# Sheet1.net
KiCad netlist of a schematic drawn in Altium Designer
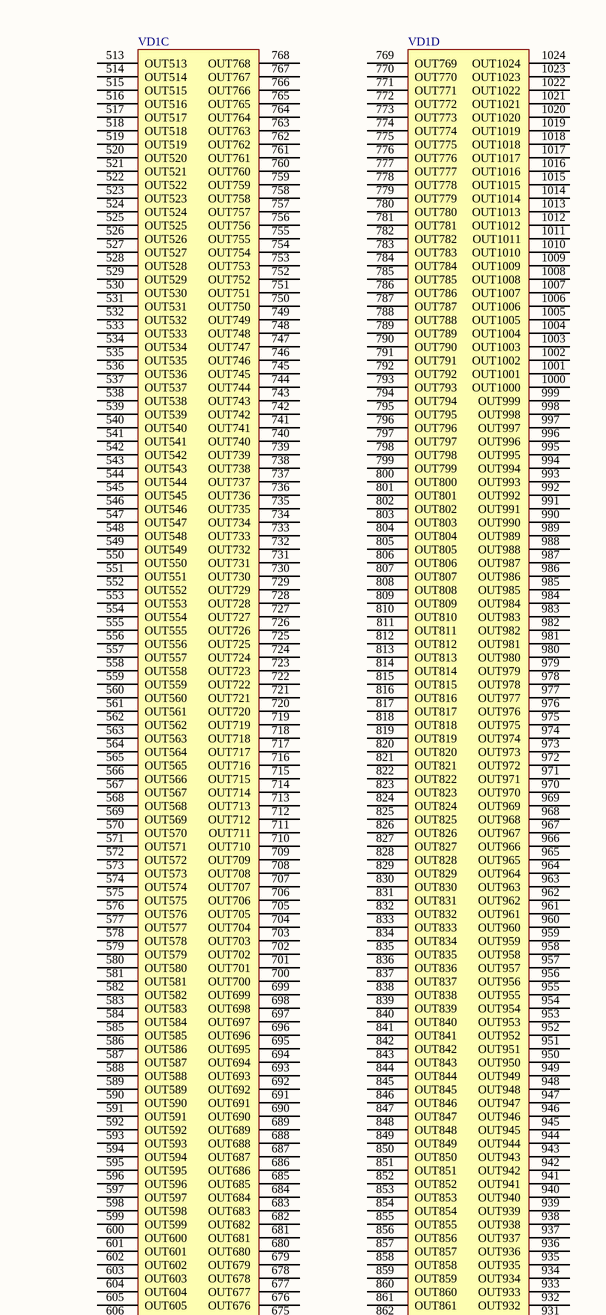
[diagram p0: Sheet1.SchDoc, top right]
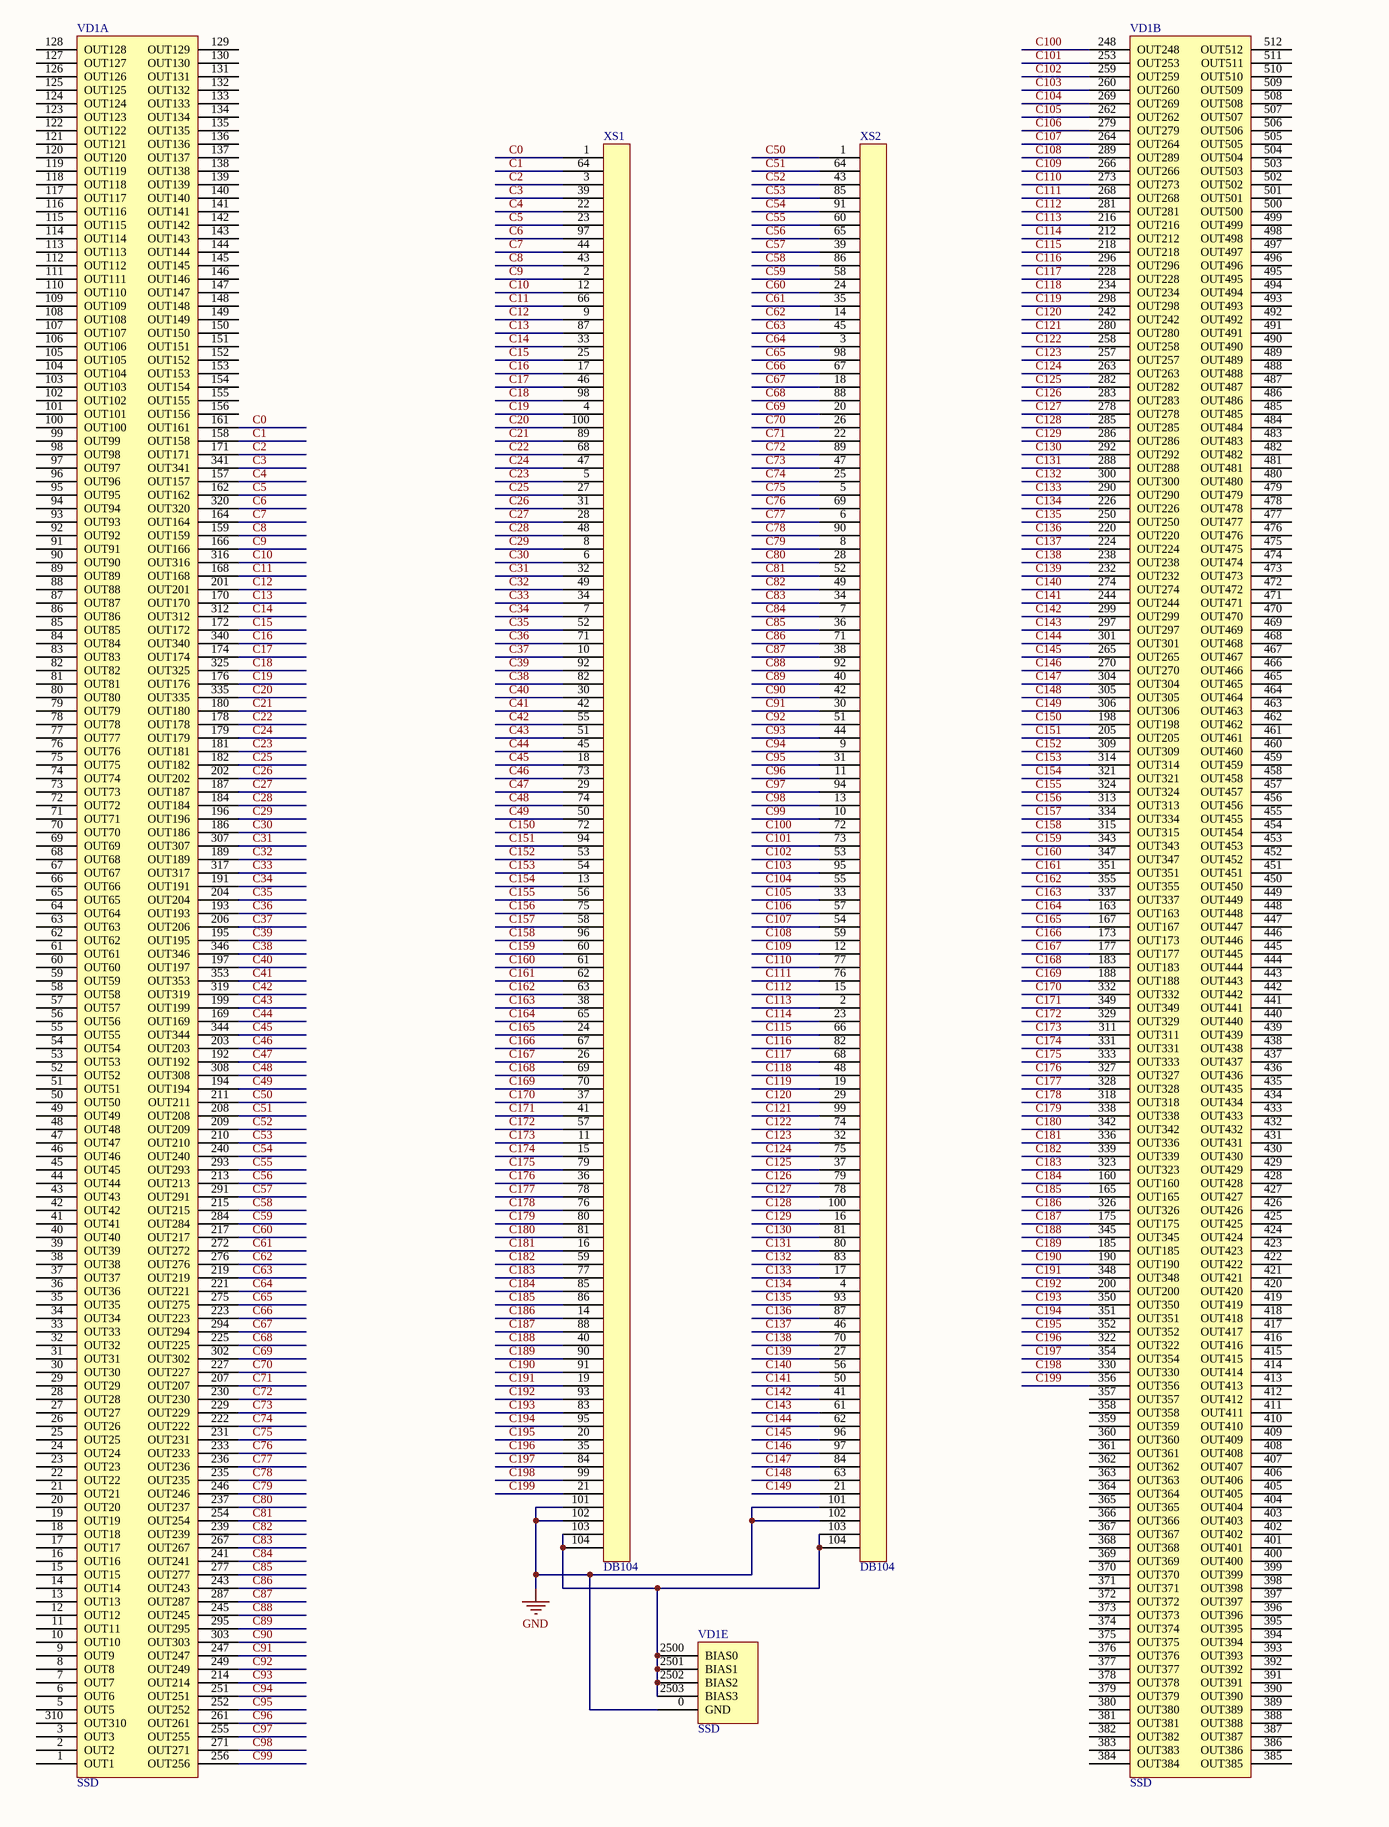
[diagram p1: Sheet1.SchDoc, bottom left]
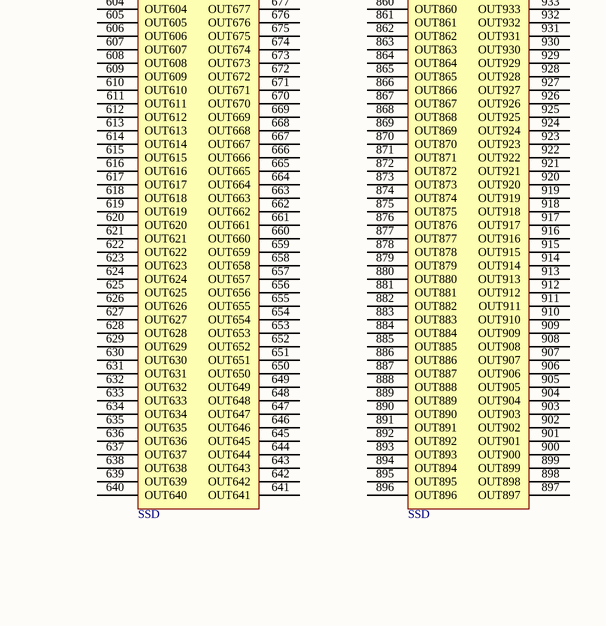
[diagram p2: Sheet1.SchDoc, bottom right]

(export (version "E")
  (design (tool "Eeschema 10.0.6"))
  (components
    (comp (ref "VD1")
      (value "SSD")
      (footprint "QFN20P11000X11000X80-2048N")
      (libsource (lib "Schlib") (part "SSD"))
    )
    (comp (ref "XS1") (value "DB104") (footprint "DB104") (libsource (lib "") (part "DB104_1")))
    (comp (ref "XS2") (value "DB104") (footprint "DB104") (libsource (lib "Schlib") (part "DB104")))
  )
  (nets
    (net (code "1") (name "/C0") (class "Default")
      (node (ref "VD1") (pin "161") (pinfunction "OUT161_161") (pintype "passive"))
      (node (ref "XS1") (pin "1") (pintype "passive"))
    )
    (net (code "2") (name "/C1") (class "Default")
      (node (ref "VD1") (pin "158") (pinfunction "OUT158_158") (pintype "passive"))
      (node (ref "XS1") (pin "64") (pintype "passive"))
    )
    (net (code "3") (name "/C2") (class "Default")
      (node (ref "VD1") (pin "171") (pinfunction "OUT171_171") (pintype "passive"))
      (node (ref "XS1") (pin "3") (pintype "passive"))
    )
    (net (code "4") (name "/C3") (class "Default")
      (node (ref "VD1") (pin "341") (pinfunction "OUT341_341") (pintype "passive"))
      (node (ref "XS1") (pin "39") (pintype "passive"))
    )
    (net (code "5") (name "/C4") (class "Default")
      (node (ref "VD1") (pin "157") (pinfunction "OUT157_157") (pintype "passive"))
      (node (ref "XS1") (pin "22") (pintype "passive"))
    )
    (net (code "6") (name "/C5") (class "Default")
      (node (ref "VD1") (pin "162") (pinfunction "OUT162_162") (pintype "passive"))
      (node (ref "XS1") (pin "23") (pintype "passive"))
    )
    (net (code "7") (name "/C6") (class "Default")
      (node (ref "VD1") (pin "320") (pinfunction "OUT320_320") (pintype "passive"))
      (node (ref "XS1") (pin "97") (pintype "passive"))
    )
    (net (code "8") (name "/C7") (class "Default")
      (node (ref "VD1") (pin "164") (pinfunction "OUT164_164") (pintype "passive"))
      (node (ref "XS1") (pin "44") (pintype "passive"))
    )
    (net (code "9") (name "/C8") (class "Default")
      (node (ref "VD1") (pin "159") (pinfunction "OUT159_159") (pintype "passive"))
      (node (ref "XS1") (pin "43") (pintype "passive"))
    )
    (net (code "10") (name "/C9") (class "Default")
      (node (ref "VD1") (pin "166") (pinfunction "OUT166_166") (pintype "passive"))
      (node (ref "XS1") (pin "2") (pintype "passive"))
    )
    (net (code "11") (name "/C10") (class "Default")
      (node (ref "VD1") (pin "316") (pinfunction "OUT316_316") (pintype "passive"))
      (node (ref "XS1") (pin "12") (pintype "passive"))
    )
    (net (code "12") (name "/C11") (class "Default")
      (node (ref "VD1") (pin "168") (pinfunction "OUT168_168") (pintype "passive"))
      (node (ref "XS1") (pin "66") (pintype "passive"))
    )
    (net (code "13") (name "/C12") (class "Default")
      (node (ref "VD1") (pin "201") (pinfunction "OUT201_201") (pintype "passive"))
      (node (ref "XS1") (pin "9") (pintype "passive"))
    )
    (net (code "14") (name "/C13") (class "Default")
      (node (ref "VD1") (pin "170") (pinfunction "OUT170_170") (pintype "passive"))
      (node (ref "XS1") (pin "87") (pintype "passive"))
    )
    (net (code "15") (name "/C14") (class "Default")
      (node (ref "VD1") (pin "312") (pinfunction "OUT312_312") (pintype "passive"))
      (node (ref "XS1") (pin "33") (pintype "passive"))
    )
    (net (code "16") (name "/C15") (class "Default")
      (node (ref "VD1") (pin "172") (pinfunction "OUT172_172") (pintype "passive"))
      (node (ref "XS1") (pin "25") (pintype "passive"))
    )
    (net (code "17") (name "/C16") (class "Default")
      (node (ref "VD1") (pin "340") (pinfunction "OUT340_340") (pintype "passive"))
      (node (ref "XS1") (pin "17") (pintype "passive"))
    )
    (net (code "18") (name "/C17") (class "Default")
      (node (ref "VD1") (pin "174") (pinfunction "OUT174_174") (pintype "passive"))
      (node (ref "XS1") (pin "46") (pintype "passive"))
    )
    (net (code "19") (name "/C18") (class "Default")
      (node (ref "VD1") (pin "325") (pinfunction "OUT325_325") (pintype "passive"))
      (node (ref "XS1") (pin "98") (pintype "passive"))
    )
    (net (code "20") (name "/C19") (class "Default")
      (node (ref "VD1") (pin "176") (pinfunction "OUT176_176") (pintype "passive"))
      (node (ref "XS1") (pin "4") (pintype "passive"))
    )
    (net (code "21") (name "/C20") (class "Default")
      (node (ref "VD1") (pin "335") (pinfunction "OUT335_335") (pintype "passive"))
      (node (ref "XS1") (pin "100") (pintype "passive"))
    )
    (net (code "22") (name "/C21") (class "Default")
      (node (ref "VD1") (pin "180") (pinfunction "OUT180_180") (pintype "passive"))
      (node (ref "XS1") (pin "89") (pintype "passive"))
    )
    (net (code "23") (name "/C22") (class "Default")
      (node (ref "VD1") (pin "178") (pinfunction "OUT178_178") (pintype "passive"))
      (node (ref "XS1") (pin "68") (pintype "passive"))
    )
    (net (code "24") (name "/C23") (class "Default")
      (node (ref "VD1") (pin "181") (pinfunction "OUT181_181") (pintype "passive"))
      (node (ref "XS1") (pin "5") (pintype "passive"))
    )
    (net (code "25") (name "/C24") (class "Default")
      (node (ref "VD1") (pin "179") (pinfunction "OUT179_179") (pintype "passive"))
      (node (ref "XS1") (pin "47") (pintype "passive"))
    )
    (net (code "26") (name "/C25") (class "Default")
      (node (ref "VD1") (pin "182") (pinfunction "OUT182_182") (pintype "passive"))
      (node (ref "XS1") (pin "27") (pintype "passive"))
    )
    (net (code "27") (name "/C26") (class "Default")
      (node (ref "VD1") (pin "202") (pinfunction "OUT202_202") (pintype "passive"))
      (node (ref "XS1") (pin "31") (pintype "passive"))
    )
    (net (code "28") (name "/C27") (class "Default")
      (node (ref "VD1") (pin "187") (pinfunction "OUT187_187") (pintype "passive"))
      (node (ref "XS1") (pin "28") (pintype "passive"))
    )
    (net (code "29") (name "/C28") (class "Default")
      (node (ref "VD1") (pin "184") (pinfunction "OUT184_184") (pintype "passive"))
      (node (ref "XS1") (pin "48") (pintype "passive"))
    )
    (net (code "30") (name "/C29") (class "Default")
      (node (ref "VD1") (pin "196") (pinfunction "OUT196_196") (pintype "passive"))
      (node (ref "XS1") (pin "8") (pintype "passive"))
    )
    (net (code "31") (name "/C30") (class "Default")
      (node (ref "VD1") (pin "186") (pinfunction "OUT186_186") (pintype "passive"))
      (node (ref "XS1") (pin "6") (pintype "passive"))
    )
    (net (code "32") (name "/C31") (class "Default")
      (node (ref "VD1") (pin "307") (pinfunction "OUT307_307") (pintype "passive"))
      (node (ref "XS1") (pin "32") (pintype "passive"))
    )
    (net (code "33") (name "/C32") (class "Default")
      (node (ref "VD1") (pin "189") (pinfunction "OUT189_189") (pintype "passive"))
      (node (ref "XS1") (pin "49") (pintype "passive"))
    )
    (net (code "34") (name "/C33") (class "Default")
      (node (ref "VD1") (pin "317") (pinfunction "OUT317_317") (pintype "passive"))
      (node (ref "XS1") (pin "34") (pintype "passive"))
    )
    (net (code "35") (name "/C34") (class "Default")
      (node (ref "VD1") (pin "191") (pinfunction "OUT191_191") (pintype "passive"))
      (node (ref "XS1") (pin "7") (pintype "passive"))
    )
    (net (code "36") (name "/C35") (class "Default")
      (node (ref "VD1") (pin "204") (pinfunction "OUT204_204") (pintype "passive"))
      (node (ref "XS1") (pin "52") (pintype "passive"))
    )
    (net (code "37") (name "/C36") (class "Default")
      (node (ref "VD1") (pin "193") (pinfunction "OUT193_193") (pintype "passive"))
      (node (ref "XS1") (pin "71") (pintype "passive"))
    )
    (net (code "38") (name "/C37") (class "Default")
      (node (ref "VD1") (pin "206") (pinfunction "OUT206_206") (pintype "passive"))
      (node (ref "XS1") (pin "10") (pintype "passive"))
    )
    (net (code "39") (name "/C38") (class "Default")
      (node (ref "VD1") (pin "346") (pinfunction "OUT346_346") (pintype "passive"))
      (node (ref "XS1") (pin "82") (pintype "passive"))
    )
    (net (code "40") (name "/C39") (class "Default")
      (node (ref "VD1") (pin "195") (pinfunction "OUT195_195") (pintype "passive"))
      (node (ref "XS1") (pin "92") (pintype "passive"))
    )
    (net (code "41") (name "/C40") (class "Default")
      (node (ref "VD1") (pin "197") (pinfunction "OUT197_197") (pintype "passive"))
      (node (ref "XS1") (pin "30") (pintype "passive"))
    )
    (net (code "42") (name "/C41") (class "Default")
      (node (ref "VD1") (pin "353") (pinfunction "OUT353_353") (pintype "passive"))
      (node (ref "XS1") (pin "42") (pintype "passive"))
    )
    (net (code "43") (name "/C42") (class "Default")
      (node (ref "VD1") (pin "319") (pinfunction "OUT319_319") (pintype "passive"))
      (node (ref "XS1") (pin "55") (pintype "passive"))
    )
    (net (code "44") (name "/C43") (class "Default")
      (node (ref "VD1") (pin "199") (pinfunction "OUT199_199") (pintype "passive"))
      (node (ref "XS1") (pin "51") (pintype "passive"))
    )
    (net (code "45") (name "/C44") (class "Default")
      (node (ref "VD1") (pin "169") (pinfunction "OUT169_169") (pintype "passive"))
      (node (ref "XS1") (pin "45") (pintype "passive"))
    )
    (net (code "46") (name "/C45") (class "Default")
      (node (ref "VD1") (pin "344") (pinfunction "OUT344_344") (pintype "passive"))
      (node (ref "XS1") (pin "18") (pintype "passive"))
    )
    (net (code "47") (name "/C46") (class "Default")
      (node (ref "VD1") (pin "203") (pinfunction "OUT203_203") (pintype "passive"))
      (node (ref "XS1") (pin "73") (pintype "passive"))
    )
    (net (code "48") (name "/C47") (class "Default")
      (node (ref "VD1") (pin "192") (pinfunction "OUT192_192") (pintype "passive"))
      (node (ref "XS1") (pin "29") (pintype "passive"))
    )
    (net (code "49") (name "/C48") (class "Default")
      (node (ref "VD1") (pin "308") (pinfunction "OUT308_308") (pintype "passive"))
      (node (ref "XS1") (pin "74") (pintype "passive"))
    )
    (net (code "50") (name "/C49") (class "Default")
      (node (ref "VD1") (pin "194") (pinfunction "OUT194_194") (pintype "passive"))
      (node (ref "XS1") (pin "50") (pintype "passive"))
    )
    (net (code "51") (name "/C50") (class "Default")
      (node (ref "VD1") (pin "211") (pinfunction "OUT211_211") (pintype "passive"))
      (node (ref "XS2") (pin "1") (pintype "passive"))
    )
    (net (code "52") (name "/C51") (class "Default")
      (node (ref "VD1") (pin "208") (pinfunction "OUT208_208") (pintype "passive"))
      (node (ref "XS2") (pin "64") (pintype "passive"))
    )
    (net (code "53") (name "/C52") (class "Default")
      (node (ref "VD1") (pin "209") (pinfunction "OUT209_209") (pintype "passive"))
      (node (ref "XS2") (pin "43") (pintype "passive"))
    )
    (net (code "54") (name "/C53") (class "Default")
      (node (ref "VD1") (pin "210") (pinfunction "OUT210_210") (pintype "passive"))
      (node (ref "XS2") (pin "85") (pintype "passive"))
    )
    (net (code "55") (name "/C54") (class "Default")
      (node (ref "VD1") (pin "240") (pinfunction "OUT240_240") (pintype "passive"))
      (node (ref "XS2") (pin "91") (pintype "passive"))
    )
    (net (code "56") (name "/C55") (class "Default")
      (node (ref "VD1") (pin "293") (pinfunction "OUT293_293") (pintype "passive"))
      (node (ref "XS2") (pin "60") (pintype "passive"))
    )
    (net (code "57") (name "/C56") (class "Default")
      (node (ref "VD1") (pin "213") (pinfunction "OUT213_213") (pintype "passive"))
      (node (ref "XS2") (pin "65") (pintype "passive"))
    )
    (net (code "58") (name "/C57") (class "Default")
      (node (ref "VD1") (pin "291") (pinfunction "OUT291_291") (pintype "passive"))
      (node (ref "XS2") (pin "39") (pintype "passive"))
    )
    (net (code "59") (name "/C58") (class "Default")
      (node (ref "VD1") (pin "215") (pinfunction "OUT215_215") (pintype "passive"))
      (node (ref "XS2") (pin "86") (pintype "passive"))
    )
    (net (code "60") (name "/C59") (class "Default")
      (node (ref "VD1") (pin "284") (pinfunction "OUT284_284") (pintype "passive"))
      (node (ref "XS2") (pin "58") (pintype "passive"))
    )
    (net (code "61") (name "/C60") (class "Default")
      (node (ref "VD1") (pin "217") (pinfunction "OUT217_217") (pintype "passive"))
      (node (ref "XS2") (pin "24") (pintype "passive"))
    )
    (net (code "62") (name "/C61") (class "Default")
      (node (ref "VD1") (pin "272") (pinfunction "OUT272_272") (pintype "passive"))
      (node (ref "XS2") (pin "35") (pintype "passive"))
    )
    (net (code "63") (name "/C62") (class "Default")
      (node (ref "VD1") (pin "276") (pinfunction "OUT276_276") (pintype "passive"))
      (node (ref "XS2") (pin "14") (pintype "passive"))
    )
    (net (code "64") (name "/C63") (class "Default")
      (node (ref "VD1") (pin "219") (pinfunction "OUT219_219") (pintype "passive"))
      (node (ref "XS2") (pin "45") (pintype "passive"))
    )
    (net (code "65") (name "/C64") (class "Default")
      (node (ref "VD1") (pin "221") (pinfunction "OUT221_221") (pintype "passive"))
      (node (ref "XS2") (pin "3") (pintype "passive"))
    )
    (net (code "66") (name "/C65") (class "Default")
      (node (ref "VD1") (pin "275") (pinfunction "OUT275_275") (pintype "passive"))
      (node (ref "XS2") (pin "98") (pintype "passive"))
    )
    (net (code "67") (name "/C66") (class "Default")
      (node (ref "VD1") (pin "223") (pinfunction "OUT223_223") (pintype "passive"))
      (node (ref "XS2") (pin "67") (pintype "passive"))
    )
    (net (code "68") (name "/C67") (class "Default")
      (node (ref "VD1") (pin "294") (pinfunction "OUT294_294") (pintype "passive"))
      (node (ref "XS2") (pin "18") (pintype "passive"))
    )
    (net (code "69") (name "/C68") (class "Default")
      (node (ref "VD1") (pin "225") (pinfunction "OUT225_225") (pintype "passive"))
      (node (ref "XS2") (pin "88") (pintype "passive"))
    )
    (net (code "70") (name "/C69") (class "Default")
      (node (ref "VD1") (pin "302") (pinfunction "OUT302_302") (pintype "passive"))
      (node (ref "XS2") (pin "20") (pintype "passive"))
    )
    (net (code "71") (name "/C70") (class "Default")
      (node (ref "VD1") (pin "227") (pinfunction "OUT227_227") (pintype "passive"))
      (node (ref "XS2") (pin "26") (pintype "passive"))
    )
    (net (code "72") (name "/C71") (class "Default")
      (node (ref "VD1") (pin "207") (pinfunction "OUT207_207") (pintype "passive"))
      (node (ref "XS2") (pin "22") (pintype "passive"))
    )
    (net (code "73") (name "/C72") (class "Default")
      (node (ref "VD1") (pin "230") (pinfunction "OUT230_230") (pintype "passive"))
      (node (ref "XS2") (pin "89") (pintype "passive"))
    )
    (net (code "74") (name "/C73") (class "Default")
      (node (ref "VD1") (pin "229") (pinfunction "OUT229_229") (pintype "passive"))
      (node (ref "XS2") (pin "47") (pintype "passive"))
    )
    (net (code "75") (name "/C74") (class "Default")
      (node (ref "VD1") (pin "222") (pinfunction "OUT222_222") (pintype "passive"))
      (node (ref "XS2") (pin "25") (pintype "passive"))
    )
    (net (code "76") (name "/C75") (class "Default")
      (node (ref "VD1") (pin "231") (pinfunction "OUT231_231") (pintype "passive"))
      (node (ref "XS2") (pin "5") (pintype "passive"))
    )
    (net (code "77") (name "/C76") (class "Default")
      (node (ref "VD1") (pin "233") (pinfunction "OUT233_233") (pintype "passive"))
      (node (ref "XS2") (pin "69") (pintype "passive"))
    )
    (net (code "78") (name "/C77") (class "Default")
      (node (ref "VD1") (pin "236") (pinfunction "OUT236_236") (pintype "passive"))
      (node (ref "XS2") (pin "6") (pintype "passive"))
    )
    (net (code "79") (name "/C78") (class "Default")
      (node (ref "VD1") (pin "235") (pinfunction "OUT235_235") (pintype "passive"))
      (node (ref "XS2") (pin "90") (pintype "passive"))
    )
    (net (code "80") (name "/C79") (class "Default")
      (node (ref "VD1") (pin "246") (pinfunction "OUT246_246") (pintype "passive"))
      (node (ref "XS2") (pin "8") (pintype "passive"))
    )
    (net (code "81") (name "/C80") (class "Default")
      (node (ref "VD1") (pin "237") (pinfunction "OUT237_237") (pintype "passive"))
      (node (ref "XS2") (pin "28") (pintype "passive"))
    )
    (net (code "82") (name "/C81") (class "Default")
      (node (ref "VD1") (pin "254") (pinfunction "OUT254_254") (pintype "passive"))
      (node (ref "XS2") (pin "52") (pintype "passive"))
    )
    (net (code "83") (name "/C82") (class "Default")
      (node (ref "VD1") (pin "239") (pinfunction "OUT239_239") (pintype "passive"))
      (node (ref "XS2") (pin "49") (pintype "passive"))
    )
    (net (code "84") (name "/C83") (class "Default")
      (node (ref "VD1") (pin "267") (pinfunction "OUT267_267") (pintype "passive"))
      (node (ref "XS2") (pin "34") (pintype "passive"))
    )
    (net (code "85") (name "/C84") (class "Default")
      (node (ref "VD1") (pin "241") (pinfunction "OUT241_241") (pintype "passive"))
      (node (ref "XS2") (pin "7") (pintype "passive"))
    )
    (net (code "86") (name "/C85") (class "Default")
      (node (ref "VD1") (pin "277") (pinfunction "OUT277_277") (pintype "passive"))
      (node (ref "XS2") (pin "36") (pintype "passive"))
    )
    (net (code "87") (name "/C86") (class "Default")
      (node (ref "VD1") (pin "243") (pinfunction "OUT243_243") (pintype "passive"))
      (node (ref "XS2") (pin "71") (pintype "passive"))
    )
    (net (code "88") (name "/C87") (class "Default")
      (node (ref "VD1") (pin "287") (pinfunction "OUT287_287") (pintype "passive"))
      (node (ref "XS2") (pin "38") (pintype "passive"))
    )
    (net (code "89") (name "/C88") (class "Default")
      (node (ref "VD1") (pin "245") (pinfunction "OUT245_245") (pintype "passive"))
      (node (ref "XS2") (pin "92") (pintype "passive"))
    )
    (net (code "90") (name "/C89") (class "Default")
      (node (ref "VD1") (pin "295") (pinfunction "OUT295_295") (pintype "passive"))
      (node (ref "XS2") (pin "40") (pintype "passive"))
    )
    (net (code "91") (name "/C90") (class "Default")
      (node (ref "VD1") (pin "303") (pinfunction "OUT303_303") (pintype "passive"))
      (node (ref "XS2") (pin "42") (pintype "passive"))
    )
    (net (code "92") (name "/C91") (class "Default")
      (node (ref "VD1") (pin "247") (pinfunction "OUT247_247") (pintype "passive"))
      (node (ref "XS2") (pin "30") (pintype "passive"))
    )
    (net (code "93") (name "/C92") (class "Default")
      (node (ref "VD1") (pin "249") (pinfunction "OUT249_249") (pintype "passive"))
      (node (ref "XS2") (pin "51") (pintype "passive"))
    )
    (net (code "94") (name "/C93") (class "Default")
      (node (ref "VD1") (pin "214") (pinfunction "OUT214_214") (pintype "passive"))
      (node (ref "XS2") (pin "44") (pintype "passive"))
    )
    (net (code "95") (name "/C94") (class "Default")
      (node (ref "VD1") (pin "251") (pinfunction "OUT251_251") (pintype "passive"))
      (node (ref "XS2") (pin "9") (pintype "passive"))
    )
    (net (code "96") (name "/C95") (class "Default")
      (node (ref "VD1") (pin "252") (pinfunction "OUT252_252") (pintype "passive"))
      (node (ref "XS2") (pin "31") (pintype "passive"))
    )
    (net (code "97") (name "/C96") (class "Default")
      (node (ref "VD1") (pin "261") (pinfunction "OUT261_261") (pintype "passive"))
      (node (ref "XS2") (pin "11") (pintype "passive"))
    )
    (net (code "98") (name "/C97") (class "Default")
      (node (ref "VD1") (pin "255") (pinfunction "OUT255_255") (pintype "passive"))
      (node (ref "XS2") (pin "94") (pintype "passive"))
    )
    (net (code "99") (name "/C98") (class "Default")
      (node (ref "VD1") (pin "271") (pinfunction "OUT271_271") (pintype "passive"))
      (node (ref "XS2") (pin "13") (pintype "passive"))
    )
    (net (code "100") (name "/C99") (class "Default")
      (node (ref "VD1") (pin "256") (pinfunction "OUT256_256") (pintype "passive"))
      (node (ref "XS2") (pin "10") (pintype "passive"))
    )
    (net (code "101") (name "/C100") (class "Default")
      (node (ref "VD1") (pin "248") (pinfunction "OUT248_248") (pintype "passive"))
      (node (ref "XS2") (pin "72") (pintype "passive"))
    )
    (net (code "102") (name "/C101") (class "Default")
      (node (ref "VD1") (pin "253") (pinfunction "OUT253_253") (pintype "passive"))
      (node (ref "XS2") (pin "73") (pintype "passive"))
    )
    (net (code "103") (name "/C102") (class "Default")
      (node (ref "VD1") (pin "259") (pinfunction "OUT259_259") (pintype "passive"))
      (node (ref "XS2") (pin "53") (pintype "passive"))
    )
    (net (code "104") (name "/C103") (class "Default")
      (node (ref "VD1") (pin "260") (pinfunction "OUT260_260") (pintype "passive"))
      (node (ref "XS2") (pin "95") (pintype "passive"))
    )
    (net (code "105") (name "/C104") (class "Default")
      (node (ref "VD1") (pin "269") (pinfunction "OUT269_269") (pintype "passive"))
      (node (ref "XS2") (pin "55") (pintype "passive"))
    )
    (net (code "106") (name "/C105") (class "Default")
      (node (ref "VD1") (pin "262") (pinfunction "OUT262_262") (pintype "passive"))
      (node (ref "XS2") (pin "33") (pintype "passive"))
    )
    (net (code "107") (name "/C106") (class "Default")
      (node (ref "VD1") (pin "279") (pinfunction "OUT279_279") (pintype "passive"))
      (node (ref "XS2") (pin "57") (pintype "passive"))
    )
    (net (code "108") (name "/C107") (class "Default")
      (node (ref "VD1") (pin "264") (pinfunction "OUT264_264") (pintype "passive"))
      (node (ref "XS2") (pin "54") (pintype "passive"))
    )
    (net (code "109") (name "/C108") (class "Default")
      (node (ref "VD1") (pin "289") (pinfunction "OUT289_289") (pintype "passive"))
      (node (ref "XS2") (pin "59") (pintype "passive"))
    )
    (net (code "110") (name "/C109") (class "Default")
      (node (ref "VD1") (pin "266") (pinfunction "OUT266_266") (pintype "passive"))
      (node (ref "XS2") (pin "12") (pintype "passive"))
    )
    (net (code "111") (name "/C110") (class "Default")
      (node (ref "VD1") (pin "273") (pinfunction "OUT273_273") (pintype "passive"))
      (node (ref "XS2") (pin "77") (pintype "passive"))
    )
    (net (code "112") (name "/C111") (class "Default")
      (node (ref "VD1") (pin "268") (pinfunction "OUT268_268") (pintype "passive"))
      (node (ref "XS2") (pin "76") (pintype "passive"))
    )
    (net (code "113") (name "/C112") (class "Default")
      (node (ref "VD1") (pin "281") (pinfunction "OUT281_281") (pintype "passive"))
      (node (ref "XS2") (pin "15") (pintype "passive"))
    )
    (net (code "114") (name "/C113") (class "Default")
      (node (ref "VD1") (pin "216") (pinfunction "OUT216_216") (pintype "passive"))
      (node (ref "XS2") (pin "2") (pintype "passive"))
    )
    (net (code "115") (name "/C114") (class "Default")
      (node (ref "VD1") (pin "212") (pinfunction "OUT212_212") (pintype "passive"))
      (node (ref "XS2") (pin "23") (pintype "passive"))
    )
    (net (code "116") (name "/C115") (class "Default")
      (node (ref "VD1") (pin "218") (pinfunction "OUT218_218") (pintype "passive"))
      (node (ref "XS2") (pin "66") (pintype "passive"))
    )
    (net (code "117") (name "/C116") (class "Default")
      (node (ref "VD1") (pin "296") (pinfunction "OUT296_296") (pintype "passive"))
      (node (ref "XS2") (pin "82") (pintype "passive"))
    )
    (net (code "118") (name "/C117") (class "Default")
      (node (ref "VD1") (pin "228") (pinfunction "OUT228_228") (pintype "passive"))
      (node (ref "XS2") (pin "68") (pintype "passive"))
    )
    (net (code "119") (name "/C118") (class "Default")
      (node (ref "VD1") (pin "234") (pinfunction "OUT234_234") (pintype "passive"))
      (node (ref "XS2") (pin "48") (pintype "passive"))
    )
    (net (code "120") (name "/C119") (class "Default")
      (node (ref "VD1") (pin "298") (pinfunction "OUT298_298") (pintype "passive"))
      (node (ref "XS2") (pin "19") (pintype "passive"))
    )
    (net (code "121") (name "/C120") (class "Default")
      (node (ref "VD1") (pin "242") (pinfunction "OUT242_242") (pintype "passive"))
      (node (ref "XS2") (pin "29") (pintype "passive"))
    )
    (net (code "122") (name "/C121") (class "Default")
      (node (ref "VD1") (pin "280") (pinfunction "OUT280_280") (pintype "passive"))
      (node (ref "XS2") (pin "99") (pintype "passive"))
    )
    (net (code "123") (name "/C122") (class "Default")
      (node (ref "VD1") (pin "258") (pinfunction "OUT258_258") (pintype "passive"))
      (node (ref "XS2") (pin "74") (pintype "passive"))
    )
    (net (code "124") (name "/C123") (class "Default")
      (node (ref "VD1") (pin "257") (pinfunction "OUT257_257") (pintype "passive"))
      (node (ref "XS2") (pin "32") (pintype "passive"))
    )
    (net (code "125") (name "/C124") (class "Default")
      (node (ref "VD1") (pin "263") (pinfunction "OUT263_263") (pintype "passive"))
      (node (ref "XS2") (pin "75") (pintype "passive"))
    )
    (net (code "126") (name "/C125") (class "Default")
      (node (ref "VD1") (pin "282") (pinfunction "OUT282_282") (pintype "passive"))
      (node (ref "XS2") (pin "37") (pintype "passive"))
    )
    (net (code "127") (name "/C126") (class "Default")
      (node (ref "VD1") (pin "283") (pinfunction "OUT283_283") (pintype "passive"))
      (node (ref "XS2") (pin "79") (pintype "passive"))
    )
    (net (code "128") (name "/C127") (class "Default")
      (node (ref "VD1") (pin "278") (pinfunction "OUT278_278") (pintype "passive"))
      (node (ref "XS2") (pin "78") (pintype "passive"))
    )
    (net (code "129") (name "/C128") (class "Default")
      (node (ref "VD1") (pin "285") (pinfunction "OUT285_285") (pintype "passive"))
      (node (ref "XS2") (pin "100") (pintype "passive"))
    )
    (net (code "130") (name "/C129") (class "Default")
      (node (ref "VD1") (pin "286") (pinfunction "OUT286_286") (pintype "passive"))
      (node (ref "XS2") (pin "16") (pintype "passive"))
    )
    (net (code "131") (name "/C130") (class "Default")
      (node (ref "VD1") (pin "292") (pinfunction "OUT292_292") (pintype "passive"))
      (node (ref "XS2") (pin "81") (pintype "passive"))
    )
    (net (code "132") (name "/C131") (class "Default")
      (node (ref "VD1") (pin "288") (pinfunction "OUT288_288") (pintype "passive"))
      (node (ref "XS2") (pin "80") (pintype "passive"))
    )
    (net (code "133") (name "/C132") (class "Default")
      (node (ref "VD1") (pin "300") (pinfunction "OUT300_300") (pintype "passive"))
      (node (ref "XS2") (pin "83") (pintype "passive"))
    )
    (net (code "134") (name "/C133") (class "Default")
      (node (ref "VD1") (pin "290") (pinfunction "OUT290_290") (pintype "passive"))
      (node (ref "XS2") (pin "17") (pintype "passive"))
    )
    (net (code "135") (name "/C134") (class "Default")
      (node (ref "VD1") (pin "226") (pinfunction "OUT226_226") (pintype "passive"))
      (node (ref "XS2") (pin "4") (pintype "passive"))
    )
    (net (code "136") (name "/C135") (class "Default")
      (node (ref "VD1") (pin "250") (pinfunction "OUT250_250") (pintype "passive"))
      (node (ref "XS2") (pin "93") (pintype "passive"))
    )
    (net (code "137") (name "/C136") (class "Default")
      (node (ref "VD1") (pin "220") (pinfunction "OUT220_220") (pintype "passive"))
      (node (ref "XS2") (pin "87") (pintype "passive"))
    )
    (net (code "138") (name "/C137") (class "Default")
      (node (ref "VD1") (pin "224") (pinfunction "OUT224_224") (pintype "passive"))
      (node (ref "XS2") (pin "46") (pintype "passive"))
    )
    (net (code "139") (name "/C138") (class "Default")
      (node (ref "VD1") (pin "238") (pinfunction "OUT238_238") (pintype "passive"))
      (node (ref "XS2") (pin "70") (pintype "passive"))
    )
    (net (code "140") (name "/C139") (class "Default")
      (node (ref "VD1") (pin "232") (pinfunction "OUT232_232") (pintype "passive"))
      (node (ref "XS2") (pin "27") (pintype "passive"))
    )
    (net (code "141") (name "/C140") (class "Default")
      (node (ref "VD1") (pin "274") (pinfunction "OUT274_274") (pintype "passive"))
      (node (ref "XS2") (pin "56") (pintype "passive"))
    )
    (net (code "142") (name "/C141") (class "Default")
      (node (ref "VD1") (pin "244") (pinfunction "OUT244_244") (pintype "passive"))
      (node (ref "XS2") (pin "50") (pintype "passive"))
    )
    (net (code "143") (name "/C142") (class "Default")
      (node (ref "VD1") (pin "299") (pinfunction "OUT299_299") (pintype "passive"))
      (node (ref "XS2") (pin "41") (pintype "passive"))
    )
    (net (code "144") (name "/C143") (class "Default")
      (node (ref "VD1") (pin "297") (pinfunction "OUT297_297") (pintype "passive"))
      (node (ref "XS2") (pin "61") (pintype "passive"))
    )
    (net (code "145") (name "/C144") (class "Default")
      (node (ref "VD1") (pin "301") (pinfunction "OUT301_301") (pintype "passive"))
      (node (ref "XS2") (pin "62") (pintype "passive"))
    )
    (net (code "146") (name "/C145") (class "Default")
      (node (ref "VD1") (pin "265") (pinfunction "OUT265_265") (pintype "passive"))
      (node (ref "XS2") (pin "96") (pintype "passive"))
    )
    (net (code "147") (name "/C146") (class "Default")
      (node (ref "VD1") (pin "270") (pinfunction "OUT270_270") (pintype "passive"))
      (node (ref "XS2") (pin "97") (pintype "passive"))
    )
    (net (code "148") (name "/C147") (class "Default")
      (node (ref "VD1") (pin "304") (pinfunction "OUT304_304") (pintype "passive"))
      (node (ref "XS2") (pin "84") (pintype "passive"))
    )
    (net (code "149") (name "/C148") (class "Default")
      (node (ref "VD1") (pin "305") (pinfunction "OUT305_305") (pintype "passive"))
      (node (ref "XS2") (pin "63") (pintype "passive"))
    )
    (net (code "150") (name "/C149") (class "Default")
      (node (ref "VD1") (pin "306") (pinfunction "OUT306_306") (pintype "passive"))
      (node (ref "XS2") (pin "21") (pintype "passive"))
    )
    (net (code "151") (name "/C150") (class "Default")
      (node (ref "VD1") (pin "198") (pinfunction "OUT198_198") (pintype "passive"))
      (node (ref "XS1") (pin "72") (pintype "passive"))
    )
    (net (code "152") (name "/C151") (class "Default")
      (node (ref "VD1") (pin "205") (pinfunction "OUT205_205") (pintype "passive"))
      (node (ref "XS1") (pin "94") (pintype "passive"))
    )
    (net (code "153") (name "/C152") (class "Default")
      (node (ref "VD1") (pin "309") (pinfunction "OUT309_309") (pintype "passive"))
      (node (ref "XS1") (pin "53") (pintype "passive"))
    )
    (net (code "154") (name "/C153") (class "Default")
      (node (ref "VD1") (pin "314") (pinfunction "OUT314_314") (pintype "passive"))
      (node (ref "XS1") (pin "54") (pintype "passive"))
    )
    (net (code "155") (name "/C154") (class "Default")
      (node (ref "VD1") (pin "321") (pinfunction "OUT321_321") (pintype "passive"))
      (node (ref "XS1") (pin "13") (pintype "passive"))
    )
    (net (code "156") (name "/C155") (class "Default")
      (node (ref "VD1") (pin "324") (pinfunction "OUT324_324") (pintype "passive"))
      (node (ref "XS1") (pin "56") (pintype "passive"))
    )
    (net (code "157") (name "/C156") (class "Default")
      (node (ref "VD1") (pin "313") (pinfunction "OUT313_313") (pintype "passive"))
      (node (ref "XS1") (pin "75") (pintype "passive"))
    )
    (net (code "158") (name "/C157") (class "Default")
      (node (ref "VD1") (pin "334") (pinfunction "OUT334_334") (pintype "passive"))
      (node (ref "XS1") (pin "58") (pintype "passive"))
    )
    (net (code "159") (name "/C158") (class "Default")
      (node (ref "VD1") (pin "315") (pinfunction "OUT315_315") (pintype "passive"))
      (node (ref "XS1") (pin "96") (pintype "passive"))
    )
    (net (code "160") (name "/C159") (class "Default")
      (node (ref "VD1") (pin "343") (pinfunction "OUT343_343") (pintype "passive"))
      (node (ref "XS1") (pin "60") (pintype "passive"))
    )
    (net (code "161") (name "/C160") (class "Default")
      (node (ref "VD1") (pin "347") (pinfunction "OUT347_347") (pintype "passive"))
      (node (ref "XS1") (pin "61") (pintype "passive"))
    )
    (net (code "162") (name "/C161") (class "Default")
      (node (ref "VD1") (pin "351") (pinfunction "OUT351_351") (pintype "passive"))
      (node (ref "XS1") (pin "62") (pintype "passive"))
    )
    (net (code "163") (name "/C162") (class "Default")
      (node (ref "VD1") (pin "355") (pinfunction "OUT355_355") (pintype "passive"))
      (node (ref "XS1") (pin "63") (pintype "passive"))
    )
    (net (code "164") (name "/C163") (class "Default")
      (node (ref "VD1") (pin "337") (pinfunction "OUT337_337") (pintype "passive"))
      (node (ref "XS1") (pin "38") (pintype "passive"))
    )
    (net (code "165") (name "/C164") (class "Default")
      (node (ref "VD1") (pin "163") (pinfunction "OUT163_163") (pintype "passive"))
      (node (ref "XS1") (pin "65") (pintype "passive"))
    )
    (net (code "166") (name "/C165") (class "Default")
      (node (ref "VD1") (pin "167") (pinfunction "OUT167_167") (pintype "passive"))
      (node (ref "XS1") (pin "24") (pintype "passive"))
    )
    (net (code "167") (name "/C166") (class "Default")
      (node (ref "VD1") (pin "173") (pinfunction "OUT173_173") (pintype "passive"))
      (node (ref "XS1") (pin "67") (pintype "passive"))
    )
    (net (code "168") (name "/C167") (class "Default")
      (node (ref "VD1") (pin "177") (pinfunction "OUT177_177") (pintype "passive"))
      (node (ref "XS1") (pin "26") (pintype "passive"))
    )
    (net (code "169") (name "/C168") (class "Default")
      (node (ref "VD1") (pin "183") (pinfunction "OUT183_183") (pintype "passive"))
      (node (ref "XS1") (pin "69") (pintype "passive"))
    )
    (net (code "170") (name "/C169") (class "Default")
      (node (ref "VD1") (pin "188") (pinfunction "OUT188_188") (pintype "passive"))
      (node (ref "XS1") (pin "70") (pintype "passive"))
    )
    (net (code "171") (name "/C170") (class "Default")
      (node (ref "VD1") (pin "332") (pinfunction "OUT332_332") (pintype "passive"))
      (node (ref "XS1") (pin "37") (pintype "passive"))
    )
    (net (code "172") (name "/C171") (class "Default")
      (node (ref "VD1") (pin "349") (pinfunction "OUT349_349") (pintype "passive"))
      (node (ref "XS1") (pin "41") (pintype "passive"))
    )
    (net (code "173") (name "/C172") (class "Default")
      (node (ref "VD1") (pin "329") (pinfunction "OUT329_329") (pintype "passive"))
      (node (ref "XS1") (pin "57") (pintype "passive"))
    )
    (net (code "174") (name "/C173") (class "Default")
      (node (ref "VD1") (pin "311") (pinfunction "OUT311_311") (pintype "passive"))
      (node (ref "XS1") (pin "11") (pintype "passive"))
    )
    (net (code "175") (name "/C174") (class "Default")
      (node (ref "VD1") (pin "331") (pinfunction "OUT331_331") (pintype "passive"))
      (node (ref "XS1") (pin "15") (pintype "passive"))
    )
    (net (code "176") (name "/C175") (class "Default")
      (node (ref "VD1") (pin "333") (pinfunction "OUT333_333") (pintype "passive"))
      (node (ref "XS1") (pin "79") (pintype "passive"))
    )
    (net (code "177") (name "/C176") (class "Default")
      (node (ref "VD1") (pin "327") (pinfunction "OUT327_327") (pintype "passive"))
      (node (ref "XS1") (pin "36") (pintype "passive"))
    )
    (net (code "178") (name "/C177") (class "Default")
      (node (ref "VD1") (pin "328") (pinfunction "OUT328_328") (pintype "passive"))
      (node (ref "XS1") (pin "78") (pintype "passive"))
    )
    (net (code "179") (name "/C178") (class "Default")
      (node (ref "VD1") (pin "318") (pinfunction "OUT318_318") (pintype "passive"))
      (node (ref "XS1") (pin "76") (pintype "passive"))
    )
    (net (code "180") (name "/C179") (class "Default")
      (node (ref "VD1") (pin "338") (pinfunction "OUT338_338") (pintype "passive"))
      (node (ref "XS1") (pin "80") (pintype "passive"))
    )
    (net (code "181") (name "/C180") (class "Default")
      (node (ref "VD1") (pin "342") (pinfunction "OUT342_342") (pintype "passive"))
      (node (ref "XS1") (pin "81") (pintype "passive"))
    )
    (net (code "182") (name "/C181") (class "Default")
      (node (ref "VD1") (pin "336") (pinfunction "OUT336_336") (pintype "passive"))
      (node (ref "XS1") (pin "16") (pintype "passive"))
    )
    (net (code "183") (name "/C182") (class "Default")
      (node (ref "VD1") (pin "339") (pinfunction "OUT339_339") (pintype "passive"))
      (node (ref "XS1") (pin "59") (pintype "passive"))
    )
    (net (code "184") (name "/C183") (class "Default")
      (node (ref "VD1") (pin "323") (pinfunction "OUT323_323") (pintype "passive"))
      (node (ref "XS1") (pin "77") (pintype "passive"))
    )
    (net (code "185") (name "/C184") (class "Default")
      (node (ref "VD1") (pin "160") (pinfunction "OUT160_160") (pintype "passive"))
      (node (ref "XS1") (pin "85") (pintype "passive"))
    )
    (net (code "186") (name "/C185") (class "Default")
      (node (ref "VD1") (pin "165") (pinfunction "OUT165_165") (pintype "passive"))
      (node (ref "XS1") (pin "86") (pintype "passive"))
    )
    (net (code "187") (name "/C186") (class "Default")
      (node (ref "VD1") (pin "326") (pinfunction "OUT326_326") (pintype "passive"))
      (node (ref "XS1") (pin "14") (pintype "passive"))
    )
    (net (code "188") (name "/C187") (class "Default")
      (node (ref "VD1") (pin "175") (pinfunction "OUT175_175") (pintype "passive"))
      (node (ref "XS1") (pin "88") (pintype "passive"))
    )
    (net (code "189") (name "/C188") (class "Default")
      (node (ref "VD1") (pin "345") (pinfunction "OUT345_345") (pintype "passive"))
      (node (ref "XS1") (pin "40") (pintype "passive"))
    )
    (net (code "190") (name "/C189") (class "Default")
      (node (ref "VD1") (pin "185") (pinfunction "OUT185_185") (pintype "passive"))
      (node (ref "XS1") (pin "90") (pintype "passive"))
    )
    (net (code "191") (name "/C190") (class "Default")
      (node (ref "VD1") (pin "190") (pinfunction "OUT190_190") (pintype "passive"))
      (node (ref "XS1") (pin "91") (pintype "passive"))
    )
    (net (code "192") (name "/C191") (class "Default")
      (node (ref "VD1") (pin "348") (pinfunction "OUT348_348") (pintype "passive"))
      (node (ref "XS1") (pin "19") (pintype "passive"))
    )
    (net (code "193") (name "/C192") (class "Default")
      (node (ref "VD1") (pin "200") (pinfunction "OUT200_200") (pintype "passive"))
      (node (ref "XS1") (pin "93") (pintype "passive"))
    )
    (net (code "194") (name "/C193") (class "Default")
      (node (ref "VD1") (pin "350") (pinfunction "OUT350_350") (pintype "passive"))
      (node (ref "XS1") (pin "83") (pintype "passive"))
    )
    (net (code "195") (name "/C194") (class "Default")
      (node (ref "VD1") (pin "351") (pinfunction "OUT351_351") (pintype "passive"))
      (node (ref "XS1") (pin "95") (pintype "passive"))
    )
    (net (code "196") (name "/C195") (class "Default")
      (node (ref "VD1") (pin "352") (pinfunction "OUT352_352") (pintype "passive"))
      (node (ref "XS1") (pin "20") (pintype "passive"))
    )
    (net (code "197") (name "/C196") (class "Default")
      (node (ref "VD1") (pin "322") (pinfunction "OUT322_322") (pintype "passive"))
      (node (ref "XS1") (pin "35") (pintype "passive"))
    )
    (net (code "198") (name "/C197") (class "Default")
      (node (ref "VD1") (pin "354") (pinfunction "OUT354_354") (pintype "passive"))
      (node (ref "XS1") (pin "84") (pintype "passive"))
    )
    (net (code "199") (name "/C198") (class "Default")
      (node (ref "VD1") (pin "330") (pinfunction "OUT330_330") (pintype "passive"))
      (node (ref "XS1") (pin "99") (pintype "passive"))
    )
    (net (code "200") (name "/C199") (class "Default")
      (node (ref "VD1") (pin "356") (pinfunction "OUT356_356") (pintype "passive"))
      (node (ref "XS1") (pin "21") (pintype "passive"))
    )
    (net (code "201") (name "GND") (class "Default")
      (node (ref "VD1") (pin "0") (pinfunction "GND_0") (pintype "passive"))
      (node (ref "XS1") (pin "101") (pintype "passive"))
      (node (ref "XS1") (pin "102") (pintype "passive"))
      (node (ref "XS2") (pin "101") (pintype "passive"))
      (node (ref "XS2") (pin "102") (pintype "passive"))
    )
    (net (code "202") (name "Net-(VD1E-BIAS0)") (class "Default")
      (node (ref "VD1") (pin "2500") (pinfunction "BIAS0_2500") (pintype "passive"))
      (node (ref "VD1") (pin "2501") (pinfunction "BIAS1_2501") (pintype "passive"))
      (node (ref "VD1") (pin "2502") (pinfunction "BIAS2_2502") (pintype "passive"))
      (node (ref "VD1") (pin "2503") (pinfunction "BIAS3_2503") (pintype "passive"))
      (node (ref "XS1") (pin "103") (pintype "passive"))
      (node (ref "XS1") (pin "104") (pintype "passive"))
      (node (ref "XS2") (pin "103") (pintype "passive"))
      (node (ref "XS2") (pin "104") (pintype "passive"))
    )
    (net (code "203") (name "unconnected-(VD1A-OUT1-Pad1)") (class "Default")
      (node (ref "VD1") (pin "1") (pinfunction "OUT1_1") (pintype "passive"))
    )
    (net (code "204") (name "unconnected-(VD1A-OUT2-Pad2)") (class "Default")
      (node (ref "VD1") (pin "2") (pinfunction "OUT2_2") (pintype "passive"))
    )
    (net (code "205") (name "unconnected-(VD1A-OUT3-Pad3)") (class "Default")
      (node (ref "VD1") (pin "3") (pinfunction "OUT3_3") (pintype "passive"))
    )
    (net (code "206") (name "unconnected-(VD1A-OUT5-Pad5)") (class "Default")
      (node (ref "VD1") (pin "5") (pinfunction "OUT5_5") (pintype "passive"))
    )
    (net (code "207") (name "unconnected-(VD1A-OUT6-Pad6)") (class "Default")
      (node (ref "VD1") (pin "6") (pinfunction "OUT6_6") (pintype "passive"))
    )
    (net (code "208") (name "unconnected-(VD1A-OUT7-Pad7)") (class "Default")
      (node (ref "VD1") (pin "7") (pinfunction "OUT7_7") (pintype "passive"))
    )
    (net (code "209") (name "unconnected-(VD1A-OUT8-Pad8)") (class "Default")
      (node (ref "VD1") (pin "8") (pinfunction "OUT8_8") (pintype "passive"))
    )
    (net (code "210") (name "unconnected-(VD1A-OUT9-Pad9)") (class "Default")
      (node (ref "VD1") (pin "9") (pinfunction "OUT9_9") (pintype "passive"))
    )
    (net (code "211") (name "unconnected-(VD1A-OUT10-Pad10)") (class "Default")
      (node (ref "VD1") (pin "10") (pinfunction "OUT10_10") (pintype "passive"))
    )
    (net (code "212") (name "unconnected-(VD1A-OUT11-Pad11)") (class "Default")
      (node (ref "VD1") (pin "11") (pinfunction "OUT11_11") (pintype "passive"))
    )
    (net (code "213") (name "unconnected-(VD1A-OUT12-Pad12)") (class "Default")
      (node (ref "VD1") (pin "12") (pinfunction "OUT12_12") (pintype "passive"))
    )
    (net (code "214") (name "unconnected-(VD1A-OUT13-Pad13)") (class "Default")
      (node (ref "VD1") (pin "13") (pinfunction "OUT13_13") (pintype "passive"))
    )
    (net (code "215") (name "unconnected-(VD1A-OUT14-Pad14)") (class "Default")
      (node (ref "VD1") (pin "14") (pinfunction "OUT14_14") (pintype "passive"))
    )
    (net (code "216") (name "unconnected-(VD1A-OUT15-Pad15)") (class "Default")
      (node (ref "VD1") (pin "15") (pinfunction "OUT15_15") (pintype "passive"))
    )
    (net (code "217") (name "unconnected-(VD1A-OUT16-Pad16)") (class "Default")
      (node (ref "VD1") (pin "16") (pinfunction "OUT16_16") (pintype "passive"))
    )
    (net (code "218") (name "unconnected-(VD1A-OUT17-Pad17)") (class "Default")
      (node (ref "VD1") (pin "17") (pinfunction "OUT17_17") (pintype "passive"))
    )
    (net (code "219") (name "unconnected-(VD1A-OUT18-Pad18)") (class "Default")
      (node (ref "VD1") (pin "18") (pinfunction "OUT18_18") (pintype "passive"))
    )
    (net (code "220") (name "unconnected-(VD1A-OUT19-Pad19)") (class "Default")
      (node (ref "VD1") (pin "19") (pinfunction "OUT19_19") (pintype "passive"))
    )
    (net (code "221") (name "unconnected-(VD1A-OUT20-Pad20)") (class "Default")
      (node (ref "VD1") (pin "20") (pinfunction "OUT20_20") (pintype "passive"))
    )
    (net (code "222") (name "unconnected-(VD1A-OUT21-Pad21)") (class "Default")
      (node (ref "VD1") (pin "21") (pinfunction "OUT21_21") (pintype "passive"))
    )
    (net (code "223") (name "unconnected-(VD1A-OUT22-Pad22)") (class "Default")
      (node (ref "VD1") (pin "22") (pinfunction "OUT22_22") (pintype "passive"))
    )
    (net (code "224") (name "unconnected-(VD1A-OUT23-Pad23)") (class "Default")
      (node (ref "VD1") (pin "23") (pinfunction "OUT23_23") (pintype "passive"))
    )
    (net (code "225") (name "unconnected-(VD1A-OUT24-Pad24)") (class "Default")
      (node (ref "VD1") (pin "24") (pinfunction "OUT24_24") (pintype "passive"))
    )
    (net (code "226") (name "unconnected-(VD1A-OUT25-Pad25)") (class "Default")
      (node (ref "VD1") (pin "25") (pinfunction "OUT25_25") (pintype "passive"))
    )
    (net (code "227") (name "unconnected-(VD1A-OUT26-Pad26)") (class "Default")
      (node (ref "VD1") (pin "26") (pinfunction "OUT26_26") (pintype "passive"))
    )
    (net (code "228") (name "unconnected-(VD1A-OUT27-Pad27)") (class "Default")
      (node (ref "VD1") (pin "27") (pinfunction "OUT27_27") (pintype "passive"))
    )
    (net (code "229") (name "unconnected-(VD1A-OUT28-Pad28)") (class "Default")
      (node (ref "VD1") (pin "28") (pinfunction "OUT28_28") (pintype "passive"))
    )
    (net (code "230") (name "unconnected-(VD1A-OUT29-Pad29)") (class "Default")
      (node (ref "VD1") (pin "29") (pinfunction "OUT29_29") (pintype "passive"))
    )
    (net (code "231") (name "unconnected-(VD1A-OUT30-Pad30)") (class "Default")
      (node (ref "VD1") (pin "30") (pinfunction "OUT30_30") (pintype "passive"))
    )
    (net (code "232") (name "unconnected-(VD1A-OUT31-Pad31)") (class "Default")
      (node (ref "VD1") (pin "31") (pinfunction "OUT31_31") (pintype "passive"))
    )
    (net (code "233") (name "unconnected-(VD1A-OUT32-Pad32)") (class "Default")
      (node (ref "VD1") (pin "32") (pinfunction "OUT32_32") (pintype "passive"))
    )
    (net (code "234") (name "unconnected-(VD1A-OUT33-Pad33)") (class "Default")
      (node (ref "VD1") (pin "33") (pinfunction "OUT33_33") (pintype "passive"))
    )
    (net (code "235") (name "unconnected-(VD1A-OUT34-Pad34)") (class "Default")
      (node (ref "VD1") (pin "34") (pinfunction "OUT34_34") (pintype "passive"))
    )
    (net (code "236") (name "unconnected-(VD1A-OUT35-Pad35)") (class "Default")
      (node (ref "VD1") (pin "35") (pinfunction "OUT35_35") (pintype "passive"))
    )
    (net (code "237") (name "unconnected-(VD1A-OUT36-Pad36)") (class "Default")
      (node (ref "VD1") (pin "36") (pinfunction "OUT36_36") (pintype "passive"))
    )
    (net (code "238") (name "unconnected-(VD1A-OUT37-Pad37)") (class "Default")
      (node (ref "VD1") (pin "37") (pinfunction "OUT37_37") (pintype "passive"))
    )
    (net (code "239") (name "unconnected-(VD1A-OUT38-Pad38)") (class "Default")
      (node (ref "VD1") (pin "38") (pinfunction "OUT38_38") (pintype "passive"))
    )
    (net (code "240") (name "unconnected-(VD1A-OUT39-Pad39)") (class "Default")
      (node (ref "VD1") (pin "39") (pinfunction "OUT39_39") (pintype "passive"))
    )
    (net (code "241") (name "unconnected-(VD1A-OUT40-Pad40)") (class "Default")
      (node (ref "VD1") (pin "40") (pinfunction "OUT40_40") (pintype "passive"))
    )
    (net (code "242") (name "unconnected-(VD1A-OUT41-Pad41)") (class "Default")
      (node (ref "VD1") (pin "41") (pinfunction "OUT41_41") (pintype "passive"))
    )
    (net (code "243") (name "unconnected-(VD1A-OUT42-Pad42)") (class "Default")
      (node (ref "VD1") (pin "42") (pinfunction "OUT42_42") (pintype "passive"))
    )
    (net (code "244") (name "unconnected-(VD1A-OUT43-Pad43)") (class "Default")
      (node (ref "VD1") (pin "43") (pinfunction "OUT43_43") (pintype "passive"))
    )
    (net (code "245") (name "unconnected-(VD1A-OUT44-Pad44)") (class "Default")
      (node (ref "VD1") (pin "44") (pinfunction "OUT44_44") (pintype "passive"))
    )
    (net (code "246") (name "unconnected-(VD1A-OUT45-Pad45)") (class "Default")
      (node (ref "VD1") (pin "45") (pinfunction "OUT45_45") (pintype "passive"))
    )
    (net (code "247") (name "unconnected-(VD1A-OUT46-Pad46)") (class "Default")
      (node (ref "VD1") (pin "46") (pinfunction "OUT46_46") (pintype "passive"))
    )
    (net (code "248") (name "unconnected-(VD1A-OUT47-Pad47)") (class "Default")
      (node (ref "VD1") (pin "47") (pinfunction "OUT47_47") (pintype "passive"))
    )
    (net (code "249") (name "unconnected-(VD1A-OUT48-Pad48)") (class "Default")
      (node (ref "VD1") (pin "48") (pinfunction "OUT48_48") (pintype "passive"))
    )
    (net (code "250") (name "unconnected-(VD1A-OUT49-Pad49)") (class "Default")
      (node (ref "VD1") (pin "49") (pinfunction "OUT49_49") (pintype "passive"))
    )
    (net (code "251") (name "unconnected-(VD1A-OUT50-Pad50)") (class "Default")
      (node (ref "VD1") (pin "50") (pinfunction "OUT50_50") (pintype "passive"))
    )
    (net (code "252") (name "unconnected-(VD1A-OUT51-Pad51)") (class "Default")
      (node (ref "VD1") (pin "51") (pinfunction "OUT51_51") (pintype "passive"))
    )
    (net (code "253") (name "unconnected-(VD1A-OUT52-Pad52)") (class "Default")
      (node (ref "VD1") (pin "52") (pinfunction "OUT52_52") (pintype "passive"))
    )
    (net (code "254") (name "unconnected-(VD1A-OUT53-Pad53)") (class "Default")
      (node (ref "VD1") (pin "53") (pinfunction "OUT53_53") (pintype "passive"))
    )
    (net (code "255") (name "unconnected-(VD1A-OUT54-Pad54)") (class "Default")
      (node (ref "VD1") (pin "54") (pinfunction "OUT54_54") (pintype "passive"))
    )
    (net (code "256") (name "unconnected-(VD1A-OUT55-Pad55)") (class "Default")
      (node (ref "VD1") (pin "55") (pinfunction "OUT55_55") (pintype "passive"))
    )
    (net (code "257") (name "unconnected-(VD1A-OUT56-Pad56)") (class "Default")
      (node (ref "VD1") (pin "56") (pinfunction "OUT56_56") (pintype "passive"))
    )
    (net (code "258") (name "unconnected-(VD1A-OUT57-Pad57)") (class "Default")
      (node (ref "VD1") (pin "57") (pinfunction "OUT57_57") (pintype "passive"))
    )
    (net (code "259") (name "unconnected-(VD1A-OUT58-Pad58)") (class "Default")
      (node (ref "VD1") (pin "58") (pinfunction "OUT58_58") (pintype "passive"))
    )
    (net (code "260") (name "unconnected-(VD1A-OUT59-Pad59)") (class "Default")
      (node (ref "VD1") (pin "59") (pinfunction "OUT59_59") (pintype "passive"))
    )
    (net (code "261") (name "unconnected-(VD1A-OUT60-Pad60)") (class "Default")
      (node (ref "VD1") (pin "60") (pinfunction "OUT60_60") (pintype "passive"))
    )
    (net (code "262") (name "unconnected-(VD1A-OUT61-Pad61)") (class "Default")
      (node (ref "VD1") (pin "61") (pinfunction "OUT61_61") (pintype "passive"))
    )
    (net (code "263") (name "unconnected-(VD1A-OUT62-Pad62)") (class "Default")
      (node (ref "VD1") (pin "62") (pinfunction "OUT62_62") (pintype "passive"))
    )
    (net (code "264") (name "unconnected-(VD1A-OUT63-Pad63)") (class "Default")
      (node (ref "VD1") (pin "63") (pinfunction "OUT63_63") (pintype "passive"))
    )
    (net (code "265") (name "unconnected-(VD1A-OUT64-Pad64)") (class "Default")
      (node (ref "VD1") (pin "64") (pinfunction "OUT64_64") (pintype "passive"))
    )
    (net (code "266") (name "unconnected-(VD1A-OUT65-Pad65)") (class "Default")
      (node (ref "VD1") (pin "65") (pinfunction "OUT65_65") (pintype "passive"))
    )
    (net (code "267") (name "unconnected-(VD1A-OUT66-Pad66)") (class "Default")
      (node (ref "VD1") (pin "66") (pinfunction "OUT66_66") (pintype "passive"))
    )
    (net (code "268") (name "unconnected-(VD1A-OUT67-Pad67)") (class "Default")
      (node (ref "VD1") (pin "67") (pinfunction "OUT67_67") (pintype "passive"))
    )
    (net (code "269") (name "unconnected-(VD1A-OUT68-Pad68)") (class "Default")
      (node (ref "VD1") (pin "68") (pinfunction "OUT68_68") (pintype "passive"))
    )
    (net (code "270") (name "unconnected-(VD1A-OUT69-Pad69)") (class "Default")
      (node (ref "VD1") (pin "69") (pinfunction "OUT69_69") (pintype "passive"))
    )
    (net (code "271") (name "unconnected-(VD1A-OUT70-Pad70)") (class "Default")
      (node (ref "VD1") (pin "70") (pinfunction "OUT70_70") (pintype "passive"))
    )
    (net (code "272") (name "unconnected-(VD1A-OUT71-Pad71)") (class "Default")
      (node (ref "VD1") (pin "71") (pinfunction "OUT71_71") (pintype "passive"))
    )
    (net (code "273") (name "unconnected-(VD1A-OUT72-Pad72)") (class "Default")
      (node (ref "VD1") (pin "72") (pinfunction "OUT72_72") (pintype "passive"))
    )
    (net (code "274") (name "unconnected-(VD1A-OUT73-Pad73)") (class "Default")
      (node (ref "VD1") (pin "73") (pinfunction "OUT73_73") (pintype "passive"))
    )
    (net (code "275") (name "unconnected-(VD1A-OUT74-Pad74)") (class "Default")
      (node (ref "VD1") (pin "74") (pinfunction "OUT74_74") (pintype "passive"))
    )
    (net (code "276") (name "unconnected-(VD1A-OUT75-Pad75)") (class "Default")
      (node (ref "VD1") (pin "75") (pinfunction "OUT75_75") (pintype "passive"))
    )
    (net (code "277") (name "unconnected-(VD1A-OUT76-Pad76)") (class "Default")
      (node (ref "VD1") (pin "76") (pinfunction "OUT76_76") (pintype "passive"))
    )
    (net (code "278") (name "unconnected-(VD1A-OUT77-Pad77)") (class "Default")
      (node (ref "VD1") (pin "77") (pinfunction "OUT77_77") (pintype "passive"))
    )
    (net (code "279") (name "unconnected-(VD1A-OUT78-Pad78)") (class "Default")
      (node (ref "VD1") (pin "78") (pinfunction "OUT78_78") (pintype "passive"))
    )
    (net (code "280") (name "unconnected-(VD1A-OUT79-Pad79)") (class "Default")
      (node (ref "VD1") (pin "79") (pinfunction "OUT79_79") (pintype "passive"))
    )
    (net (code "281") (name "unconnected-(VD1A-OUT80-Pad80)") (class "Default")
      (node (ref "VD1") (pin "80") (pinfunction "OUT80_80") (pintype "passive"))
    )
    (net (code "282") (name "unconnected-(VD1A-OUT81-Pad81)") (class "Default")
      (node (ref "VD1") (pin "81") (pinfunction "OUT81_81") (pintype "passive"))
    )
    (net (code "283") (name "unconnected-(VD1A-OUT82-Pad82)") (class "Default")
      (node (ref "VD1") (pin "82") (pinfunction "OUT82_82") (pintype "passive"))
    )
    (net (code "284") (name "unconnected-(VD1A-OUT83-Pad83)") (class "Default")
      (node (ref "VD1") (pin "83") (pinfunction "OUT83_83") (pintype "passive"))
    )
    (net (code "285") (name "unconnected-(VD1A-OUT84-Pad84)") (class "Default")
      (node (ref "VD1") (pin "84") (pinfunction "OUT84_84") (pintype "passive"))
    )
    (net (code "286") (name "unconnected-(VD1A-OUT85-Pad85)") (class "Default")
      (node (ref "VD1") (pin "85") (pinfunction "OUT85_85") (pintype "passive"))
    )
    (net (code "287") (name "unconnected-(VD1A-OUT86-Pad86)") (class "Default")
      (node (ref "VD1") (pin "86") (pinfunction "OUT86_86") (pintype "passive"))
    )
    (net (code "288") (name "unconnected-(VD1A-OUT87-Pad87)") (class "Default")
      (node (ref "VD1") (pin "87") (pinfunction "OUT87_87") (pintype "passive"))
    )
    (net (code "289") (name "unconnected-(VD1A-OUT88-Pad88)") (class "Default")
      (node (ref "VD1") (pin "88") (pinfunction "OUT88_88") (pintype "passive"))
    )
    (net (code "290") (name "unconnected-(VD1A-OUT89-Pad89)") (class "Default")
      (node (ref "VD1") (pin "89") (pinfunction "OUT89_89") (pintype "passive"))
    )
    (net (code "291") (name "unconnected-(VD1A-OUT90-Pad90)") (class "Default")
      (node (ref "VD1") (pin "90") (pinfunction "OUT90_90") (pintype "passive"))
    )
    (net (code "292") (name "unconnected-(VD1A-OUT91-Pad91)") (class "Default")
      (node (ref "VD1") (pin "91") (pinfunction "OUT91_91") (pintype "passive"))
    )
    (net (code "293") (name "unconnected-(VD1A-OUT92-Pad92)") (class "Default")
      (node (ref "VD1") (pin "92") (pinfunction "OUT92_92") (pintype "passive"))
    )
    (net (code "294") (name "unconnected-(VD1A-OUT93-Pad93)") (class "Default")
      (node (ref "VD1") (pin "93") (pinfunction "OUT93_93") (pintype "passive"))
    )
    (net (code "295") (name "unconnected-(VD1A-OUT94-Pad94)") (class "Default")
      (node (ref "VD1") (pin "94") (pinfunction "OUT94_94") (pintype "passive"))
    )
    (net (code "296") (name "unconnected-(VD1A-OUT95-Pad95)") (class "Default")
      (node (ref "VD1") (pin "95") (pinfunction "OUT95_95") (pintype "passive"))
    )
    (net (code "297") (name "unconnected-(VD1A-OUT96-Pad96)") (class "Default")
      (node (ref "VD1") (pin "96") (pinfunction "OUT96_96") (pintype "passive"))
    )
    (net (code "298") (name "unconnected-(VD1A-OUT97-Pad97)") (class "Default")
      (node (ref "VD1") (pin "97") (pinfunction "OUT97_97") (pintype "passive"))
    )
    (net (code "299") (name "unconnected-(VD1A-OUT98-Pad98)") (class "Default")
      (node (ref "VD1") (pin "98") (pinfunction "OUT98_98") (pintype "passive"))
    )
    (net (code "300") (name "unconnected-(VD1A-OUT99-Pad99)") (class "Default")
      (node (ref "VD1") (pin "99") (pinfunction "OUT99_99") (pintype "passive"))
    )
    (net (code "301") (name "unconnected-(VD1A-OUT100-Pad100)") (class "Default")
      (node (ref "VD1") (pin "100") (pinfunction "OUT100_100") (pintype "passive"))
    )
    (net (code "302") (name "unconnected-(VD1A-OUT101-Pad101)") (class "Default")
      (node (ref "VD1") (pin "101") (pinfunction "OUT101_101") (pintype "passive"))
    )
    (net (code "303") (name "unconnected-(VD1A-OUT102-Pad102)") (class "Default")
      (node (ref "VD1") (pin "102") (pinfunction "OUT102_102") (pintype "passive"))
    )
    (net (code "304") (name "unconnected-(VD1A-OUT103-Pad103)") (class "Default")
      (node (ref "VD1") (pin "103") (pinfunction "OUT103_103") (pintype "passive"))
    )
    (net (code "305") (name "unconnected-(VD1A-OUT104-Pad104)") (class "Default")
      (node (ref "VD1") (pin "104") (pinfunction "OUT104_104") (pintype "passive"))
    )
    (net (code "306") (name "unconnected-(VD1A-OUT105-Pad105)") (class "Default")
      (node (ref "VD1") (pin "105") (pinfunction "OUT105_105") (pintype "passive"))
    )
    (net (code "307") (name "unconnected-(VD1A-OUT106-Pad106)") (class "Default")
      (node (ref "VD1") (pin "106") (pinfunction "OUT106_106") (pintype "passive"))
    )
    (net (code "308") (name "unconnected-(VD1A-OUT107-Pad107)") (class "Default")
      (node (ref "VD1") (pin "107") (pinfunction "OUT107_107") (pintype "passive"))
    )
    (net (code "309") (name "unconnected-(VD1A-OUT108-Pad108)") (class "Default")
      (node (ref "VD1") (pin "108") (pinfunction "OUT108_108") (pintype "passive"))
    )
    (net (code "310") (name "unconnected-(VD1A-OUT109-Pad109)") (class "Default")
      (node (ref "VD1") (pin "109") (pinfunction "OUT109_109") (pintype "passive"))
    )
    (net (code "311") (name "unconnected-(VD1A-OUT110-Pad110)") (class "Default")
      (node (ref "VD1") (pin "110") (pinfunction "OUT110_110") (pintype "passive"))
    )
    (net (code "312") (name "unconnected-(VD1A-OUT111-Pad111)") (class "Default")
      (node (ref "VD1") (pin "111") (pinfunction "OUT111_111") (pintype "passive"))
    )
    (net (code "313") (name "unconnected-(VD1A-OUT112-Pad112)") (class "Default")
      (node (ref "VD1") (pin "112") (pinfunction "OUT112_112") (pintype "passive"))
    )
    (net (code "314") (name "unconnected-(VD1A-OUT113-Pad113)") (class "Default")
      (node (ref "VD1") (pin "113") (pinfunction "OUT113_113") (pintype "passive"))
    )
    (net (code "315") (name "unconnected-(VD1A-OUT114-Pad114)") (class "Default")
      (node (ref "VD1") (pin "114") (pinfunction "OUT114_114") (pintype "passive"))
    )
    (net (code "316") (name "unconnected-(VD1A-OUT115-Pad115)") (class "Default")
      (node (ref "VD1") (pin "115") (pinfunction "OUT115_115") (pintype "passive"))
    )
    (net (code "317") (name "unconnected-(VD1A-OUT116-Pad116)") (class "Default")
      (node (ref "VD1") (pin "116") (pinfunction "OUT116_116") (pintype "passive"))
    )
    (net (code "318") (name "unconnected-(VD1A-OUT117-Pad117)") (class "Default")
      (node (ref "VD1") (pin "117") (pinfunction "OUT117_117") (pintype "passive"))
    )
    (net (code "319") (name "unconnected-(VD1A-OUT118-Pad118)") (class "Default")
      (node (ref "VD1") (pin "118") (pinfunction "OUT118_118") (pintype "passive"))
    )
    (net (code "320") (name "unconnected-(VD1A-OUT119-Pad119)") (class "Default")
      (node (ref "VD1") (pin "119") (pinfunction "OUT119_119") (pintype "passive"))
    )
    (net (code "321") (name "unconnected-(VD1A-OUT120-Pad120)") (class "Default")
      (node (ref "VD1") (pin "120") (pinfunction "OUT120_120") (pintype "passive"))
    )
    (net (code "322") (name "unconnected-(VD1A-OUT121-Pad121)") (class "Default")
      (node (ref "VD1") (pin "121") (pinfunction "OUT121_121") (pintype "passive"))
    )
    (net (code "323") (name "unconnected-(VD1A-OUT122-Pad122)") (class "Default")
      (node (ref "VD1") (pin "122") (pinfunction "OUT122_122") (pintype "passive"))
    )
    (net (code "324") (name "unconnected-(VD1A-OUT123-Pad123)") (class "Default")
      (node (ref "VD1") (pin "123") (pinfunction "OUT123_123") (pintype "passive"))
    )
    (net (code "325") (name "unconnected-(VD1A-OUT124-Pad124)") (class "Default")
      (node (ref "VD1") (pin "124") (pinfunction "OUT124_124") (pintype "passive"))
    )
    (net (code "326") (name "unconnected-(VD1A-OUT125-Pad125)") (class "Default")
      (node (ref "VD1") (pin "125") (pinfunction "OUT125_125") (pintype "passive"))
    )
    (net (code "327") (name "unconnected-(VD1A-OUT126-Pad126)") (class "Default")
      (node (ref "VD1") (pin "126") (pinfunction "OUT126_126") (pintype "passive"))
    )
    (net (code "328") (name "unconnected-(VD1A-OUT127-Pad127)") (class "Default")
      (node (ref "VD1") (pin "127") (pinfunction "OUT127_127") (pintype "passive"))
    )
    (net (code "329") (name "unconnected-(VD1A-OUT128-Pad128)") (class "Default")
      (node (ref "VD1") (pin "128") (pinfunction "OUT128_128") (pintype "passive"))
    )
    (net (code "330") (name "unconnected-(VD1A-OUT129-Pad129)") (class "Default")
      (node (ref "VD1") (pin "129") (pinfunction "OUT129_129") (pintype "passive"))
    )
    (net (code "331") (name "unconnected-(VD1A-OUT130-Pad130)") (class "Default")
      (node (ref "VD1") (pin "130") (pinfunction "OUT130_130") (pintype "passive"))
    )
    (net (code "332") (name "unconnected-(VD1A-OUT131-Pad131)") (class "Default")
      (node (ref "VD1") (pin "131") (pinfunction "OUT131_131") (pintype "passive"))
    )
    (net (code "333") (name "unconnected-(VD1A-OUT132-Pad132)") (class "Default")
      (node (ref "VD1") (pin "132") (pinfunction "OUT132_132") (pintype "passive"))
    )
    (net (code "334") (name "unconnected-(VD1A-OUT133-Pad133)") (class "Default")
      (node (ref "VD1") (pin "133") (pinfunction "OUT133_133") (pintype "passive"))
    )
    (net (code "335") (name "unconnected-(VD1A-OUT134-Pad134)") (class "Default")
      (node (ref "VD1") (pin "134") (pinfunction "OUT134_134") (pintype "passive"))
    )
    (net (code "336") (name "unconnected-(VD1A-OUT135-Pad135)") (class "Default")
      (node (ref "VD1") (pin "135") (pinfunction "OUT135_135") (pintype "passive"))
    )
    (net (code "337") (name "unconnected-(VD1A-OUT136-Pad136)") (class "Default")
      (node (ref "VD1") (pin "136") (pinfunction "OUT136_136") (pintype "passive"))
    )
    (net (code "338") (name "unconnected-(VD1A-OUT137-Pad137)") (class "Default")
      (node (ref "VD1") (pin "137") (pinfunction "OUT137_137") (pintype "passive"))
    )
    (net (code "339") (name "unconnected-(VD1A-OUT138-Pad138)") (class "Default")
      (node (ref "VD1") (pin "138") (pinfunction "OUT138_138") (pintype "passive"))
    )
    (net (code "340") (name "unconnected-(VD1A-OUT139-Pad139)") (class "Default")
      (node (ref "VD1") (pin "139") (pinfunction "OUT139_139") (pintype "passive"))
    )
    (net (code "341") (name "unconnected-(VD1A-OUT140-Pad140)") (class "Default")
      (node (ref "VD1") (pin "140") (pinfunction "OUT140_140") (pintype "passive"))
    )
    (net (code "342") (name "unconnected-(VD1A-OUT141-Pad141)") (class "Default")
      (node (ref "VD1") (pin "141") (pinfunction "OUT141_141") (pintype "passive"))
    )
    (net (code "343") (name "unconnected-(VD1A-OUT142-Pad142)") (class "Default")
      (node (ref "VD1") (pin "142") (pinfunction "OUT142_142") (pintype "passive"))
    )
    (net (code "344") (name "unconnected-(VD1A-OUT143-Pad143)") (class "Default")
      (node (ref "VD1") (pin "143") (pinfunction "OUT143_143") (pintype "passive"))
    )
    (net (code "345") (name "unconnected-(VD1A-OUT144-Pad144)") (class "Default")
      (node (ref "VD1") (pin "144") (pinfunction "OUT144_144") (pintype "passive"))
    )
    (net (code "346") (name "unconnected-(VD1A-OUT145-Pad145)") (class "Default")
      (node (ref "VD1") (pin "145") (pinfunction "OUT145_145") (pintype "passive"))
    )
    (net (code "347") (name "unconnected-(VD1A-OUT146-Pad146)") (class "Default")
      (node (ref "VD1") (pin "146") (pinfunction "OUT146_146") (pintype "passive"))
    )
    (net (code "348") (name "unconnected-(VD1A-OUT147-Pad147)") (class "Default")
      (node (ref "VD1") (pin "147") (pinfunction "OUT147_147") (pintype "passive"))
    )
    (net (code "349") (name "unconnected-(VD1A-OUT148-Pad148)") (class "Default")
      (node (ref "VD1") (pin "148") (pinfunction "OUT148_148") (pintype "passive"))
    )
    (net (code "350") (name "unconnected-(VD1A-OUT149-Pad149)") (class "Default")
      (node (ref "VD1") (pin "149") (pinfunction "OUT149_149") (pintype "passive"))
    )
    (net (code "351") (name "unconnected-(VD1A-OUT150-Pad150)") (class "Default")
      (node (ref "VD1") (pin "150") (pinfunction "OUT150_150") (pintype "passive"))
    )
    (net (code "352") (name "unconnected-(VD1A-OUT151-Pad151)") (class "Default")
      (node (ref "VD1") (pin "151") (pinfunction "OUT151_151") (pintype "passive"))
    )
    (net (code "353") (name "unconnected-(VD1A-OUT152-Pad152)") (class "Default")
      (node (ref "VD1") (pin "152") (pinfunction "OUT152_152") (pintype "passive"))
    )
    (net (code "354") (name "unconnected-(VD1A-OUT153-Pad153)") (class "Default")
      (node (ref "VD1") (pin "153") (pinfunction "OUT153_153") (pintype "passive"))
    )
    (net (code "355") (name "unconnected-(VD1A-OUT154-Pad154)") (class "Default")
      (node (ref "VD1") (pin "154") (pinfunction "OUT154_154") (pintype "passive"))
    )
    (net (code "356") (name "unconnected-(VD1A-OUT155-Pad155)") (class "Default")
      (node (ref "VD1") (pin "155") (pinfunction "OUT155_155") (pintype "passive"))
    )
    (net (code "357") (name "unconnected-(VD1A-OUT156-Pad156)") (class "Default")
      (node (ref "VD1") (pin "156") (pinfunction "OUT156_156") (pintype "passive"))
    )
    (net (code "358") (name "unconnected-(VD1A-OUT310-Pad310)") (class "Default")
      (node (ref "VD1") (pin "310") (pinfunction "OUT310_310") (pintype "passive"))
    )
    (net (code "359") (name "unconnected-(VD1B-OUT357-Pad357)") (class "Default")
      (node (ref "VD1") (pin "357") (pinfunction "OUT357_357") (pintype "passive"))
    )
    (net (code "360") (name "unconnected-(VD1B-OUT358-Pad358)") (class "Default")
      (node (ref "VD1") (pin "358") (pinfunction "OUT358_358") (pintype "passive"))
    )
    (net (code "361") (name "unconnected-(VD1B-OUT359-Pad359)") (class "Default")
      (node (ref "VD1") (pin "359") (pinfunction "OUT359_359") (pintype "passive"))
    )
    (net (code "362") (name "unconnected-(VD1B-OUT360-Pad360)") (class "Default")
      (node (ref "VD1") (pin "360") (pinfunction "OUT360_360") (pintype "passive"))
    )
    (net (code "363") (name "unconnected-(VD1B-OUT361-Pad361)") (class "Default")
      (node (ref "VD1") (pin "361") (pinfunction "OUT361_361") (pintype "passive"))
    )
    (net (code "364") (name "unconnected-(VD1B-OUT362-Pad362)") (class "Default")
      (node (ref "VD1") (pin "362") (pinfunction "OUT362_362") (pintype "passive"))
    )
    (net (code "365") (name "unconnected-(VD1B-OUT363-Pad363)") (class "Default")
      (node (ref "VD1") (pin "363") (pinfunction "OUT363_363") (pintype "passive"))
    )
    (net (code "366") (name "unconnected-(VD1B-OUT364-Pad364)") (class "Default")
      (node (ref "VD1") (pin "364") (pinfunction "OUT364_364") (pintype "passive"))
    )
    (net (code "367") (name "unconnected-(VD1B-OUT365-Pad365)") (class "Default")
      (node (ref "VD1") (pin "365") (pinfunction "OUT365_365") (pintype "passive"))
    )
    (net (code "368") (name "unconnected-(VD1B-OUT366-Pad366)") (class "Default")
      (node (ref "VD1") (pin "366") (pinfunction "OUT366_366") (pintype "passive"))
    )
    (net (code "369") (name "unconnected-(VD1B-OUT367-Pad367)") (class "Default")
      (node (ref "VD1") (pin "367") (pinfunction "OUT367_367") (pintype "passive"))
    )
    (net (code "370") (name "unconnected-(VD1B-OUT368-Pad368)") (class "Default")
      (node (ref "VD1") (pin "368") (pinfunction "OUT368_368") (pintype "passive"))
    )
    (net (code "371") (name "unconnected-(VD1B-OUT369-Pad369)") (class "Default")
      (node (ref "VD1") (pin "369") (pinfunction "OUT369_369") (pintype "passive"))
    )
    (net (code "372") (name "unconnected-(VD1B-OUT370-Pad370)") (class "Default")
      (node (ref "VD1") (pin "370") (pinfunction "OUT370_370") (pintype "passive"))
    )
    (net (code "373") (name "unconnected-(VD1B-OUT371-Pad371)") (class "Default")
      (node (ref "VD1") (pin "371") (pinfunction "OUT371_371") (pintype "passive"))
    )
    (net (code "374") (name "unconnected-(VD1B-OUT372-Pad372)") (class "Default")
      (node (ref "VD1") (pin "372") (pinfunction "OUT372_372") (pintype "passive"))
    )
    (net (code "375") (name "unconnected-(VD1B-OUT373-Pad373)") (class "Default")
      (node (ref "VD1") (pin "373") (pinfunction "OUT373_373") (pintype "passive"))
    )
    (net (code "376") (name "unconnected-(VD1B-OUT374-Pad374)") (class "Default")
      (node (ref "VD1") (pin "374") (pinfunction "OUT374_374") (pintype "passive"))
    )
    (net (code "377") (name "unconnected-(VD1B-OUT375-Pad375)") (class "Default")
      (node (ref "VD1") (pin "375") (pinfunction "OUT375_375") (pintype "passive"))
    )
    (net (code "378") (name "unconnected-(VD1B-OUT376-Pad376)") (class "Default")
      (node (ref "VD1") (pin "376") (pinfunction "OUT376_376") (pintype "passive"))
    )
    (net (code "379") (name "unconnected-(VD1B-OUT377-Pad377)") (class "Default")
      (node (ref "VD1") (pin "377") (pinfunction "OUT377_377") (pintype "passive"))
    )
    (net (code "380") (name "unconnected-(VD1B-OUT378-Pad378)") (class "Default")
      (node (ref "VD1") (pin "378") (pinfunction "OUT378_378") (pintype "passive"))
    )
    (net (code "381") (name "unconnected-(VD1B-OUT379-Pad379)") (class "Default")
      (node (ref "VD1") (pin "379") (pinfunction "OUT379_379") (pintype "passive"))
    )
    (net (code "382") (name "unconnected-(VD1B-OUT380-Pad380)") (class "Default")
      (node (ref "VD1") (pin "380") (pinfunction "OUT380_380") (pintype "passive"))
    )
    (net (code "383") (name "unconnected-(VD1B-OUT381-Pad381)") (class "Default")
      (node (ref "VD1") (pin "381") (pinfunction "OUT381_381") (pintype "passive"))
    )
    (net (code "384") (name "unconnected-(VD1B-OUT382-Pad382)") (class "Default")
      (node (ref "VD1") (pin "382") (pinfunction "OUT382_382") (pintype "passive"))
    )
    (net (code "385") (name "unconnected-(VD1B-OUT383-Pad383)") (class "Default")
      (node (ref "VD1") (pin "383") (pinfunction "OUT383_383") (pintype "passive"))
    )
    (net (code "386") (name "unconnected-(VD1B-OUT384-Pad384)") (class "Default")
      (node (ref "VD1") (pin "384") (pinfunction "OUT384_384") (pintype "passive"))
    )
    (net (code "387") (name "unconnected-(VD1B-OUT385-Pad385)") (class "Default")
      (node (ref "VD1") (pin "385") (pinfunction "OUT385_385") (pintype "passive"))
    )
    (net (code "388") (name "unconnected-(VD1B-OUT386-Pad386)") (class "Default")
      (node (ref "VD1") (pin "386") (pinfunction "OUT386_386") (pintype "passive"))
    )
    (net (code "389") (name "unconnected-(VD1B-OUT387-Pad387)") (class "Default")
      (node (ref "VD1") (pin "387") (pinfunction "OUT387_387") (pintype "passive"))
    )
    (net (code "390") (name "unconnected-(VD1B-OUT388-Pad388)") (class "Default")
      (node (ref "VD1") (pin "388") (pinfunction "OUT388_388") (pintype "passive"))
    )
    (net (code "391") (name "unconnected-(VD1B-OUT389-Pad389)") (class "Default")
      (node (ref "VD1") (pin "389") (pinfunction "OUT389_389") (pintype "passive"))
    )
    (net (code "392") (name "unconnected-(VD1B-OUT390-Pad390)") (class "Default")
      (node (ref "VD1") (pin "390") (pinfunction "OUT390_390") (pintype "passive"))
    )
    (net (code "393") (name "unconnected-(VD1B-OUT391-Pad391)") (class "Default")
      (node (ref "VD1") (pin "391") (pinfunction "OUT391_391") (pintype "passive"))
    )
    (net (code "394") (name "unconnected-(VD1B-OUT392-Pad392)") (class "Default")
      (node (ref "VD1") (pin "392") (pinfunction "OUT392_392") (pintype "passive"))
    )
    (net (code "395") (name "unconnected-(VD1B-OUT393-Pad393)") (class "Default")
      (node (ref "VD1") (pin "393") (pinfunction "OUT393_393") (pintype "passive"))
    )
    (net (code "396") (name "unconnected-(VD1B-OUT394-Pad394)") (class "Default")
      (node (ref "VD1") (pin "394") (pinfunction "OUT394_394") (pintype "passive"))
    )
    (net (code "397") (name "unconnected-(VD1B-OUT395-Pad395)") (class "Default")
      (node (ref "VD1") (pin "395") (pinfunction "OUT395_395") (pintype "passive"))
    )
    (net (code "398") (name "unconnected-(VD1B-OUT396-Pad396)") (class "Default")
      (node (ref "VD1") (pin "396") (pinfunction "OUT396_396") (pintype "passive"))
    )
    (net (code "399") (name "unconnected-(VD1B-OUT397-Pad397)") (class "Default")
      (node (ref "VD1") (pin "397") (pinfunction "OUT397_397") (pintype "passive"))
    )
    (net (code "400") (name "unconnected-(VD1B-OUT398-Pad398)") (class "Default")
      (node (ref "VD1") (pin "398") (pinfunction "OUT398_398") (pintype "passive"))
    )
    (net (code "401") (name "unconnected-(VD1B-OUT399-Pad399)") (class "Default")
      (node (ref "VD1") (pin "399") (pinfunction "OUT399_399") (pintype "passive"))
    )
    (net (code "402") (name "unconnected-(VD1B-OUT400-Pad400)") (class "Default")
      (node (ref "VD1") (pin "400") (pinfunction "OUT400_400") (pintype "passive"))
    )
    (net (code "403") (name "unconnected-(VD1B-OUT401-Pad401)") (class "Default")
      (node (ref "VD1") (pin "401") (pinfunction "OUT401_401") (pintype "passive"))
    )
    (net (code "404") (name "unconnected-(VD1B-OUT402-Pad402)") (class "Default")
      (node (ref "VD1") (pin "402") (pinfunction "OUT402_402") (pintype "passive"))
    )
    (net (code "405") (name "unconnected-(VD1B-OUT403-Pad403)") (class "Default")
      (node (ref "VD1") (pin "403") (pinfunction "OUT403_403") (pintype "passive"))
    )
    (net (code "406") (name "unconnected-(VD1B-OUT404-Pad404)") (class "Default")
      (node (ref "VD1") (pin "404") (pinfunction "OUT404_404") (pintype "passive"))
    )
    (net (code "407") (name "unconnected-(VD1B-OUT405-Pad405)") (class "Default")
      (node (ref "VD1") (pin "405") (pinfunction "OUT405_405") (pintype "passive"))
    )
    (net (code "408") (name "unconnected-(VD1B-OUT406-Pad406)") (class "Default")
      (node (ref "VD1") (pin "406") (pinfunction "OUT406_406") (pintype "passive"))
    )
    (net (code "409") (name "unconnected-(VD1B-OUT407-Pad407)") (class "Default")
      (node (ref "VD1") (pin "407") (pinfunction "OUT407_407") (pintype "passive"))
    )
    (net (code "410") (name "unconnected-(VD1B-OUT408-Pad408)") (class "Default")
      (node (ref "VD1") (pin "408") (pinfunction "OUT408_408") (pintype "passive"))
    )
    (net (code "411") (name "unconnected-(VD1B-OUT409-Pad409)") (class "Default")
      (node (ref "VD1") (pin "409") (pinfunction "OUT409_409") (pintype "passive"))
    )
    (net (code "412") (name "unconnected-(VD1B-OUT410-Pad410)") (class "Default")
      (node (ref "VD1") (pin "410") (pinfunction "OUT410_410") (pintype "passive"))
    )
    (net (code "413") (name "unconnected-(VD1B-OUT411-Pad411)") (class "Default")
      (node (ref "VD1") (pin "411") (pinfunction "OUT411_411") (pintype "passive"))
    )
    (net (code "414") (name "unconnected-(VD1B-OUT412-Pad412)") (class "Default")
      (node (ref "VD1") (pin "412") (pinfunction "OUT412_412") (pintype "passive"))
    )
    (net (code "415") (name "unconnected-(VD1B-OUT413-Pad413)") (class "Default")
      (node (ref "VD1") (pin "413") (pinfunction "OUT413_413") (pintype "passive"))
    )
    (net (code "416") (name "unconnected-(VD1B-OUT414-Pad414)") (class "Default")
      (node (ref "VD1") (pin "414") (pinfunction "OUT414_414") (pintype "passive"))
    )
    (net (code "417") (name "unconnected-(VD1B-OUT415-Pad415)") (class "Default")
      (node (ref "VD1") (pin "415") (pinfunction "OUT415_415") (pintype "passive"))
    )
    (net (code "418") (name "unconnected-(VD1B-OUT416-Pad416)") (class "Default")
      (node (ref "VD1") (pin "416") (pinfunction "OUT416_416") (pintype "passive"))
    )
    (net (code "419") (name "unconnected-(VD1B-OUT417-Pad417)") (class "Default")
      (node (ref "VD1") (pin "417") (pinfunction "OUT417_417") (pintype "passive"))
    )
    (net (code "420") (name "unconnected-(VD1B-OUT418-Pad418)") (class "Default")
      (node (ref "VD1") (pin "418") (pinfunction "OUT418_418") (pintype "passive"))
    )
    (net (code "421") (name "unconnected-(VD1B-OUT419-Pad419)") (class "Default")
      (node (ref "VD1") (pin "419") (pinfunction "OUT419_419") (pintype "passive"))
    )
    (net (code "422") (name "unconnected-(VD1B-OUT420-Pad420)") (class "Default")
      (node (ref "VD1") (pin "420") (pinfunction "OUT420_420") (pintype "passive"))
    )
    (net (code "423") (name "unconnected-(VD1B-OUT421-Pad421)") (class "Default")
      (node (ref "VD1") (pin "421") (pinfunction "OUT421_421") (pintype "passive"))
    )
    (net (code "424") (name "unconnected-(VD1B-OUT422-Pad422)") (class "Default")
      (node (ref "VD1") (pin "422") (pinfunction "OUT422_422") (pintype "passive"))
    )
    (net (code "425") (name "unconnected-(VD1B-OUT423-Pad423)") (class "Default")
      (node (ref "VD1") (pin "423") (pinfunction "OUT423_423") (pintype "passive"))
    )
    (net (code "426") (name "unconnected-(VD1B-OUT424-Pad424)") (class "Default")
      (node (ref "VD1") (pin "424") (pinfunction "OUT424_424") (pintype "passive"))
    )
    (net (code "427") (name "unconnected-(VD1B-OUT425-Pad425)") (class "Default")
      (node (ref "VD1") (pin "425") (pinfunction "OUT425_425") (pintype "passive"))
    )
    (net (code "428") (name "unconnected-(VD1B-OUT426-Pad426)") (class "Default")
      (node (ref "VD1") (pin "426") (pinfunction "OUT426_426") (pintype "passive"))
    )
    (net (code "429") (name "unconnected-(VD1B-OUT427-Pad427)") (class "Default")
      (node (ref "VD1") (pin "427") (pinfunction "OUT427_427") (pintype "passive"))
    )
    (net (code "430") (name "unconnected-(VD1B-OUT428-Pad428)") (class "Default")
      (node (ref "VD1") (pin "428") (pinfunction "OUT428_428") (pintype "passive"))
    )
    (net (code "431") (name "unconnected-(VD1B-OUT429-Pad429)") (class "Default")
      (node (ref "VD1") (pin "429") (pinfunction "OUT429_429") (pintype "passive"))
    )
    (net (code "432") (name "unconnected-(VD1B-OUT430-Pad430)") (class "Default")
      (node (ref "VD1") (pin "430") (pinfunction "OUT430_430") (pintype "passive"))
    )
    (net (code "433") (name "unconnected-(VD1B-OUT431-Pad431)") (class "Default")
      (node (ref "VD1") (pin "431") (pinfunction "OUT431_431") (pintype "passive"))
    )
    (net (code "434") (name "unconnected-(VD1B-OUT432-Pad432)") (class "Default")
      (node (ref "VD1") (pin "432") (pinfunction "OUT432_432") (pintype "passive"))
    )
    (net (code "435") (name "unconnected-(VD1B-OUT433-Pad433)") (class "Default")
      (node (ref "VD1") (pin "433") (pinfunction "OUT433_433") (pintype "passive"))
    )
    (net (code "436") (name "unconnected-(VD1B-OUT434-Pad434)") (class "Default")
      (node (ref "VD1") (pin "434") (pinfunction "OUT434_434") (pintype "passive"))
    )
    (net (code "437") (name "unconnected-(VD1B-OUT435-Pad435)") (class "Default")
      (node (ref "VD1") (pin "435") (pinfunction "OUT435_435") (pintype "passive"))
    )
    (net (code "438") (name "unconnected-(VD1B-OUT436-Pad436)") (class "Default")
      (node (ref "VD1") (pin "436") (pinfunction "OUT436_436") (pintype "passive"))
    )
    (net (code "439") (name "unconnected-(VD1B-OUT437-Pad437)") (class "Default")
      (node (ref "VD1") (pin "437") (pinfunction "OUT437_437") (pintype "passive"))
    )
    (net (code "440") (name "unconnected-(VD1B-OUT438-Pad438)") (class "Default")
      (node (ref "VD1") (pin "438") (pinfunction "OUT438_438") (pintype "passive"))
    )
    (net (code "441") (name "unconnected-(VD1B-OUT439-Pad439)") (class "Default")
      (node (ref "VD1") (pin "439") (pinfunction "OUT439_439") (pintype "passive"))
    )
    (net (code "442") (name "unconnected-(VD1B-OUT440-Pad440)") (class "Default")
      (node (ref "VD1") (pin "440") (pinfunction "OUT440_440") (pintype "passive"))
    )
    (net (code "443") (name "unconnected-(VD1B-OUT441-Pad441)") (class "Default")
      (node (ref "VD1") (pin "441") (pinfunction "OUT441_441") (pintype "passive"))
    )
    (net (code "444") (name "unconnected-(VD1B-OUT442-Pad442)") (class "Default")
      (node (ref "VD1") (pin "442") (pinfunction "OUT442_442") (pintype "passive"))
    )
    (net (code "445") (name "unconnected-(VD1B-OUT443-Pad443)") (class "Default")
      (node (ref "VD1") (pin "443") (pinfunction "OUT443_443") (pintype "passive"))
    )
    (net (code "446") (name "unconnected-(VD1B-OUT444-Pad444)") (class "Default")
      (node (ref "VD1") (pin "444") (pinfunction "OUT444_444") (pintype "passive"))
    )
    (net (code "447") (name "unconnected-(VD1B-OUT445-Pad445)") (class "Default")
      (node (ref "VD1") (pin "445") (pinfunction "OUT445_445") (pintype "passive"))
    )
    (net (code "448") (name "unconnected-(VD1B-OUT446-Pad446)") (class "Default")
      (node (ref "VD1") (pin "446") (pinfunction "OUT446_446") (pintype "passive"))
    )
    (net (code "449") (name "unconnected-(VD1B-OUT447-Pad447)") (class "Default")
      (node (ref "VD1") (pin "447") (pinfunction "OUT447_447") (pintype "passive"))
    )
    (net (code "450") (name "unconnected-(VD1B-OUT448-Pad448)") (class "Default")
      (node (ref "VD1") (pin "448") (pinfunction "OUT448_448") (pintype "passive"))
    )
    (net (code "451") (name "unconnected-(VD1B-OUT449-Pad449)") (class "Default")
      (node (ref "VD1") (pin "449") (pinfunction "OUT449_449") (pintype "passive"))
    )
    (net (code "452") (name "unconnected-(VD1B-OUT450-Pad450)") (class "Default")
      (node (ref "VD1") (pin "450") (pinfunction "OUT450_450") (pintype "passive"))
    )
    (net (code "453") (name "unconnected-(VD1B-OUT451-Pad451)") (class "Default")
      (node (ref "VD1") (pin "451") (pinfunction "OUT451_451") (pintype "passive"))
    )
    (net (code "454") (name "unconnected-(VD1B-OUT452-Pad452)") (class "Default")
      (node (ref "VD1") (pin "452") (pinfunction "OUT452_452") (pintype "passive"))
    )
    (net (code "455") (name "unconnected-(VD1B-OUT453-Pad453)") (class "Default")
      (node (ref "VD1") (pin "453") (pinfunction "OUT453_453") (pintype "passive"))
    )
    (net (code "456") (name "unconnected-(VD1B-OUT454-Pad454)") (class "Default")
      (node (ref "VD1") (pin "454") (pinfunction "OUT454_454") (pintype "passive"))
    )
    (net (code "457") (name "unconnected-(VD1B-OUT455-Pad455)") (class "Default")
      (node (ref "VD1") (pin "455") (pinfunction "OUT455_455") (pintype "passive"))
    )
    (net (code "458") (name "unconnected-(VD1B-OUT456-Pad456)") (class "Default")
      (node (ref "VD1") (pin "456") (pinfunction "OUT456_456") (pintype "passive"))
    )
    (net (code "459") (name "unconnected-(VD1B-OUT457-Pad457)") (class "Default")
      (node (ref "VD1") (pin "457") (pinfunction "OUT457_457") (pintype "passive"))
    )
    (net (code "460") (name "unconnected-(VD1B-OUT458-Pad458)") (class "Default")
      (node (ref "VD1") (pin "458") (pinfunction "OUT458_458") (pintype "passive"))
    )
    (net (code "461") (name "unconnected-(VD1B-OUT459-Pad459)") (class "Default")
      (node (ref "VD1") (pin "459") (pinfunction "OUT459_459") (pintype "passive"))
    )
    (net (code "462") (name "unconnected-(VD1B-OUT460-Pad460)") (class "Default")
      (node (ref "VD1") (pin "460") (pinfunction "OUT460_460") (pintype "passive"))
    )
    (net (code "463") (name "unconnected-(VD1B-OUT461-Pad461)") (class "Default")
      (node (ref "VD1") (pin "461") (pinfunction "OUT461_461") (pintype "passive"))
    )
    (net (code "464") (name "unconnected-(VD1B-OUT462-Pad462)") (class "Default")
      (node (ref "VD1") (pin "462") (pinfunction "OUT462_462") (pintype "passive"))
    )
    (net (code "465") (name "unconnected-(VD1B-OUT463-Pad463)") (class "Default")
      (node (ref "VD1") (pin "463") (pinfunction "OUT463_463") (pintype "passive"))
    )
    (net (code "466") (name "unconnected-(VD1B-OUT464-Pad464)") (class "Default")
      (node (ref "VD1") (pin "464") (pinfunction "OUT464_464") (pintype "passive"))
    )
    (net (code "467") (name "unconnected-(VD1B-OUT465-Pad465)") (class "Default")
      (node (ref "VD1") (pin "465") (pinfunction "OUT465_465") (pintype "passive"))
    )
    (net (code "468") (name "unconnected-(VD1B-OUT466-Pad466)") (class "Default")
      (node (ref "VD1") (pin "466") (pinfunction "OUT466_466") (pintype "passive"))
    )
    (net (code "469") (name "unconnected-(VD1B-OUT467-Pad467)") (class "Default")
      (node (ref "VD1") (pin "467") (pinfunction "OUT467_467") (pintype "passive"))
    )
    (net (code "470") (name "unconnected-(VD1B-OUT468-Pad468)") (class "Default")
      (node (ref "VD1") (pin "468") (pinfunction "OUT468_468") (pintype "passive"))
    )
    (net (code "471") (name "unconnected-(VD1B-OUT469-Pad469)") (class "Default")
      (node (ref "VD1") (pin "469") (pinfunction "OUT469_469") (pintype "passive"))
    )
    (net (code "472") (name "unconnected-(VD1B-OUT470-Pad470)") (class "Default")
      (node (ref "VD1") (pin "470") (pinfunction "OUT470_470") (pintype "passive"))
    )
    (net (code "473") (name "unconnected-(VD1B-OUT471-Pad471)") (class "Default")
      (node (ref "VD1") (pin "471") (pinfunction "OUT471_471") (pintype "passive"))
    )
    (net (code "474") (name "unconnected-(VD1B-OUT472-Pad472)") (class "Default")
      (node (ref "VD1") (pin "472") (pinfunction "OUT472_472") (pintype "passive"))
    )
    (net (code "475") (name "unconnected-(VD1B-OUT473-Pad473)") (class "Default")
      (node (ref "VD1") (pin "473") (pinfunction "OUT473_473") (pintype "passive"))
    )
    (net (code "476") (name "unconnected-(VD1B-OUT474-Pad474)") (class "Default")
      (node (ref "VD1") (pin "474") (pinfunction "OUT474_474") (pintype "passive"))
    )
    (net (code "477") (name "unconnected-(VD1B-OUT475-Pad475)") (class "Default")
      (node (ref "VD1") (pin "475") (pinfunction "OUT475_475") (pintype "passive"))
    )
    (net (code "478") (name "unconnected-(VD1B-OUT476-Pad476)") (class "Default")
      (node (ref "VD1") (pin "476") (pinfunction "OUT476_476") (pintype "passive"))
    )
    (net (code "479") (name "unconnected-(VD1B-OUT477-Pad477)") (class "Default")
      (node (ref "VD1") (pin "477") (pinfunction "OUT477_477") (pintype "passive"))
    )
    (net (code "480") (name "unconnected-(VD1B-OUT478-Pad478)") (class "Default")
      (node (ref "VD1") (pin "478") (pinfunction "OUT478_478") (pintype "passive"))
    )
    (net (code "481") (name "unconnected-(VD1B-OUT479-Pad479)") (class "Default")
      (node (ref "VD1") (pin "479") (pinfunction "OUT479_479") (pintype "passive"))
    )
    (net (code "482") (name "unconnected-(VD1B-OUT480-Pad480)") (class "Default")
      (node (ref "VD1") (pin "480") (pinfunction "OUT480_480") (pintype "passive"))
    )
    (net (code "483") (name "unconnected-(VD1B-OUT481-Pad481)") (class "Default")
      (node (ref "VD1") (pin "481") (pinfunction "OUT481_481") (pintype "passive"))
    )
    (net (code "484") (name "unconnected-(VD1B-OUT482-Pad482)") (class "Default")
      (node (ref "VD1") (pin "482") (pinfunction "OUT482_482") (pintype "passive"))
    )
    (net (code "485") (name "unconnected-(VD1B-OUT483-Pad483)") (class "Default")
      (node (ref "VD1") (pin "483") (pinfunction "OUT483_483") (pintype "passive"))
    )
    (net (code "486") (name "unconnected-(VD1B-OUT484-Pad484)") (class "Default")
      (node (ref "VD1") (pin "484") (pinfunction "OUT484_484") (pintype "passive"))
    )
    (net (code "487") (name "unconnected-(VD1B-OUT485-Pad485)") (class "Default")
      (node (ref "VD1") (pin "485") (pinfunction "OUT485_485") (pintype "passive"))
    )
    (net (code "488") (name "unconnected-(VD1B-OUT486-Pad486)") (class "Default")
      (node (ref "VD1") (pin "486") (pinfunction "OUT486_486") (pintype "passive"))
    )
    (net (code "489") (name "unconnected-(VD1B-OUT487-Pad487)") (class "Default")
      (node (ref "VD1") (pin "487") (pinfunction "OUT487_487") (pintype "passive"))
    )
    (net (code "490") (name "unconnected-(VD1B-OUT488-Pad488)") (class "Default")
      (node (ref "VD1") (pin "488") (pinfunction "OUT488_488") (pintype "passive"))
    )
    (net (code "491") (name "unconnected-(VD1B-OUT489-Pad489)") (class "Default")
      (node (ref "VD1") (pin "489") (pinfunction "OUT489_489") (pintype "passive"))
    )
    (net (code "492") (name "unconnected-(VD1B-OUT490-Pad490)") (class "Default")
      (node (ref "VD1") (pin "490") (pinfunction "OUT490_490") (pintype "passive"))
    )
    (net (code "493") (name "unconnected-(VD1B-OUT491-Pad491)") (class "Default")
      (node (ref "VD1") (pin "491") (pinfunction "OUT491_491") (pintype "passive"))
    )
    (net (code "494") (name "unconnected-(VD1B-OUT492-Pad492)") (class "Default")
      (node (ref "VD1") (pin "492") (pinfunction "OUT492_492") (pintype "passive"))
    )
    (net (code "495") (name "unconnected-(VD1B-OUT493-Pad493)") (class "Default")
      (node (ref "VD1") (pin "493") (pinfunction "OUT493_493") (pintype "passive"))
    )
    (net (code "496") (name "unconnected-(VD1B-OUT494-Pad494)") (class "Default")
      (node (ref "VD1") (pin "494") (pinfunction "OUT494_494") (pintype "passive"))
    )
    (net (code "497") (name "unconnected-(VD1B-OUT495-Pad495)") (class "Default")
      (node (ref "VD1") (pin "495") (pinfunction "OUT495_495") (pintype "passive"))
    )
    (net (code "498") (name "unconnected-(VD1B-OUT496-Pad496)") (class "Default")
      (node (ref "VD1") (pin "496") (pinfunction "OUT496_496") (pintype "passive"))
    )
    (net (code "499") (name "unconnected-(VD1B-OUT497-Pad497)") (class "Default")
      (node (ref "VD1") (pin "497") (pinfunction "OUT497_497") (pintype "passive"))
    )
    (net (code "500") (name "unconnected-(VD1B-OUT498-Pad498)") (class "Default")
      (node (ref "VD1") (pin "498") (pinfunction "OUT498_498") (pintype "passive"))
    )
    (net (code "501") (name "unconnected-(VD1B-OUT499-Pad499)") (class "Default")
      (node (ref "VD1") (pin "499") (pinfunction "OUT499_499") (pintype "passive"))
    )
    (net (code "502") (name "unconnected-(VD1B-OUT500-Pad500)") (class "Default")
      (node (ref "VD1") (pin "500") (pinfunction "OUT500_500") (pintype "passive"))
    )
    (net (code "503") (name "unconnected-(VD1B-OUT501-Pad501)") (class "Default")
      (node (ref "VD1") (pin "501") (pinfunction "OUT501_501") (pintype "passive"))
    )
    (net (code "504") (name "unconnected-(VD1B-OUT502-Pad502)") (class "Default")
      (node (ref "VD1") (pin "502") (pinfunction "OUT502_502") (pintype "passive"))
    )
    (net (code "505") (name "unconnected-(VD1B-OUT503-Pad503)") (class "Default")
      (node (ref "VD1") (pin "503") (pinfunction "OUT503_503") (pintype "passive"))
    )
    (net (code "506") (name "unconnected-(VD1B-OUT504-Pad504)") (class "Default")
      (node (ref "VD1") (pin "504") (pinfunction "OUT504_504") (pintype "passive"))
    )
    (net (code "507") (name "unconnected-(VD1B-OUT505-Pad505)") (class "Default")
      (node (ref "VD1") (pin "505") (pinfunction "OUT505_505") (pintype "passive"))
    )
    (net (code "508") (name "unconnected-(VD1B-OUT506-Pad506)") (class "Default")
      (node (ref "VD1") (pin "506") (pinfunction "OUT506_506") (pintype "passive"))
    )
    (net (code "509") (name "unconnected-(VD1B-OUT507-Pad507)") (class "Default")
      (node (ref "VD1") (pin "507") (pinfunction "OUT507_507") (pintype "passive"))
    )
    (net (code "510") (name "unconnected-(VD1B-OUT508-Pad508)") (class "Default")
      (node (ref "VD1") (pin "508") (pinfunction "OUT508_508") (pintype "passive"))
    )
    (net (code "511") (name "unconnected-(VD1B-OUT509-Pad509)") (class "Default")
      (node (ref "VD1") (pin "509") (pinfunction "OUT509_509") (pintype "passive"))
    )
    (net (code "512") (name "unconnected-(VD1B-OUT510-Pad510)") (class "Default")
      (node (ref "VD1") (pin "510") (pinfunction "OUT510_510") (pintype "passive"))
    )
    (net (code "513") (name "unconnected-(VD1B-OUT511-Pad511)") (class "Default")
      (node (ref "VD1") (pin "511") (pinfunction "OUT511_511") (pintype "passive"))
    )
    (net (code "514") (name "unconnected-(VD1B-OUT512-Pad512)") (class "Default")
      (node (ref "VD1") (pin "512") (pinfunction "OUT512_512") (pintype "passive"))
    )
    (net (code "515") (name "unconnected-(VD1C-OUT513-Pad513)") (class "Default")
      (node (ref "VD1") (pin "513") (pinfunction "OUT513_513") (pintype "passive"))
    )
    (net (code "516") (name "unconnected-(VD1C-OUT514-Pad514)") (class "Default")
      (node (ref "VD1") (pin "514") (pinfunction "OUT514_514") (pintype "passive"))
    )
    (net (code "517") (name "unconnected-(VD1C-OUT515-Pad515)") (class "Default")
      (node (ref "VD1") (pin "515") (pinfunction "OUT515_515") (pintype "passive"))
    )
    (net (code "518") (name "unconnected-(VD1C-OUT516-Pad516)") (class "Default")
      (node (ref "VD1") (pin "516") (pinfunction "OUT516_516") (pintype "passive"))
    )
    (net (code "519") (name "unconnected-(VD1C-OUT517-Pad517)") (class "Default")
      (node (ref "VD1") (pin "517") (pinfunction "OUT517_517") (pintype "passive"))
    )
    (net (code "520") (name "unconnected-(VD1C-OUT518-Pad518)") (class "Default")
      (node (ref "VD1") (pin "518") (pinfunction "OUT518_518") (pintype "passive"))
    )
    (net (code "521") (name "unconnected-(VD1C-OUT519-Pad519)") (class "Default")
      (node (ref "VD1") (pin "519") (pinfunction "OUT519_519") (pintype "passive"))
    )
    (net (code "522") (name "unconnected-(VD1C-OUT520-Pad520)") (class "Default")
      (node (ref "VD1") (pin "520") (pinfunction "OUT520_520") (pintype "passive"))
    )
    (net (code "523") (name "unconnected-(VD1C-OUT521-Pad521)") (class "Default")
      (node (ref "VD1") (pin "521") (pinfunction "OUT521_521") (pintype "passive"))
    )
    (net (code "524") (name "unconnected-(VD1C-OUT522-Pad522)") (class "Default")
      (node (ref "VD1") (pin "522") (pinfunction "OUT522_522") (pintype "passive"))
    )
    (net (code "525") (name "unconnected-(VD1C-OUT523-Pad523)") (class "Default")
      (node (ref "VD1") (pin "523") (pinfunction "OUT523_523") (pintype "passive"))
    )
    (net (code "526") (name "unconnected-(VD1C-OUT524-Pad524)") (class "Default")
      (node (ref "VD1") (pin "524") (pinfunction "OUT524_524") (pintype "passive"))
    )
    (net (code "527") (name "unconnected-(VD1C-OUT525-Pad525)") (class "Default")
      (node (ref "VD1") (pin "525") (pinfunction "OUT525_525") (pintype "passive"))
    )
    (net (code "528") (name "unconnected-(VD1C-OUT526-Pad526)") (class "Default")
      (node (ref "VD1") (pin "526") (pinfunction "OUT526_526") (pintype "passive"))
    )
    (net (code "529") (name "unconnected-(VD1C-OUT527-Pad527)") (class "Default")
      (node (ref "VD1") (pin "527") (pinfunction "OUT527_527") (pintype "passive"))
    )
    (net (code "530") (name "unconnected-(VD1C-OUT528-Pad528)") (class "Default")
      (node (ref "VD1") (pin "528") (pinfunction "OUT528_528") (pintype "passive"))
    )
    (net (code "531") (name "unconnected-(VD1C-OUT529-Pad529)") (class "Default")
      (node (ref "VD1") (pin "529") (pinfunction "OUT529_529") (pintype "passive"))
    )
    (net (code "532") (name "unconnected-(VD1C-OUT530-Pad530)") (class "Default")
      (node (ref "VD1") (pin "530") (pinfunction "OUT530_530") (pintype "passive"))
    )
    (net (code "533") (name "unconnected-(VD1C-OUT531-Pad531)") (class "Default")
      (node (ref "VD1") (pin "531") (pinfunction "OUT531_531") (pintype "passive"))
    )
    (net (code "534") (name "unconnected-(VD1C-OUT532-Pad532)") (class "Default")
      (node (ref "VD1") (pin "532") (pinfunction "OUT532_532") (pintype "passive"))
    )
    (net (code "535") (name "unconnected-(VD1C-OUT533-Pad533)") (class "Default")
      (node (ref "VD1") (pin "533") (pinfunction "OUT533_533") (pintype "passive"))
    )
    (net (code "536") (name "unconnected-(VD1C-OUT534-Pad534)") (class "Default")
      (node (ref "VD1") (pin "534") (pinfunction "OUT534_534") (pintype "passive"))
    )
    (net (code "537") (name "unconnected-(VD1C-OUT535-Pad535)") (class "Default")
      (node (ref "VD1") (pin "535") (pinfunction "OUT535_535") (pintype "passive"))
    )
    (net (code "538") (name "unconnected-(VD1C-OUT536-Pad536)") (class "Default")
      (node (ref "VD1") (pin "536") (pinfunction "OUT536_536") (pintype "passive"))
    )
    (net (code "539") (name "unconnected-(VD1C-OUT537-Pad537)") (class "Default")
      (node (ref "VD1") (pin "537") (pinfunction "OUT537_537") (pintype "passive"))
    )
    (net (code "540") (name "unconnected-(VD1C-OUT538-Pad538)") (class "Default")
      (node (ref "VD1") (pin "538") (pinfunction "OUT538_538") (pintype "passive"))
    )
    (net (code "541") (name "unconnected-(VD1C-OUT539-Pad539)") (class "Default")
      (node (ref "VD1") (pin "539") (pinfunction "OUT539_539") (pintype "passive"))
    )
    (net (code "542") (name "unconnected-(VD1C-OUT540-Pad540)") (class "Default")
      (node (ref "VD1") (pin "540") (pinfunction "OUT540_540") (pintype "passive"))
    )
    (net (code "543") (name "unconnected-(VD1C-OUT541-Pad541)") (class "Default")
      (node (ref "VD1") (pin "541") (pinfunction "OUT541_541") (pintype "passive"))
    )
    (net (code "544") (name "unconnected-(VD1C-OUT542-Pad542)") (class "Default")
      (node (ref "VD1") (pin "542") (pinfunction "OUT542_542") (pintype "passive"))
    )
    (net (code "545") (name "unconnected-(VD1C-OUT543-Pad543)") (class "Default")
      (node (ref "VD1") (pin "543") (pinfunction "OUT543_543") (pintype "passive"))
    )
    (net (code "546") (name "unconnected-(VD1C-OUT544-Pad544)") (class "Default")
      (node (ref "VD1") (pin "544") (pinfunction "OUT544_544") (pintype "passive"))
    )
    (net (code "547") (name "unconnected-(VD1C-OUT545-Pad545)") (class "Default")
      (node (ref "VD1") (pin "545") (pinfunction "OUT545_545") (pintype "passive"))
    )
    (net (code "548") (name "unconnected-(VD1C-OUT546-Pad546)") (class "Default")
      (node (ref "VD1") (pin "546") (pinfunction "OUT546_546") (pintype "passive"))
    )
    (net (code "549") (name "unconnected-(VD1C-OUT547-Pad547)") (class "Default")
      (node (ref "VD1") (pin "547") (pinfunction "OUT547_547") (pintype "passive"))
    )
    (net (code "550") (name "unconnected-(VD1C-OUT548-Pad548)") (class "Default")
      (node (ref "VD1") (pin "548") (pinfunction "OUT548_548") (pintype "passive"))
    )
    (net (code "551") (name "unconnected-(VD1C-OUT549-Pad549)") (class "Default")
      (node (ref "VD1") (pin "549") (pinfunction "OUT549_549") (pintype "passive"))
    )
    (net (code "552") (name "unconnected-(VD1C-OUT550-Pad550)") (class "Default")
      (node (ref "VD1") (pin "550") (pinfunction "OUT550_550") (pintype "passive"))
    )
    (net (code "553") (name "unconnected-(VD1C-OUT551-Pad551)") (class "Default")
      (node (ref "VD1") (pin "551") (pinfunction "OUT551_551") (pintype "passive"))
    )
    (net (code "554") (name "unconnected-(VD1C-OUT552-Pad552)") (class "Default")
      (node (ref "VD1") (pin "552") (pinfunction "OUT552_552") (pintype "passive"))
    )
    (net (code "555") (name "unconnected-(VD1C-OUT553-Pad553)") (class "Default")
      (node (ref "VD1") (pin "553") (pinfunction "OUT553_553") (pintype "passive"))
    )
    (net (code "556") (name "unconnected-(VD1C-OUT554-Pad554)") (class "Default")
      (node (ref "VD1") (pin "554") (pinfunction "OUT554_554") (pintype "passive"))
    )
    (net (code "557") (name "unconnected-(VD1C-OUT555-Pad555)") (class "Default")
      (node (ref "VD1") (pin "555") (pinfunction "OUT555_555") (pintype "passive"))
    )
    (net (code "558") (name "unconnected-(VD1C-OUT556-Pad556)") (class "Default")
      (node (ref "VD1") (pin "556") (pinfunction "OUT556_556") (pintype "passive"))
    )
    (net (code "559") (name "unconnected-(VD1C-OUT557-Pad557)") (class "Default")
      (node (ref "VD1") (pin "557") (pinfunction "OUT557_557") (pintype "passive"))
    )
    (net (code "560") (name "unconnected-(VD1C-OUT558-Pad558)") (class "Default")
      (node (ref "VD1") (pin "558") (pinfunction "OUT558_558") (pintype "passive"))
    )
    (net (code "561") (name "unconnected-(VD1C-OUT559-Pad559)") (class "Default")
      (node (ref "VD1") (pin "559") (pinfunction "OUT559_559") (pintype "passive"))
    )
    (net (code "562") (name "unconnected-(VD1C-OUT560-Pad560)") (class "Default")
      (node (ref "VD1") (pin "560") (pinfunction "OUT560_560") (pintype "passive"))
    )
    (net (code "563") (name "unconnected-(VD1C-OUT561-Pad561)") (class "Default")
      (node (ref "VD1") (pin "561") (pinfunction "OUT561_561") (pintype "passive"))
    )
    (net (code "564") (name "unconnected-(VD1C-OUT562-Pad562)") (class "Default")
      (node (ref "VD1") (pin "562") (pinfunction "OUT562_562") (pintype "passive"))
    )
    (net (code "565") (name "unconnected-(VD1C-OUT563-Pad563)") (class "Default")
      (node (ref "VD1") (pin "563") (pinfunction "OUT563_563") (pintype "passive"))
    )
    (net (code "566") (name "unconnected-(VD1C-OUT564-Pad564)") (class "Default")
      (node (ref "VD1") (pin "564") (pinfunction "OUT564_564") (pintype "passive"))
    )
    (net (code "567") (name "unconnected-(VD1C-OUT565-Pad565)") (class "Default")
      (node (ref "VD1") (pin "565") (pinfunction "OUT565_565") (pintype "passive"))
    )
    (net (code "568") (name "unconnected-(VD1C-OUT566-Pad566)") (class "Default")
      (node (ref "VD1") (pin "566") (pinfunction "OUT566_566") (pintype "passive"))
    )
    (net (code "569") (name "unconnected-(VD1C-OUT567-Pad567)") (class "Default")
      (node (ref "VD1") (pin "567") (pinfunction "OUT567_567") (pintype "passive"))
    )
    (net (code "570") (name "unconnected-(VD1C-OUT568-Pad568)") (class "Default")
      (node (ref "VD1") (pin "568") (pinfunction "OUT568_568") (pintype "passive"))
    )
    (net (code "571") (name "unconnected-(VD1C-OUT569-Pad569)") (class "Default")
      (node (ref "VD1") (pin "569") (pinfunction "OUT569_569") (pintype "passive"))
    )
    (net (code "572") (name "unconnected-(VD1C-OUT570-Pad570)") (class "Default")
      (node (ref "VD1") (pin "570") (pinfunction "OUT570_570") (pintype "passive"))
    )
    (net (code "573") (name "unconnected-(VD1C-OUT571-Pad571)") (class "Default")
      (node (ref "VD1") (pin "571") (pinfunction "OUT571_571") (pintype "passive"))
    )
    (net (code "574") (name "unconnected-(VD1C-OUT572-Pad572)") (class "Default")
      (node (ref "VD1") (pin "572") (pinfunction "OUT572_572") (pintype "passive"))
    )
    (net (code "575") (name "unconnected-(VD1C-OUT573-Pad573)") (class "Default")
      (node (ref "VD1") (pin "573") (pinfunction "OUT573_573") (pintype "passive"))
    )
    (net (code "576") (name "unconnected-(VD1C-OUT574-Pad574)") (class "Default")
      (node (ref "VD1") (pin "574") (pinfunction "OUT574_574") (pintype "passive"))
    )
    (net (code "577") (name "unconnected-(VD1C-OUT575-Pad575)") (class "Default")
      (node (ref "VD1") (pin "575") (pinfunction "OUT575_575") (pintype "passive"))
    )
    (net (code "578") (name "unconnected-(VD1C-OUT576-Pad576)") (class "Default")
      (node (ref "VD1") (pin "576") (pinfunction "OUT576_576") (pintype "passive"))
    )
    (net (code "579") (name "unconnected-(VD1C-OUT577-Pad577)") (class "Default")
      (node (ref "VD1") (pin "577") (pinfunction "OUT577_577") (pintype "passive"))
    )
    (net (code "580") (name "unconnected-(VD1C-OUT578-Pad578)") (class "Default")
      (node (ref "VD1") (pin "578") (pinfunction "OUT578_578") (pintype "passive"))
    )
    (net (code "581") (name "unconnected-(VD1C-OUT579-Pad579)") (class "Default")
      (node (ref "VD1") (pin "579") (pinfunction "OUT579_579") (pintype "passive"))
    )
    (net (code "582") (name "unconnected-(VD1C-OUT580-Pad580)") (class "Default")
      (node (ref "VD1") (pin "580") (pinfunction "OUT580_580") (pintype "passive"))
    )
    (net (code "583") (name "unconnected-(VD1C-OUT581-Pad581)") (class "Default")
      (node (ref "VD1") (pin "581") (pinfunction "OUT581_581") (pintype "passive"))
    )
    (net (code "584") (name "unconnected-(VD1C-OUT582-Pad582)") (class "Default")
      (node (ref "VD1") (pin "582") (pinfunction "OUT582_582") (pintype "passive"))
    )
    (net (code "585") (name "unconnected-(VD1C-OUT583-Pad583)") (class "Default")
      (node (ref "VD1") (pin "583") (pinfunction "OUT583_583") (pintype "passive"))
    )
    (net (code "586") (name "unconnected-(VD1C-OUT584-Pad584)") (class "Default")
      (node (ref "VD1") (pin "584") (pinfunction "OUT584_584") (pintype "passive"))
    )
    (net (code "587") (name "unconnected-(VD1C-OUT585-Pad585)") (class "Default")
      (node (ref "VD1") (pin "585") (pinfunction "OUT585_585") (pintype "passive"))
    )
    (net (code "588") (name "unconnected-(VD1C-OUT586-Pad586)") (class "Default")
      (node (ref "VD1") (pin "586") (pinfunction "OUT586_586") (pintype "passive"))
    )
    (net (code "589") (name "unconnected-(VD1C-OUT587-Pad587)") (class "Default")
      (node (ref "VD1") (pin "587") (pinfunction "OUT587_587") (pintype "passive"))
    )
    (net (code "590") (name "unconnected-(VD1C-OUT588-Pad588)") (class "Default")
      (node (ref "VD1") (pin "588") (pinfunction "OUT588_588") (pintype "passive"))
    )
    (net (code "591") (name "unconnected-(VD1C-OUT589-Pad589)") (class "Default")
      (node (ref "VD1") (pin "589") (pinfunction "OUT589_589") (pintype "passive"))
    )
    (net (code "592") (name "unconnected-(VD1C-OUT590-Pad590)") (class "Default")
      (node (ref "VD1") (pin "590") (pinfunction "OUT590_590") (pintype "passive"))
    )
    (net (code "593") (name "unconnected-(VD1C-OUT591-Pad591)") (class "Default")
      (node (ref "VD1") (pin "591") (pinfunction "OUT591_591") (pintype "passive"))
    )
    (net (code "594") (name "unconnected-(VD1C-OUT592-Pad592)") (class "Default")
      (node (ref "VD1") (pin "592") (pinfunction "OUT592_592") (pintype "passive"))
    )
    (net (code "595") (name "unconnected-(VD1C-OUT593-Pad593)") (class "Default")
      (node (ref "VD1") (pin "593") (pinfunction "OUT593_593") (pintype "passive"))
    )
    (net (code "596") (name "unconnected-(VD1C-OUT594-Pad594)") (class "Default")
      (node (ref "VD1") (pin "594") (pinfunction "OUT594_594") (pintype "passive"))
    )
    (net (code "597") (name "unconnected-(VD1C-OUT595-Pad595)") (class "Default")
      (node (ref "VD1") (pin "595") (pinfunction "OUT595_595") (pintype "passive"))
    )
    (net (code "598") (name "unconnected-(VD1C-OUT596-Pad596)") (class "Default")
      (node (ref "VD1") (pin "596") (pinfunction "OUT596_596") (pintype "passive"))
    )
    (net (code "599") (name "unconnected-(VD1C-OUT597-Pad597)") (class "Default")
      (node (ref "VD1") (pin "597") (pinfunction "OUT597_597") (pintype "passive"))
    )
    (net (code "600") (name "unconnected-(VD1C-OUT598-Pad598)") (class "Default")
      (node (ref "VD1") (pin "598") (pinfunction "OUT598_598") (pintype "passive"))
    )
    (net (code "601") (name "unconnected-(VD1C-OUT599-Pad599)") (class "Default")
      (node (ref "VD1") (pin "599") (pinfunction "OUT599_599") (pintype "passive"))
    )
    (net (code "602") (name "unconnected-(VD1C-OUT600-Pad600)") (class "Default")
      (node (ref "VD1") (pin "600") (pinfunction "OUT600_600") (pintype "passive"))
    )
    (net (code "603") (name "unconnected-(VD1C-OUT601-Pad601)") (class "Default")
      (node (ref "VD1") (pin "601") (pinfunction "OUT601_601") (pintype "passive"))
    )
    (net (code "604") (name "unconnected-(VD1C-OUT602-Pad602)") (class "Default")
      (node (ref "VD1") (pin "602") (pinfunction "OUT602_602") (pintype "passive"))
    )
    (net (code "605") (name "unconnected-(VD1C-OUT603-Pad603)") (class "Default")
      (node (ref "VD1") (pin "603") (pinfunction "OUT603_603") (pintype "passive"))
    )
    (net (code "606") (name "unconnected-(VD1C-OUT604-Pad604)") (class "Default")
      (node (ref "VD1") (pin "604") (pinfunction "OUT604_604") (pintype "passive"))
    )
    (net (code "607") (name "unconnected-(VD1C-OUT605-Pad605)") (class "Default")
      (node (ref "VD1") (pin "605") (pinfunction "OUT605_605") (pintype "passive"))
    )
    (net (code "608") (name "unconnected-(VD1C-OUT606-Pad606)") (class "Default")
      (node (ref "VD1") (pin "606") (pinfunction "OUT606_606") (pintype "passive"))
    )
    (net (code "609") (name "unconnected-(VD1C-OUT607-Pad607)") (class "Default")
      (node (ref "VD1") (pin "607") (pinfunction "OUT607_607") (pintype "passive"))
    )
    (net (code "610") (name "unconnected-(VD1C-OUT608-Pad608)") (class "Default")
      (node (ref "VD1") (pin "608") (pinfunction "OUT608_608") (pintype "passive"))
    )
    (net (code "611") (name "unconnected-(VD1C-OUT609-Pad609)") (class "Default")
      (node (ref "VD1") (pin "609") (pinfunction "OUT609_609") (pintype "passive"))
    )
    (net (code "612") (name "unconnected-(VD1C-OUT610-Pad610)") (class "Default")
      (node (ref "VD1") (pin "610") (pinfunction "OUT610_610") (pintype "passive"))
    )
    (net (code "613") (name "unconnected-(VD1C-OUT611-Pad611)") (class "Default")
      (node (ref "VD1") (pin "611") (pinfunction "OUT611_611") (pintype "passive"))
    )
    (net (code "614") (name "unconnected-(VD1C-OUT612-Pad612)") (class "Default")
      (node (ref "VD1") (pin "612") (pinfunction "OUT612_612") (pintype "passive"))
    )
    (net (code "615") (name "unconnected-(VD1C-OUT613-Pad613)") (class "Default")
      (node (ref "VD1") (pin "613") (pinfunction "OUT613_613") (pintype "passive"))
    )
    (net (code "616") (name "unconnected-(VD1C-OUT614-Pad614)") (class "Default")
      (node (ref "VD1") (pin "614") (pinfunction "OUT614_614") (pintype "passive"))
    )
    (net (code "617") (name "unconnected-(VD1C-OUT615-Pad615)") (class "Default")
      (node (ref "VD1") (pin "615") (pinfunction "OUT615_615") (pintype "passive"))
    )
    (net (code "618") (name "unconnected-(VD1C-OUT616-Pad616)") (class "Default")
      (node (ref "VD1") (pin "616") (pinfunction "OUT616_616") (pintype "passive"))
    )
    (net (code "619") (name "unconnected-(VD1C-OUT617-Pad617)") (class "Default")
      (node (ref "VD1") (pin "617") (pinfunction "OUT617_617") (pintype "passive"))
    )
    (net (code "620") (name "unconnected-(VD1C-OUT618-Pad618)") (class "Default")
      (node (ref "VD1") (pin "618") (pinfunction "OUT618_618") (pintype "passive"))
    )
    (net (code "621") (name "unconnected-(VD1C-OUT619-Pad619)") (class "Default")
      (node (ref "VD1") (pin "619") (pinfunction "OUT619_619") (pintype "passive"))
    )
    (net (code "622") (name "unconnected-(VD1C-OUT620-Pad620)") (class "Default")
      (node (ref "VD1") (pin "620") (pinfunction "OUT620_620") (pintype "passive"))
    )
    (net (code "623") (name "unconnected-(VD1C-OUT621-Pad621)") (class "Default")
      (node (ref "VD1") (pin "621") (pinfunction "OUT621_621") (pintype "passive"))
    )
    (net (code "624") (name "unconnected-(VD1C-OUT622-Pad622)") (class "Default")
      (node (ref "VD1") (pin "622") (pinfunction "OUT622_622") (pintype "passive"))
    )
    (net (code "625") (name "unconnected-(VD1C-OUT623-Pad623)") (class "Default")
      (node (ref "VD1") (pin "623") (pinfunction "OUT623_623") (pintype "passive"))
    )
    (net (code "626") (name "unconnected-(VD1C-OUT624-Pad624)") (class "Default")
      (node (ref "VD1") (pin "624") (pinfunction "OUT624_624") (pintype "passive"))
    )
    (net (code "627") (name "unconnected-(VD1C-OUT625-Pad625)") (class "Default")
      (node (ref "VD1") (pin "625") (pinfunction "OUT625_625") (pintype "passive"))
    )
    (net (code "628") (name "unconnected-(VD1C-OUT626-Pad626)") (class "Default")
      (node (ref "VD1") (pin "626") (pinfunction "OUT626_626") (pintype "passive"))
    )
    (net (code "629") (name "unconnected-(VD1C-OUT627-Pad627)") (class "Default")
      (node (ref "VD1") (pin "627") (pinfunction "OUT627_627") (pintype "passive"))
    )
    (net (code "630") (name "unconnected-(VD1C-OUT628-Pad628)") (class "Default")
      (node (ref "VD1") (pin "628") (pinfunction "OUT628_628") (pintype "passive"))
    )
    (net (code "631") (name "unconnected-(VD1C-OUT629-Pad629)") (class "Default")
      (node (ref "VD1") (pin "629") (pinfunction "OUT629_629") (pintype "passive"))
    )
    (net (code "632") (name "unconnected-(VD1C-OUT630-Pad630)") (class "Default")
      (node (ref "VD1") (pin "630") (pinfunction "OUT630_630") (pintype "passive"))
    )
    (net (code "633") (name "unconnected-(VD1C-OUT631-Pad631)") (class "Default")
      (node (ref "VD1") (pin "631") (pinfunction "OUT631_631") (pintype "passive"))
    )
    (net (code "634") (name "unconnected-(VD1C-OUT632-Pad632)") (class "Default")
      (node (ref "VD1") (pin "632") (pinfunction "OUT632_632") (pintype "passive"))
    )
    (net (code "635") (name "unconnected-(VD1C-OUT633-Pad633)") (class "Default")
      (node (ref "VD1") (pin "633") (pinfunction "OUT633_633") (pintype "passive"))
    )
    (net (code "636") (name "unconnected-(VD1C-OUT634-Pad634)") (class "Default")
      (node (ref "VD1") (pin "634") (pinfunction "OUT634_634") (pintype "passive"))
    )
    (net (code "637") (name "unconnected-(VD1C-OUT635-Pad635)") (class "Default")
      (node (ref "VD1") (pin "635") (pinfunction "OUT635_635") (pintype "passive"))
    )
    (net (code "638") (name "unconnected-(VD1C-OUT636-Pad636)") (class "Default")
      (node (ref "VD1") (pin "636") (pinfunction "OUT636_636") (pintype "passive"))
    )
    (net (code "639") (name "unconnected-(VD1C-OUT637-Pad637)") (class "Default")
      (node (ref "VD1") (pin "637") (pinfunction "OUT637_637") (pintype "passive"))
    )
    (net (code "640") (name "unconnected-(VD1C-OUT638-Pad638)") (class "Default")
      (node (ref "VD1") (pin "638") (pinfunction "OUT638_638") (pintype "passive"))
    )
    (net (code "641") (name "unconnected-(VD1C-OUT639-Pad639)") (class "Default")
      (node (ref "VD1") (pin "639") (pinfunction "OUT639_639") (pintype "passive"))
    )
    (net (code "642") (name "unconnected-(VD1C-OUT640-Pad640)") (class "Default")
      (node (ref "VD1") (pin "640") (pinfunction "OUT640_640") (pintype "passive"))
    )
    (net (code "643") (name "unconnected-(VD1C-OUT641-Pad641)") (class "Default")
      (node (ref "VD1") (pin "641") (pinfunction "OUT641_641") (pintype "passive"))
    )
    (net (code "644") (name "unconnected-(VD1C-OUT642-Pad642)") (class "Default")
      (node (ref "VD1") (pin "642") (pinfunction "OUT642_642") (pintype "passive"))
    )
    (net (code "645") (name "unconnected-(VD1C-OUT643-Pad643)") (class "Default")
      (node (ref "VD1") (pin "643") (pinfunction "OUT643_643") (pintype "passive"))
    )
    (net (code "646") (name "unconnected-(VD1C-OUT644-Pad644)") (class "Default")
      (node (ref "VD1") (pin "644") (pinfunction "OUT644_644") (pintype "passive"))
    )
    (net (code "647") (name "unconnected-(VD1C-OUT645-Pad645)") (class "Default")
      (node (ref "VD1") (pin "645") (pinfunction "OUT645_645") (pintype "passive"))
    )
    (net (code "648") (name "unconnected-(VD1C-OUT646-Pad646)") (class "Default")
      (node (ref "VD1") (pin "646") (pinfunction "OUT646_646") (pintype "passive"))
    )
    (net (code "649") (name "unconnected-(VD1C-OUT647-Pad647)") (class "Default")
      (node (ref "VD1") (pin "647") (pinfunction "OUT647_647") (pintype "passive"))
    )
    (net (code "650") (name "unconnected-(VD1C-OUT648-Pad648)") (class "Default")
      (node (ref "VD1") (pin "648") (pinfunction "OUT648_648") (pintype "passive"))
    )
    (net (code "651") (name "unconnected-(VD1C-OUT649-Pad649)") (class "Default")
      (node (ref "VD1") (pin "649") (pinfunction "OUT649_649") (pintype "passive"))
    )
    (net (code "652") (name "unconnected-(VD1C-OUT650-Pad650)") (class "Default")
      (node (ref "VD1") (pin "650") (pinfunction "OUT650_650") (pintype "passive"))
    )
    (net (code "653") (name "unconnected-(VD1C-OUT651-Pad651)") (class "Default")
      (node (ref "VD1") (pin "651") (pinfunction "OUT651_651") (pintype "passive"))
    )
    (net (code "654") (name "unconnected-(VD1C-OUT652-Pad652)") (class "Default")
      (node (ref "VD1") (pin "652") (pinfunction "OUT652_652") (pintype "passive"))
    )
    (net (code "655") (name "unconnected-(VD1C-OUT653-Pad653)") (class "Default")
      (node (ref "VD1") (pin "653") (pinfunction "OUT653_653") (pintype "passive"))
    )
    (net (code "656") (name "unconnected-(VD1C-OUT654-Pad654)") (class "Default")
      (node (ref "VD1") (pin "654") (pinfunction "OUT654_654") (pintype "passive"))
    )
    (net (code "657") (name "unconnected-(VD1C-OUT655-Pad655)") (class "Default")
      (node (ref "VD1") (pin "655") (pinfunction "OUT655_655") (pintype "passive"))
    )
    (net (code "658") (name "unconnected-(VD1C-OUT656-Pad656)") (class "Default")
      (node (ref "VD1") (pin "656") (pinfunction "OUT656_656") (pintype "passive"))
    )
    (net (code "659") (name "unconnected-(VD1C-OUT657-Pad657)") (class "Default")
      (node (ref "VD1") (pin "657") (pinfunction "OUT657_657") (pintype "passive"))
    )
    (net (code "660") (name "unconnected-(VD1C-OUT658-Pad658)") (class "Default")
      (node (ref "VD1") (pin "658") (pinfunction "OUT658_658") (pintype "passive"))
    )
    (net (code "661") (name "unconnected-(VD1C-OUT659-Pad659)") (class "Default")
      (node (ref "VD1") (pin "659") (pinfunction "OUT659_659") (pintype "passive"))
    )
    (net (code "662") (name "unconnected-(VD1C-OUT660-Pad660)") (class "Default")
      (node (ref "VD1") (pin "660") (pinfunction "OUT660_660") (pintype "passive"))
    )
    (net (code "663") (name "unconnected-(VD1C-OUT661-Pad661)") (class "Default")
      (node (ref "VD1") (pin "661") (pinfunction "OUT661_661") (pintype "passive"))
    )
    (net (code "664") (name "unconnected-(VD1C-OUT662-Pad662)") (class "Default")
      (node (ref "VD1") (pin "662") (pinfunction "OUT662_662") (pintype "passive"))
    )
    (net (code "665") (name "unconnected-(VD1C-OUT663-Pad663)") (class "Default")
      (node (ref "VD1") (pin "663") (pinfunction "OUT663_663") (pintype "passive"))
    )
    (net (code "666") (name "unconnected-(VD1C-OUT664-Pad664)") (class "Default")
      (node (ref "VD1") (pin "664") (pinfunction "OUT664_664") (pintype "passive"))
    )
    (net (code "667") (name "unconnected-(VD1C-OUT665-Pad665)") (class "Default")
      (node (ref "VD1") (pin "665") (pinfunction "OUT665_665") (pintype "passive"))
    )
    (net (code "668") (name "unconnected-(VD1C-OUT666-Pad666)") (class "Default")
      (node (ref "VD1") (pin "666") (pinfunction "OUT666_666") (pintype "passive"))
    )
    (net (code "669") (name "unconnected-(VD1C-OUT667-Pad667)") (class "Default")
      (node (ref "VD1") (pin "667") (pinfunction "OUT667_667") (pintype "passive"))
    )
    (net (code "670") (name "unconnected-(VD1C-OUT668-Pad668)") (class "Default")
      (node (ref "VD1") (pin "668") (pinfunction "OUT668_668") (pintype "passive"))
    )
    (net (code "671") (name "unconnected-(VD1C-OUT669-Pad669)") (class "Default")
      (node (ref "VD1") (pin "669") (pinfunction "OUT669_669") (pintype "passive"))
    )
    (net (code "672") (name "unconnected-(VD1C-OUT670-Pad670)") (class "Default")
      (node (ref "VD1") (pin "670") (pinfunction "OUT670_670") (pintype "passive"))
    )
    (net (code "673") (name "unconnected-(VD1C-OUT671-Pad671)") (class "Default")
      (node (ref "VD1") (pin "671") (pinfunction "OUT671_671") (pintype "passive"))
    )
    (net (code "674") (name "unconnected-(VD1C-OUT672-Pad672)") (class "Default")
      (node (ref "VD1") (pin "672") (pinfunction "OUT672_672") (pintype "passive"))
    )
    (net (code "675") (name "unconnected-(VD1C-OUT673-Pad673)") (class "Default")
      (node (ref "VD1") (pin "673") (pinfunction "OUT673_673") (pintype "passive"))
    )
    (net (code "676") (name "unconnected-(VD1C-OUT674-Pad674)") (class "Default")
      (node (ref "VD1") (pin "674") (pinfunction "OUT674_674") (pintype "passive"))
    )
    (net (code "677") (name "unconnected-(VD1C-OUT675-Pad675)") (class "Default")
      (node (ref "VD1") (pin "675") (pinfunction "OUT675_675") (pintype "passive"))
    )
    (net (code "678") (name "unconnected-(VD1C-OUT676-Pad676)") (class "Default")
      (node (ref "VD1") (pin "676") (pinfunction "OUT676_676") (pintype "passive"))
    )
    (net (code "679") (name "unconnected-(VD1C-OUT677-Pad677)") (class "Default")
      (node (ref "VD1") (pin "677") (pinfunction "OUT677_677") (pintype "passive"))
    )
    (net (code "680") (name "unconnected-(VD1C-OUT678-Pad678)") (class "Default")
      (node (ref "VD1") (pin "678") (pinfunction "OUT678_678") (pintype "passive"))
    )
    (net (code "681") (name "unconnected-(VD1C-OUT679-Pad679)") (class "Default")
      (node (ref "VD1") (pin "679") (pinfunction "OUT679_679") (pintype "passive"))
    )
    (net (code "682") (name "unconnected-(VD1C-OUT680-Pad680)") (class "Default")
      (node (ref "VD1") (pin "680") (pinfunction "OUT680_680") (pintype "passive"))
    )
    (net (code "683") (name "unconnected-(VD1C-OUT681-Pad681)") (class "Default")
      (node (ref "VD1") (pin "681") (pinfunction "OUT681_681") (pintype "passive"))
    )
    (net (code "684") (name "unconnected-(VD1C-OUT682-Pad682)") (class "Default")
      (node (ref "VD1") (pin "682") (pinfunction "OUT682_682") (pintype "passive"))
    )
    (net (code "685") (name "unconnected-(VD1C-OUT683-Pad683)") (class "Default")
      (node (ref "VD1") (pin "683") (pinfunction "OUT683_683") (pintype "passive"))
    )
    (net (code "686") (name "unconnected-(VD1C-OUT684-Pad684)") (class "Default")
      (node (ref "VD1") (pin "684") (pinfunction "OUT684_684") (pintype "passive"))
    )
    (net (code "687") (name "unconnected-(VD1C-OUT685-Pad685)") (class "Default")
      (node (ref "VD1") (pin "685") (pinfunction "OUT685_685") (pintype "passive"))
    )
    (net (code "688") (name "unconnected-(VD1C-OUT686-Pad686)") (class "Default")
      (node (ref "VD1") (pin "686") (pinfunction "OUT686_686") (pintype "passive"))
    )
    (net (code "689") (name "unconnected-(VD1C-OUT687-Pad687)") (class "Default")
      (node (ref "VD1") (pin "687") (pinfunction "OUT687_687") (pintype "passive"))
    )
    (net (code "690") (name "unconnected-(VD1C-OUT688-Pad688)") (class "Default")
      (node (ref "VD1") (pin "688") (pinfunction "OUT688_688") (pintype "passive"))
    )
    (net (code "691") (name "unconnected-(VD1C-OUT689-Pad689)") (class "Default")
      (node (ref "VD1") (pin "689") (pinfunction "OUT689_689") (pintype "passive"))
    )
    (net (code "692") (name "unconnected-(VD1C-OUT690-Pad690)") (class "Default")
      (node (ref "VD1") (pin "690") (pinfunction "OUT690_690") (pintype "passive"))
    )
    (net (code "693") (name "unconnected-(VD1C-OUT691-Pad691)") (class "Default")
      (node (ref "VD1") (pin "691") (pinfunction "OUT691_691") (pintype "passive"))
    )
    (net (code "694") (name "unconnected-(VD1C-OUT692-Pad692)") (class "Default")
      (node (ref "VD1") (pin "692") (pinfunction "OUT692_692") (pintype "passive"))
    )
    (net (code "695") (name "unconnected-(VD1C-OUT693-Pad693)") (class "Default")
      (node (ref "VD1") (pin "693") (pinfunction "OUT693_693") (pintype "passive"))
    )
    (net (code "696") (name "unconnected-(VD1C-OUT694-Pad694)") (class "Default")
      (node (ref "VD1") (pin "694") (pinfunction "OUT694_694") (pintype "passive"))
    )
    (net (code "697") (name "unconnected-(VD1C-OUT695-Pad695)") (class "Default")
      (node (ref "VD1") (pin "695") (pinfunction "OUT695_695") (pintype "passive"))
    )
    (net (code "698") (name "unconnected-(VD1C-OUT696-Pad696)") (class "Default")
      (node (ref "VD1") (pin "696") (pinfunction "OUT696_696") (pintype "passive"))
    )
    (net (code "699") (name "unconnected-(VD1C-OUT697-Pad697)") (class "Default")
      (node (ref "VD1") (pin "697") (pinfunction "OUT697_697") (pintype "passive"))
    )
    (net (code "700") (name "unconnected-(VD1C-OUT698-Pad698)") (class "Default")
      (node (ref "VD1") (pin "698") (pinfunction "OUT698_698") (pintype "passive"))
    )
    (net (code "701") (name "unconnected-(VD1C-OUT699-Pad699)") (class "Default")
      (node (ref "VD1") (pin "699") (pinfunction "OUT699_699") (pintype "passive"))
    )
    (net (code "702") (name "unconnected-(VD1C-OUT700-Pad700)") (class "Default")
      (node (ref "VD1") (pin "700") (pinfunction "OUT700_700") (pintype "passive"))
    )
    (net (code "703") (name "unconnected-(VD1C-OUT701-Pad701)") (class "Default")
      (node (ref "VD1") (pin "701") (pinfunction "OUT701_701") (pintype "passive"))
    )
    (net (code "704") (name "unconnected-(VD1C-OUT702-Pad702)") (class "Default")
      (node (ref "VD1") (pin "702") (pinfunction "OUT702_702") (pintype "passive"))
    )
    (net (code "705") (name "unconnected-(VD1C-OUT703-Pad703)") (class "Default")
      (node (ref "VD1") (pin "703") (pinfunction "OUT703_703") (pintype "passive"))
    )
    (net (code "706") (name "unconnected-(VD1C-OUT704-Pad704)") (class "Default")
      (node (ref "VD1") (pin "704") (pinfunction "OUT704_704") (pintype "passive"))
    )
    (net (code "707") (name "unconnected-(VD1C-OUT705-Pad705)") (class "Default")
      (node (ref "VD1") (pin "705") (pinfunction "OUT705_705") (pintype "passive"))
    )
    (net (code "708") (name "unconnected-(VD1C-OUT706-Pad706)") (class "Default")
      (node (ref "VD1") (pin "706") (pinfunction "OUT706_706") (pintype "passive"))
    )
    (net (code "709") (name "unconnected-(VD1C-OUT707-Pad707)") (class "Default")
      (node (ref "VD1") (pin "707") (pinfunction "OUT707_707") (pintype "passive"))
    )
    (net (code "710") (name "unconnected-(VD1C-OUT708-Pad708)") (class "Default")
      (node (ref "VD1") (pin "708") (pinfunction "OUT708_708") (pintype "passive"))
    )
    (net (code "711") (name "unconnected-(VD1C-OUT709-Pad709)") (class "Default")
      (node (ref "VD1") (pin "709") (pinfunction "OUT709_709") (pintype "passive"))
    )
    (net (code "712") (name "unconnected-(VD1C-OUT710-Pad710)") (class "Default")
      (node (ref "VD1") (pin "710") (pinfunction "OUT710_710") (pintype "passive"))
    )
    (net (code "713") (name "unconnected-(VD1C-OUT711-Pad711)") (class "Default")
      (node (ref "VD1") (pin "711") (pinfunction "OUT711_711") (pintype "passive"))
    )
    (net (code "714") (name "unconnected-(VD1C-OUT712-Pad712)") (class "Default")
      (node (ref "VD1") (pin "712") (pinfunction "OUT712_712") (pintype "passive"))
    )
    (net (code "715") (name "unconnected-(VD1C-OUT713-Pad713)") (class "Default")
      (node (ref "VD1") (pin "713") (pinfunction "OUT713_713") (pintype "passive"))
    )
    (net (code "716") (name "unconnected-(VD1C-OUT714-Pad714)") (class "Default")
      (node (ref "VD1") (pin "714") (pinfunction "OUT714_714") (pintype "passive"))
    )
    (net (code "717") (name "unconnected-(VD1C-OUT715-Pad715)") (class "Default")
      (node (ref "VD1") (pin "715") (pinfunction "OUT715_715") (pintype "passive"))
    )
    (net (code "718") (name "unconnected-(VD1C-OUT716-Pad716)") (class "Default")
      (node (ref "VD1") (pin "716") (pinfunction "OUT716_716") (pintype "passive"))
    )
    (net (code "719") (name "unconnected-(VD1C-OUT717-Pad717)") (class "Default")
      (node (ref "VD1") (pin "717") (pinfunction "OUT717_717") (pintype "passive"))
    )
    (net (code "720") (name "unconnected-(VD1C-OUT718-Pad718)") (class "Default")
      (node (ref "VD1") (pin "718") (pinfunction "OUT718_718") (pintype "passive"))
    )
    (net (code "721") (name "unconnected-(VD1C-OUT719-Pad719)") (class "Default")
      (node (ref "VD1") (pin "719") (pinfunction "OUT719_719") (pintype "passive"))
    )
    (net (code "722") (name "unconnected-(VD1C-OUT720-Pad720)") (class "Default")
      (node (ref "VD1") (pin "720") (pinfunction "OUT720_720") (pintype "passive"))
    )
    (net (code "723") (name "unconnected-(VD1C-OUT721-Pad721)") (class "Default")
      (node (ref "VD1") (pin "721") (pinfunction "OUT721_721") (pintype "passive"))
    )
    (net (code "724") (name "unconnected-(VD1C-OUT722-Pad722)") (class "Default")
      (node (ref "VD1") (pin "722") (pinfunction "OUT722_722") (pintype "passive"))
    )
    (net (code "725") (name "unconnected-(VD1C-OUT723-Pad723)") (class "Default")
      (node (ref "VD1") (pin "723") (pinfunction "OUT723_723") (pintype "passive"))
    )
    (net (code "726") (name "unconnected-(VD1C-OUT724-Pad724)") (class "Default")
      (node (ref "VD1") (pin "724") (pinfunction "OUT724_724") (pintype "passive"))
    )
    (net (code "727") (name "unconnected-(VD1C-OUT725-Pad725)") (class "Default")
      (node (ref "VD1") (pin "725") (pinfunction "OUT725_725") (pintype "passive"))
    )
    (net (code "728") (name "unconnected-(VD1C-OUT726-Pad726)") (class "Default")
      (node (ref "VD1") (pin "726") (pinfunction "OUT726_726") (pintype "passive"))
    )
    (net (code "729") (name "unconnected-(VD1C-OUT727-Pad727)") (class "Default")
      (node (ref "VD1") (pin "727") (pinfunction "OUT727_727") (pintype "passive"))
    )
    (net (code "730") (name "unconnected-(VD1C-OUT728-Pad728)") (class "Default")
      (node (ref "VD1") (pin "728") (pinfunction "OUT728_728") (pintype "passive"))
    )
    (net (code "731") (name "unconnected-(VD1C-OUT729-Pad729)") (class "Default")
      (node (ref "VD1") (pin "729") (pinfunction "OUT729_729") (pintype "passive"))
    )
    (net (code "732") (name "unconnected-(VD1C-OUT730-Pad730)") (class "Default")
      (node (ref "VD1") (pin "730") (pinfunction "OUT730_730") (pintype "passive"))
    )
    (net (code "733") (name "unconnected-(VD1C-OUT731-Pad731)") (class "Default")
      (node (ref "VD1") (pin "731") (pinfunction "OUT731_731") (pintype "passive"))
    )
    (net (code "734") (name "unconnected-(VD1C-OUT732-Pad732)") (class "Default")
      (node (ref "VD1") (pin "732") (pinfunction "OUT732_732") (pintype "passive"))
    )
    (net (code "735") (name "unconnected-(VD1C-OUT733-Pad733)") (class "Default")
      (node (ref "VD1") (pin "733") (pinfunction "OUT733_733") (pintype "passive"))
    )
    (net (code "736") (name "unconnected-(VD1C-OUT734-Pad734)") (class "Default")
      (node (ref "VD1") (pin "734") (pinfunction "OUT734_734") (pintype "passive"))
    )
    (net (code "737") (name "unconnected-(VD1C-OUT735-Pad735)") (class "Default")
      (node (ref "VD1") (pin "735") (pinfunction "OUT735_735") (pintype "passive"))
    )
    (net (code "738") (name "unconnected-(VD1C-OUT736-Pad736)") (class "Default")
      (node (ref "VD1") (pin "736") (pinfunction "OUT736_736") (pintype "passive"))
    )
    (net (code "739") (name "unconnected-(VD1C-OUT737-Pad737)") (class "Default")
      (node (ref "VD1") (pin "737") (pinfunction "OUT737_737") (pintype "passive"))
    )
    (net (code "740") (name "unconnected-(VD1C-OUT738-Pad738)") (class "Default")
      (node (ref "VD1") (pin "738") (pinfunction "OUT738_738") (pintype "passive"))
    )
    (net (code "741") (name "unconnected-(VD1C-OUT739-Pad739)") (class "Default")
      (node (ref "VD1") (pin "739") (pinfunction "OUT739_739") (pintype "passive"))
    )
    (net (code "742") (name "unconnected-(VD1C-OUT740-Pad740)") (class "Default")
      (node (ref "VD1") (pin "740") (pinfunction "OUT740_740") (pintype "passive"))
    )
    (net (code "743") (name "unconnected-(VD1C-OUT741-Pad741)") (class "Default")
      (node (ref "VD1") (pin "741") (pinfunction "OUT741_741") (pintype "passive"))
    )
    (net (code "744") (name "unconnected-(VD1C-OUT742-Pad742)") (class "Default")
      (node (ref "VD1") (pin "742") (pinfunction "OUT742_742") (pintype "passive"))
    )
    (net (code "745") (name "unconnected-(VD1C-OUT743-Pad743)") (class "Default")
      (node (ref "VD1") (pin "743") (pinfunction "OUT743_743") (pintype "passive"))
    )
    (net (code "746") (name "unconnected-(VD1C-OUT744-Pad744)") (class "Default")
      (node (ref "VD1") (pin "744") (pinfunction "OUT744_744") (pintype "passive"))
    )
    (net (code "747") (name "unconnected-(VD1C-OUT745-Pad745)") (class "Default")
      (node (ref "VD1") (pin "745") (pinfunction "OUT745_745") (pintype "passive"))
    )
    (net (code "748") (name "unconnected-(VD1C-OUT746-Pad746)") (class "Default")
      (node (ref "VD1") (pin "746") (pinfunction "OUT746_746") (pintype "passive"))
    )
    (net (code "749") (name "unconnected-(VD1C-OUT747-Pad747)") (class "Default")
      (node (ref "VD1") (pin "747") (pinfunction "OUT747_747") (pintype "passive"))
    )
    (net (code "750") (name "unconnected-(VD1C-OUT748-Pad748)") (class "Default")
      (node (ref "VD1") (pin "748") (pinfunction "OUT748_748") (pintype "passive"))
    )
    (net (code "751") (name "unconnected-(VD1C-OUT749-Pad749)") (class "Default")
      (node (ref "VD1") (pin "749") (pinfunction "OUT749_749") (pintype "passive"))
    )
    (net (code "752") (name "unconnected-(VD1C-OUT750-Pad750)") (class "Default")
      (node (ref "VD1") (pin "750") (pinfunction "OUT750_750") (pintype "passive"))
    )
    (net (code "753") (name "unconnected-(VD1C-OUT751-Pad751)") (class "Default")
      (node (ref "VD1") (pin "751") (pinfunction "OUT751_751") (pintype "passive"))
    )
    (net (code "754") (name "unconnected-(VD1C-OUT752-Pad752)") (class "Default")
      (node (ref "VD1") (pin "752") (pinfunction "OUT752_752") (pintype "passive"))
    )
    (net (code "755") (name "unconnected-(VD1C-OUT753-Pad753)") (class "Default")
      (node (ref "VD1") (pin "753") (pinfunction "OUT753_753") (pintype "passive"))
    )
    (net (code "756") (name "unconnected-(VD1C-OUT754-Pad754)") (class "Default")
      (node (ref "VD1") (pin "754") (pinfunction "OUT754_754") (pintype "passive"))
    )
    (net (code "757") (name "unconnected-(VD1C-OUT755-Pad755)") (class "Default")
      (node (ref "VD1") (pin "755") (pinfunction "OUT755_755") (pintype "passive"))
    )
    (net (code "758") (name "unconnected-(VD1C-OUT756-Pad756)") (class "Default")
      (node (ref "VD1") (pin "756") (pinfunction "OUT756_756") (pintype "passive"))
    )
    (net (code "759") (name "unconnected-(VD1C-OUT757-Pad757)") (class "Default")
      (node (ref "VD1") (pin "757") (pinfunction "OUT757_757") (pintype "passive"))
    )
    (net (code "760") (name "unconnected-(VD1C-OUT758-Pad758)") (class "Default")
      (node (ref "VD1") (pin "758") (pinfunction "OUT758_758") (pintype "passive"))
    )
    (net (code "761") (name "unconnected-(VD1C-OUT759-Pad759)") (class "Default")
      (node (ref "VD1") (pin "759") (pinfunction "OUT759_759") (pintype "passive"))
    )
    (net (code "762") (name "unconnected-(VD1C-OUT760-Pad760)") (class "Default")
      (node (ref "VD1") (pin "760") (pinfunction "OUT760_760") (pintype "passive"))
    )
    (net (code "763") (name "unconnected-(VD1C-OUT761-Pad761)") (class "Default")
      (node (ref "VD1") (pin "761") (pinfunction "OUT761_761") (pintype "passive"))
    )
    (net (code "764") (name "unconnected-(VD1C-OUT762-Pad762)") (class "Default")
      (node (ref "VD1") (pin "762") (pinfunction "OUT762_762") (pintype "passive"))
    )
    (net (code "765") (name "unconnected-(VD1C-OUT763-Pad763)") (class "Default")
      (node (ref "VD1") (pin "763") (pinfunction "OUT763_763") (pintype "passive"))
    )
    (net (code "766") (name "unconnected-(VD1C-OUT764-Pad764)") (class "Default")
      (node (ref "VD1") (pin "764") (pinfunction "OUT764_764") (pintype "passive"))
    )
    (net (code "767") (name "unconnected-(VD1C-OUT765-Pad765)") (class "Default")
      (node (ref "VD1") (pin "765") (pinfunction "OUT765_765") (pintype "passive"))
    )
    (net (code "768") (name "unconnected-(VD1C-OUT766-Pad766)") (class "Default")
      (node (ref "VD1") (pin "766") (pinfunction "OUT766_766") (pintype "passive"))
    )
    (net (code "769") (name "unconnected-(VD1C-OUT767-Pad767)") (class "Default")
      (node (ref "VD1") (pin "767") (pinfunction "OUT767_767") (pintype "passive"))
    )
    (net (code "770") (name "unconnected-(VD1C-OUT768-Pad768)") (class "Default")
      (node (ref "VD1") (pin "768") (pinfunction "OUT768_768") (pintype "passive"))
    )
    (net (code "771") (name "unconnected-(VD1D-OUT769-Pad769)") (class "Default")
      (node (ref "VD1") (pin "769") (pinfunction "OUT769_769") (pintype "passive"))
    )
    (net (code "772") (name "unconnected-(VD1D-OUT770-Pad770)") (class "Default")
      (node (ref "VD1") (pin "770") (pinfunction "OUT770_770") (pintype "passive"))
    )
    (net (code "773") (name "unconnected-(VD1D-OUT771-Pad771)") (class "Default")
      (node (ref "VD1") (pin "771") (pinfunction "OUT771_771") (pintype "passive"))
    )
    (net (code "774") (name "unconnected-(VD1D-OUT772-Pad772)") (class "Default")
      (node (ref "VD1") (pin "772") (pinfunction "OUT772_772") (pintype "passive"))
    )
    (net (code "775") (name "unconnected-(VD1D-OUT773-Pad773)") (class "Default")
      (node (ref "VD1") (pin "773") (pinfunction "OUT773_773") (pintype "passive"))
    )
    (net (code "776") (name "unconnected-(VD1D-OUT774-Pad774)") (class "Default")
      (node (ref "VD1") (pin "774") (pinfunction "OUT774_774") (pintype "passive"))
    )
    (net (code "777") (name "unconnected-(VD1D-OUT775-Pad775)") (class "Default")
      (node (ref "VD1") (pin "775") (pinfunction "OUT775_775") (pintype "passive"))
    )
    (net (code "778") (name "unconnected-(VD1D-OUT776-Pad776)") (class "Default")
      (node (ref "VD1") (pin "776") (pinfunction "OUT776_776") (pintype "passive"))
    )
    (net (code "779") (name "unconnected-(VD1D-OUT777-Pad777)") (class "Default")
      (node (ref "VD1") (pin "777") (pinfunction "OUT777_777") (pintype "passive"))
    )
    (net (code "780") (name "unconnected-(VD1D-OUT778-Pad778)") (class "Default")
      (node (ref "VD1") (pin "778") (pinfunction "OUT778_778") (pintype "passive"))
    )
    (net (code "781") (name "unconnected-(VD1D-OUT779-Pad779)") (class "Default")
      (node (ref "VD1") (pin "779") (pinfunction "OUT779_779") (pintype "passive"))
    )
    (net (code "782") (name "unconnected-(VD1D-OUT780-Pad780)") (class "Default")
      (node (ref "VD1") (pin "780") (pinfunction "OUT780_780") (pintype "passive"))
    )
    (net (code "783") (name "unconnected-(VD1D-OUT781-Pad781)") (class "Default")
      (node (ref "VD1") (pin "781") (pinfunction "OUT781_781") (pintype "passive"))
    )
    (net (code "784") (name "unconnected-(VD1D-OUT782-Pad782)") (class "Default")
      (node (ref "VD1") (pin "782") (pinfunction "OUT782_782") (pintype "passive"))
    )
    (net (code "785") (name "unconnected-(VD1D-OUT783-Pad783)") (class "Default")
      (node (ref "VD1") (pin "783") (pinfunction "OUT783_783") (pintype "passive"))
    )
    (net (code "786") (name "unconnected-(VD1D-OUT784-Pad784)") (class "Default")
      (node (ref "VD1") (pin "784") (pinfunction "OUT784_784") (pintype "passive"))
    )
    (net (code "787") (name "unconnected-(VD1D-OUT785-Pad785)") (class "Default")
      (node (ref "VD1") (pin "785") (pinfunction "OUT785_785") (pintype "passive"))
    )
    (net (code "788") (name "unconnected-(VD1D-OUT786-Pad786)") (class "Default")
      (node (ref "VD1") (pin "786") (pinfunction "OUT786_786") (pintype "passive"))
    )
    (net (code "789") (name "unconnected-(VD1D-OUT787-Pad787)") (class "Default")
      (node (ref "VD1") (pin "787") (pinfunction "OUT787_787") (pintype "passive"))
    )
    (net (code "790") (name "unconnected-(VD1D-OUT788-Pad788)") (class "Default")
      (node (ref "VD1") (pin "788") (pinfunction "OUT788_788") (pintype "passive"))
    )
    (net (code "791") (name "unconnected-(VD1D-OUT789-Pad789)") (class "Default")
      (node (ref "VD1") (pin "789") (pinfunction "OUT789_789") (pintype "passive"))
    )
    (net (code "792") (name "unconnected-(VD1D-OUT790-Pad790)") (class "Default")
      (node (ref "VD1") (pin "790") (pinfunction "OUT790_790") (pintype "passive"))
    )
    (net (code "793") (name "unconnected-(VD1D-OUT791-Pad791)") (class "Default")
      (node (ref "VD1") (pin "791") (pinfunction "OUT791_791") (pintype "passive"))
    )
    (net (code "794") (name "unconnected-(VD1D-OUT792-Pad792)") (class "Default")
      (node (ref "VD1") (pin "792") (pinfunction "OUT792_792") (pintype "passive"))
    )
    (net (code "795") (name "unconnected-(VD1D-OUT793-Pad793)") (class "Default")
      (node (ref "VD1") (pin "793") (pinfunction "OUT793_793") (pintype "passive"))
    )
    (net (code "796") (name "unconnected-(VD1D-OUT794-Pad794)") (class "Default")
      (node (ref "VD1") (pin "794") (pinfunction "OUT794_794") (pintype "passive"))
    )
    (net (code "797") (name "unconnected-(VD1D-OUT795-Pad795)") (class "Default")
      (node (ref "VD1") (pin "795") (pinfunction "OUT795_795") (pintype "passive"))
    )
    (net (code "798") (name "unconnected-(VD1D-OUT796-Pad796)") (class "Default")
      (node (ref "VD1") (pin "796") (pinfunction "OUT796_796") (pintype "passive"))
    )
    (net (code "799") (name "unconnected-(VD1D-OUT797-Pad797)") (class "Default")
      (node (ref "VD1") (pin "797") (pinfunction "OUT797_797") (pintype "passive"))
    )
    (net (code "800") (name "unconnected-(VD1D-OUT798-Pad798)") (class "Default")
      (node (ref "VD1") (pin "798") (pinfunction "OUT798_798") (pintype "passive"))
    )
    (net (code "801") (name "unconnected-(VD1D-OUT799-Pad799)") (class "Default")
      (node (ref "VD1") (pin "799") (pinfunction "OUT799_799") (pintype "passive"))
    )
    (net (code "802") (name "unconnected-(VD1D-OUT800-Pad800)") (class "Default")
      (node (ref "VD1") (pin "800") (pinfunction "OUT800_800") (pintype "passive"))
    )
    (net (code "803") (name "unconnected-(VD1D-OUT801-Pad801)") (class "Default")
      (node (ref "VD1") (pin "801") (pinfunction "OUT801_801") (pintype "passive"))
    )
    (net (code "804") (name "unconnected-(VD1D-OUT802-Pad802)") (class "Default")
      (node (ref "VD1") (pin "802") (pinfunction "OUT802_802") (pintype "passive"))
    )
    (net (code "805") (name "unconnected-(VD1D-OUT803-Pad803)") (class "Default")
      (node (ref "VD1") (pin "803") (pinfunction "OUT803_803") (pintype "passive"))
    )
    (net (code "806") (name "unconnected-(VD1D-OUT804-Pad804)") (class "Default")
      (node (ref "VD1") (pin "804") (pinfunction "OUT804_804") (pintype "passive"))
    )
    (net (code "807") (name "unconnected-(VD1D-OUT805-Pad805)") (class "Default")
      (node (ref "VD1") (pin "805") (pinfunction "OUT805_805") (pintype "passive"))
    )
    (net (code "808") (name "unconnected-(VD1D-OUT806-Pad806)") (class "Default")
      (node (ref "VD1") (pin "806") (pinfunction "OUT806_806") (pintype "passive"))
    )
    (net (code "809") (name "unconnected-(VD1D-OUT807-Pad807)") (class "Default")
      (node (ref "VD1") (pin "807") (pinfunction "OUT807_807") (pintype "passive"))
    )
    (net (code "810") (name "unconnected-(VD1D-OUT808-Pad808)") (class "Default")
      (node (ref "VD1") (pin "808") (pinfunction "OUT808_808") (pintype "passive"))
    )
    (net (code "811") (name "unconnected-(VD1D-OUT809-Pad809)") (class "Default")
      (node (ref "VD1") (pin "809") (pinfunction "OUT809_809") (pintype "passive"))
    )
    (net (code "812") (name "unconnected-(VD1D-OUT810-Pad810)") (class "Default")
      (node (ref "VD1") (pin "810") (pinfunction "OUT810_810") (pintype "passive"))
    )
    (net (code "813") (name "unconnected-(VD1D-OUT811-Pad811)") (class "Default")
      (node (ref "VD1") (pin "811") (pinfunction "OUT811_811") (pintype "passive"))
    )
    (net (code "814") (name "unconnected-(VD1D-OUT812-Pad812)") (class "Default")
      (node (ref "VD1") (pin "812") (pinfunction "OUT812_812") (pintype "passive"))
    )
    (net (code "815") (name "unconnected-(VD1D-OUT813-Pad813)") (class "Default")
      (node (ref "VD1") (pin "813") (pinfunction "OUT813_813") (pintype "passive"))
    )
    (net (code "816") (name "unconnected-(VD1D-OUT814-Pad814)") (class "Default")
      (node (ref "VD1") (pin "814") (pinfunction "OUT814_814") (pintype "passive"))
    )
    (net (code "817") (name "unconnected-(VD1D-OUT815-Pad815)") (class "Default")
      (node (ref "VD1") (pin "815") (pinfunction "OUT815_815") (pintype "passive"))
    )
    (net (code "818") (name "unconnected-(VD1D-OUT816-Pad816)") (class "Default")
      (node (ref "VD1") (pin "816") (pinfunction "OUT816_816") (pintype "passive"))
    )
    (net (code "819") (name "unconnected-(VD1D-OUT817-Pad817)") (class "Default")
      (node (ref "VD1") (pin "817") (pinfunction "OUT817_817") (pintype "passive"))
    )
    (net (code "820") (name "unconnected-(VD1D-OUT818-Pad818)") (class "Default")
      (node (ref "VD1") (pin "818") (pinfunction "OUT818_818") (pintype "passive"))
    )
    (net (code "821") (name "unconnected-(VD1D-OUT819-Pad819)") (class "Default")
      (node (ref "VD1") (pin "819") (pinfunction "OUT819_819") (pintype "passive"))
    )
    (net (code "822") (name "unconnected-(VD1D-OUT820-Pad820)") (class "Default")
      (node (ref "VD1") (pin "820") (pinfunction "OUT820_820") (pintype "passive"))
    )
    (net (code "823") (name "unconnected-(VD1D-OUT821-Pad821)") (class "Default")
      (node (ref "VD1") (pin "821") (pinfunction "OUT821_821") (pintype "passive"))
    )
    (net (code "824") (name "unconnected-(VD1D-OUT822-Pad822)") (class "Default")
      (node (ref "VD1") (pin "822") (pinfunction "OUT822_822") (pintype "passive"))
    )
    (net (code "825") (name "unconnected-(VD1D-OUT823-Pad823)") (class "Default")
      (node (ref "VD1") (pin "823") (pinfunction "OUT823_823") (pintype "passive"))
    )
    (net (code "826") (name "unconnected-(VD1D-OUT824-Pad824)") (class "Default")
      (node (ref "VD1") (pin "824") (pinfunction "OUT824_824") (pintype "passive"))
    )
    (net (code "827") (name "unconnected-(VD1D-OUT825-Pad825)") (class "Default")
      (node (ref "VD1") (pin "825") (pinfunction "OUT825_825") (pintype "passive"))
    )
    (net (code "828") (name "unconnected-(VD1D-OUT826-Pad826)") (class "Default")
      (node (ref "VD1") (pin "826") (pinfunction "OUT826_826") (pintype "passive"))
    )
    (net (code "829") (name "unconnected-(VD1D-OUT827-Pad827)") (class "Default")
      (node (ref "VD1") (pin "827") (pinfunction "OUT827_827") (pintype "passive"))
    )
    (net (code "830") (name "unconnected-(VD1D-OUT828-Pad828)") (class "Default")
      (node (ref "VD1") (pin "828") (pinfunction "OUT828_828") (pintype "passive"))
    )
    (net (code "831") (name "unconnected-(VD1D-OUT829-Pad829)") (class "Default")
      (node (ref "VD1") (pin "829") (pinfunction "OUT829_829") (pintype "passive"))
    )
    (net (code "832") (name "unconnected-(VD1D-OUT830-Pad830)") (class "Default")
      (node (ref "VD1") (pin "830") (pinfunction "OUT830_830") (pintype "passive"))
    )
    (net (code "833") (name "unconnected-(VD1D-OUT831-Pad831)") (class "Default")
      (node (ref "VD1") (pin "831") (pinfunction "OUT831_831") (pintype "passive"))
    )
    (net (code "834") (name "unconnected-(VD1D-OUT832-Pad832)") (class "Default")
      (node (ref "VD1") (pin "832") (pinfunction "OUT832_832") (pintype "passive"))
    )
    (net (code "835") (name "unconnected-(VD1D-OUT833-Pad833)") (class "Default")
      (node (ref "VD1") (pin "833") (pinfunction "OUT833_833") (pintype "passive"))
    )
    (net (code "836") (name "unconnected-(VD1D-OUT834-Pad834)") (class "Default")
      (node (ref "VD1") (pin "834") (pinfunction "OUT834_834") (pintype "passive"))
    )
    (net (code "837") (name "unconnected-(VD1D-OUT835-Pad835)") (class "Default")
      (node (ref "VD1") (pin "835") (pinfunction "OUT835_835") (pintype "passive"))
    )
    (net (code "838") (name "unconnected-(VD1D-OUT836-Pad836)") (class "Default")
      (node (ref "VD1") (pin "836") (pinfunction "OUT836_836") (pintype "passive"))
    )
    (net (code "839") (name "unconnected-(VD1D-OUT837-Pad837)") (class "Default")
      (node (ref "VD1") (pin "837") (pinfunction "OUT837_837") (pintype "passive"))
    )
    (net (code "840") (name "unconnected-(VD1D-OUT838-Pad838)") (class "Default")
      (node (ref "VD1") (pin "838") (pinfunction "OUT838_838") (pintype "passive"))
    )
    (net (code "841") (name "unconnected-(VD1D-OUT839-Pad839)") (class "Default")
      (node (ref "VD1") (pin "839") (pinfunction "OUT839_839") (pintype "passive"))
    )
    (net (code "842") (name "unconnected-(VD1D-OUT840-Pad840)") (class "Default")
      (node (ref "VD1") (pin "840") (pinfunction "OUT840_840") (pintype "passive"))
    )
    (net (code "843") (name "unconnected-(VD1D-OUT841-Pad841)") (class "Default")
      (node (ref "VD1") (pin "841") (pinfunction "OUT841_841") (pintype "passive"))
    )
    (net (code "844") (name "unconnected-(VD1D-OUT842-Pad842)") (class "Default")
      (node (ref "VD1") (pin "842") (pinfunction "OUT842_842") (pintype "passive"))
    )
    (net (code "845") (name "unconnected-(VD1D-OUT843-Pad843)") (class "Default")
      (node (ref "VD1") (pin "843") (pinfunction "OUT843_843") (pintype "passive"))
    )
    (net (code "846") (name "unconnected-(VD1D-OUT844-Pad844)") (class "Default")
      (node (ref "VD1") (pin "844") (pinfunction "OUT844_844") (pintype "passive"))
    )
    (net (code "847") (name "unconnected-(VD1D-OUT845-Pad845)") (class "Default")
      (node (ref "VD1") (pin "845") (pinfunction "OUT845_845") (pintype "passive"))
    )
    (net (code "848") (name "unconnected-(VD1D-OUT846-Pad846)") (class "Default")
      (node (ref "VD1") (pin "846") (pinfunction "OUT846_846") (pintype "passive"))
    )
    (net (code "849") (name "unconnected-(VD1D-OUT847-Pad847)") (class "Default")
      (node (ref "VD1") (pin "847") (pinfunction "OUT847_847") (pintype "passive"))
    )
    (net (code "850") (name "unconnected-(VD1D-OUT848-Pad848)") (class "Default")
      (node (ref "VD1") (pin "848") (pinfunction "OUT848_848") (pintype "passive"))
    )
    (net (code "851") (name "unconnected-(VD1D-OUT849-Pad849)") (class "Default")
      (node (ref "VD1") (pin "849") (pinfunction "OUT849_849") (pintype "passive"))
    )
    (net (code "852") (name "unconnected-(VD1D-OUT850-Pad850)") (class "Default")
      (node (ref "VD1") (pin "850") (pinfunction "OUT850_850") (pintype "passive"))
    )
    (net (code "853") (name "unconnected-(VD1D-OUT851-Pad851)") (class "Default")
      (node (ref "VD1") (pin "851") (pinfunction "OUT851_851") (pintype "passive"))
    )
    (net (code "854") (name "unconnected-(VD1D-OUT852-Pad852)") (class "Default")
      (node (ref "VD1") (pin "852") (pinfunction "OUT852_852") (pintype "passive"))
    )
    (net (code "855") (name "unconnected-(VD1D-OUT853-Pad853)") (class "Default")
      (node (ref "VD1") (pin "853") (pinfunction "OUT853_853") (pintype "passive"))
    )
    (net (code "856") (name "unconnected-(VD1D-OUT854-Pad854)") (class "Default")
      (node (ref "VD1") (pin "854") (pinfunction "OUT854_854") (pintype "passive"))
    )
    (net (code "857") (name "unconnected-(VD1D-OUT855-Pad855)") (class "Default")
      (node (ref "VD1") (pin "855") (pinfunction "OUT855_855") (pintype "passive"))
    )
    (net (code "858") (name "unconnected-(VD1D-OUT856-Pad856)") (class "Default")
      (node (ref "VD1") (pin "856") (pinfunction "OUT856_856") (pintype "passive"))
    )
    (net (code "859") (name "unconnected-(VD1D-OUT857-Pad857)") (class "Default")
      (node (ref "VD1") (pin "857") (pinfunction "OUT857_857") (pintype "passive"))
    )
    (net (code "860") (name "unconnected-(VD1D-OUT858-Pad858)") (class "Default")
      (node (ref "VD1") (pin "858") (pinfunction "OUT858_858") (pintype "passive"))
    )
    (net (code "861") (name "unconnected-(VD1D-OUT859-Pad859)") (class "Default")
      (node (ref "VD1") (pin "859") (pinfunction "OUT859_859") (pintype "passive"))
    )
    (net (code "862") (name "unconnected-(VD1D-OUT860-Pad860)") (class "Default")
      (node (ref "VD1") (pin "860") (pinfunction "OUT860_860") (pintype "passive"))
    )
    (net (code "863") (name "unconnected-(VD1D-OUT861-Pad861)") (class "Default")
      (node (ref "VD1") (pin "861") (pinfunction "OUT861_861") (pintype "passive"))
    )
    (net (code "864") (name "unconnected-(VD1D-OUT862-Pad862)") (class "Default")
      (node (ref "VD1") (pin "862") (pinfunction "OUT862_862") (pintype "passive"))
    )
    (net (code "865") (name "unconnected-(VD1D-OUT863-Pad863)") (class "Default")
      (node (ref "VD1") (pin "863") (pinfunction "OUT863_863") (pintype "passive"))
    )
    (net (code "866") (name "unconnected-(VD1D-OUT864-Pad864)") (class "Default")
      (node (ref "VD1") (pin "864") (pinfunction "OUT864_864") (pintype "passive"))
    )
    (net (code "867") (name "unconnected-(VD1D-OUT865-Pad865)") (class "Default")
      (node (ref "VD1") (pin "865") (pinfunction "OUT865_865") (pintype "passive"))
    )
    (net (code "868") (name "unconnected-(VD1D-OUT866-Pad866)") (class "Default")
      (node (ref "VD1") (pin "866") (pinfunction "OUT866_866") (pintype "passive"))
    )
    (net (code "869") (name "unconnected-(VD1D-OUT867-Pad867)") (class "Default")
      (node (ref "VD1") (pin "867") (pinfunction "OUT867_867") (pintype "passive"))
    )
    (net (code "870") (name "unconnected-(VD1D-OUT868-Pad868)") (class "Default")
      (node (ref "VD1") (pin "868") (pinfunction "OUT868_868") (pintype "passive"))
    )
    (net (code "871") (name "unconnected-(VD1D-OUT869-Pad869)") (class "Default")
      (node (ref "VD1") (pin "869") (pinfunction "OUT869_869") (pintype "passive"))
    )
    (net (code "872") (name "unconnected-(VD1D-OUT870-Pad870)") (class "Default")
      (node (ref "VD1") (pin "870") (pinfunction "OUT870_870") (pintype "passive"))
    )
    (net (code "873") (name "unconnected-(VD1D-OUT871-Pad871)") (class "Default")
      (node (ref "VD1") (pin "871") (pinfunction "OUT871_871") (pintype "passive"))
    )
    (net (code "874") (name "unconnected-(VD1D-OUT872-Pad872)") (class "Default")
      (node (ref "VD1") (pin "872") (pinfunction "OUT872_872") (pintype "passive"))
    )
    (net (code "875") (name "unconnected-(VD1D-OUT873-Pad873)") (class "Default")
      (node (ref "VD1") (pin "873") (pinfunction "OUT873_873") (pintype "passive"))
    )
    (net (code "876") (name "unconnected-(VD1D-OUT874-Pad874)") (class "Default")
      (node (ref "VD1") (pin "874") (pinfunction "OUT874_874") (pintype "passive"))
    )
    (net (code "877") (name "unconnected-(VD1D-OUT875-Pad875)") (class "Default")
      (node (ref "VD1") (pin "875") (pinfunction "OUT875_875") (pintype "passive"))
    )
    (net (code "878") (name "unconnected-(VD1D-OUT876-Pad876)") (class "Default")
      (node (ref "VD1") (pin "876") (pinfunction "OUT876_876") (pintype "passive"))
    )
    (net (code "879") (name "unconnected-(VD1D-OUT877-Pad877)") (class "Default")
      (node (ref "VD1") (pin "877") (pinfunction "OUT877_877") (pintype "passive"))
    )
    (net (code "880") (name "unconnected-(VD1D-OUT878-Pad878)") (class "Default")
      (node (ref "VD1") (pin "878") (pinfunction "OUT878_878") (pintype "passive"))
    )
    (net (code "881") (name "unconnected-(VD1D-OUT879-Pad879)") (class "Default")
      (node (ref "VD1") (pin "879") (pinfunction "OUT879_879") (pintype "passive"))
    )
    (net (code "882") (name "unconnected-(VD1D-OUT880-Pad880)") (class "Default")
      (node (ref "VD1") (pin "880") (pinfunction "OUT880_880") (pintype "passive"))
    )
    (net (code "883") (name "unconnected-(VD1D-OUT881-Pad881)") (class "Default")
      (node (ref "VD1") (pin "881") (pinfunction "OUT881_881") (pintype "passive"))
    )
    (net (code "884") (name "unconnected-(VD1D-OUT882-Pad882)") (class "Default")
      (node (ref "VD1") (pin "882") (pinfunction "OUT882_882") (pintype "passive"))
    )
    (net (code "885") (name "unconnected-(VD1D-OUT883-Pad883)") (class "Default")
      (node (ref "VD1") (pin "883") (pinfunction "OUT883_883") (pintype "passive"))
    )
    (net (code "886") (name "unconnected-(VD1D-OUT884-Pad884)") (class "Default")
      (node (ref "VD1") (pin "884") (pinfunction "OUT884_884") (pintype "passive"))
    )
    (net (code "887") (name "unconnected-(VD1D-OUT885-Pad885)") (class "Default")
      (node (ref "VD1") (pin "885") (pinfunction "OUT885_885") (pintype "passive"))
    )
    (net (code "888") (name "unconnected-(VD1D-OUT886-Pad886)") (class "Default")
      (node (ref "VD1") (pin "886") (pinfunction "OUT886_886") (pintype "passive"))
    )
    (net (code "889") (name "unconnected-(VD1D-OUT887-Pad887)") (class "Default")
      (node (ref "VD1") (pin "887") (pinfunction "OUT887_887") (pintype "passive"))
    )
    (net (code "890") (name "unconnected-(VD1D-OUT888-Pad888)") (class "Default")
      (node (ref "VD1") (pin "888") (pinfunction "OUT888_888") (pintype "passive"))
    )
    (net (code "891") (name "unconnected-(VD1D-OUT889-Pad889)") (class "Default")
      (node (ref "VD1") (pin "889") (pinfunction "OUT889_889") (pintype "passive"))
    )
    (net (code "892") (name "unconnected-(VD1D-OUT890-Pad890)") (class "Default")
      (node (ref "VD1") (pin "890") (pinfunction "OUT890_890") (pintype "passive"))
    )
    (net (code "893") (name "unconnected-(VD1D-OUT891-Pad891)") (class "Default")
      (node (ref "VD1") (pin "891") (pinfunction "OUT891_891") (pintype "passive"))
    )
    (net (code "894") (name "unconnected-(VD1D-OUT892-Pad892)") (class "Default")
      (node (ref "VD1") (pin "892") (pinfunction "OUT892_892") (pintype "passive"))
    )
    (net (code "895") (name "unconnected-(VD1D-OUT893-Pad893)") (class "Default")
      (node (ref "VD1") (pin "893") (pinfunction "OUT893_893") (pintype "passive"))
    )
    (net (code "896") (name "unconnected-(VD1D-OUT894-Pad894)") (class "Default")
      (node (ref "VD1") (pin "894") (pinfunction "OUT894_894") (pintype "passive"))
    )
    (net (code "897") (name "unconnected-(VD1D-OUT895-Pad895)") (class "Default")
      (node (ref "VD1") (pin "895") (pinfunction "OUT895_895") (pintype "passive"))
    )
    (net (code "898") (name "unconnected-(VD1D-OUT896-Pad896)") (class "Default")
      (node (ref "VD1") (pin "896") (pinfunction "OUT896_896") (pintype "passive"))
    )
    (net (code "899") (name "unconnected-(VD1D-OUT897-Pad897)") (class "Default")
      (node (ref "VD1") (pin "897") (pinfunction "OUT897_897") (pintype "passive"))
    )
    (net (code "900") (name "unconnected-(VD1D-OUT898-Pad898)") (class "Default")
      (node (ref "VD1") (pin "898") (pinfunction "OUT898_898") (pintype "passive"))
    )
    (net (code "901") (name "unconnected-(VD1D-OUT899-Pad899)") (class "Default")
      (node (ref "VD1") (pin "899") (pinfunction "OUT899_899") (pintype "passive"))
    )
    (net (code "902") (name "unconnected-(VD1D-OUT900-Pad900)") (class "Default")
      (node (ref "VD1") (pin "900") (pinfunction "OUT900_900") (pintype "passive"))
    )
    (net (code "903") (name "unconnected-(VD1D-OUT901-Pad901)") (class "Default")
      (node (ref "VD1") (pin "901") (pinfunction "OUT901_901") (pintype "passive"))
    )
    (net (code "904") (name "unconnected-(VD1D-OUT902-Pad902)") (class "Default")
      (node (ref "VD1") (pin "902") (pinfunction "OUT902_902") (pintype "passive"))
    )
    (net (code "905") (name "unconnected-(VD1D-OUT903-Pad903)") (class "Default")
      (node (ref "VD1") (pin "903") (pinfunction "OUT903_903") (pintype "passive"))
    )
    (net (code "906") (name "unconnected-(VD1D-OUT904-Pad904)") (class "Default")
      (node (ref "VD1") (pin "904") (pinfunction "OUT904_904") (pintype "passive"))
    )
    (net (code "907") (name "unconnected-(VD1D-OUT905-Pad905)") (class "Default")
      (node (ref "VD1") (pin "905") (pinfunction "OUT905_905") (pintype "passive"))
    )
    (net (code "908") (name "unconnected-(VD1D-OUT906-Pad906)") (class "Default")
      (node (ref "VD1") (pin "906") (pinfunction "OUT906_906") (pintype "passive"))
    )
    (net (code "909") (name "unconnected-(VD1D-OUT907-Pad907)") (class "Default")
      (node (ref "VD1") (pin "907") (pinfunction "OUT907_907") (pintype "passive"))
    )
    (net (code "910") (name "unconnected-(VD1D-OUT908-Pad908)") (class "Default")
      (node (ref "VD1") (pin "908") (pinfunction "OUT908_908") (pintype "passive"))
    )
    (net (code "911") (name "unconnected-(VD1D-OUT909-Pad909)") (class "Default")
      (node (ref "VD1") (pin "909") (pinfunction "OUT909_909") (pintype "passive"))
    )
    (net (code "912") (name "unconnected-(VD1D-OUT910-Pad910)") (class "Default")
      (node (ref "VD1") (pin "910") (pinfunction "OUT910_910") (pintype "passive"))
    )
    (net (code "913") (name "unconnected-(VD1D-OUT911-Pad911)") (class "Default")
      (node (ref "VD1") (pin "911") (pinfunction "OUT911_911") (pintype "passive"))
    )
    (net (code "914") (name "unconnected-(VD1D-OUT912-Pad912)") (class "Default")
      (node (ref "VD1") (pin "912") (pinfunction "OUT912_912") (pintype "passive"))
    )
    (net (code "915") (name "unconnected-(VD1D-OUT913-Pad913)") (class "Default")
      (node (ref "VD1") (pin "913") (pinfunction "OUT913_913") (pintype "passive"))
    )
    (net (code "916") (name "unconnected-(VD1D-OUT914-Pad914)") (class "Default")
      (node (ref "VD1") (pin "914") (pinfunction "OUT914_914") (pintype "passive"))
    )
    (net (code "917") (name "unconnected-(VD1D-OUT915-Pad915)") (class "Default")
      (node (ref "VD1") (pin "915") (pinfunction "OUT915_915") (pintype "passive"))
    )
    (net (code "918") (name "unconnected-(VD1D-OUT916-Pad916)") (class "Default")
      (node (ref "VD1") (pin "916") (pinfunction "OUT916_916") (pintype "passive"))
    )
    (net (code "919") (name "unconnected-(VD1D-OUT917-Pad917)") (class "Default")
      (node (ref "VD1") (pin "917") (pinfunction "OUT917_917") (pintype "passive"))
    )
    (net (code "920") (name "unconnected-(VD1D-OUT918-Pad918)") (class "Default")
      (node (ref "VD1") (pin "918") (pinfunction "OUT918_918") (pintype "passive"))
    )
    (net (code "921") (name "unconnected-(VD1D-OUT919-Pad919)") (class "Default")
      (node (ref "VD1") (pin "919") (pinfunction "OUT919_919") (pintype "passive"))
    )
    (net (code "922") (name "unconnected-(VD1D-OUT920-Pad920)") (class "Default")
      (node (ref "VD1") (pin "920") (pinfunction "OUT920_920") (pintype "passive"))
    )
    (net (code "923") (name "unconnected-(VD1D-OUT921-Pad921)") (class "Default")
      (node (ref "VD1") (pin "921") (pinfunction "OUT921_921") (pintype "passive"))
    )
    (net (code "924") (name "unconnected-(VD1D-OUT922-Pad922)") (class "Default")
      (node (ref "VD1") (pin "922") (pinfunction "OUT922_922") (pintype "passive"))
    )
    (net (code "925") (name "unconnected-(VD1D-OUT923-Pad923)") (class "Default")
      (node (ref "VD1") (pin "923") (pinfunction "OUT923_923") (pintype "passive"))
    )
    (net (code "926") (name "unconnected-(VD1D-OUT924-Pad924)") (class "Default")
      (node (ref "VD1") (pin "924") (pinfunction "OUT924_924") (pintype "passive"))
    )
    (net (code "927") (name "unconnected-(VD1D-OUT925-Pad925)") (class "Default")
      (node (ref "VD1") (pin "925") (pinfunction "OUT925_925") (pintype "passive"))
    )
    (net (code "928") (name "unconnected-(VD1D-OUT926-Pad926)") (class "Default")
      (node (ref "VD1") (pin "926") (pinfunction "OUT926_926") (pintype "passive"))
    )
    (net (code "929") (name "unconnected-(VD1D-OUT927-Pad927)") (class "Default")
      (node (ref "VD1") (pin "927") (pinfunction "OUT927_927") (pintype "passive"))
    )
    (net (code "930") (name "unconnected-(VD1D-OUT928-Pad928)") (class "Default")
      (node (ref "VD1") (pin "928") (pinfunction "OUT928_928") (pintype "passive"))
    )
    (net (code "931") (name "unconnected-(VD1D-OUT929-Pad929)") (class "Default")
      (node (ref "VD1") (pin "929") (pinfunction "OUT929_929") (pintype "passive"))
    )
    (net (code "932") (name "unconnected-(VD1D-OUT930-Pad930)") (class "Default")
      (node (ref "VD1") (pin "930") (pinfunction "OUT930_930") (pintype "passive"))
    )
    (net (code "933") (name "unconnected-(VD1D-OUT931-Pad931)") (class "Default")
      (node (ref "VD1") (pin "931") (pinfunction "OUT931_931") (pintype "passive"))
    )
    (net (code "934") (name "unconnected-(VD1D-OUT932-Pad932)") (class "Default")
      (node (ref "VD1") (pin "932") (pinfunction "OUT932_932") (pintype "passive"))
    )
    (net (code "935") (name "unconnected-(VD1D-OUT933-Pad933)") (class "Default")
      (node (ref "VD1") (pin "933") (pinfunction "OUT933_933") (pintype "passive"))
    )
    (net (code "936") (name "unconnected-(VD1D-OUT934-Pad934)") (class "Default")
      (node (ref "VD1") (pin "934") (pinfunction "OUT934_934") (pintype "passive"))
    )
    (net (code "937") (name "unconnected-(VD1D-OUT935-Pad935)") (class "Default")
      (node (ref "VD1") (pin "935") (pinfunction "OUT935_935") (pintype "passive"))
    )
    (net (code "938") (name "unconnected-(VD1D-OUT936-Pad936)") (class "Default")
      (node (ref "VD1") (pin "936") (pinfunction "OUT936_936") (pintype "passive"))
    )
    (net (code "939") (name "unconnected-(VD1D-OUT937-Pad937)") (class "Default")
      (node (ref "VD1") (pin "937") (pinfunction "OUT937_937") (pintype "passive"))
    )
    (net (code "940") (name "unconnected-(VD1D-OUT938-Pad938)") (class "Default")
      (node (ref "VD1") (pin "938") (pinfunction "OUT938_938") (pintype "passive"))
    )
    (net (code "941") (name "unconnected-(VD1D-OUT939-Pad939)") (class "Default")
      (node (ref "VD1") (pin "939") (pinfunction "OUT939_939") (pintype "passive"))
    )
    (net (code "942") (name "unconnected-(VD1D-OUT940-Pad940)") (class "Default")
      (node (ref "VD1") (pin "940") (pinfunction "OUT940_940") (pintype "passive"))
    )
    (net (code "943") (name "unconnected-(VD1D-OUT941-Pad941)") (class "Default")
      (node (ref "VD1") (pin "941") (pinfunction "OUT941_941") (pintype "passive"))
    )
    (net (code "944") (name "unconnected-(VD1D-OUT942-Pad942)") (class "Default")
      (node (ref "VD1") (pin "942") (pinfunction "OUT942_942") (pintype "passive"))
    )
    (net (code "945") (name "unconnected-(VD1D-OUT943-Pad943)") (class "Default")
      (node (ref "VD1") (pin "943") (pinfunction "OUT943_943") (pintype "passive"))
    )
    (net (code "946") (name "unconnected-(VD1D-OUT944-Pad944)") (class "Default")
      (node (ref "VD1") (pin "944") (pinfunction "OUT944_944") (pintype "passive"))
    )
    (net (code "947") (name "unconnected-(VD1D-OUT945-Pad945)") (class "Default")
      (node (ref "VD1") (pin "945") (pinfunction "OUT945_945") (pintype "passive"))
    )
    (net (code "948") (name "unconnected-(VD1D-OUT946-Pad946)") (class "Default")
      (node (ref "VD1") (pin "946") (pinfunction "OUT946_946") (pintype "passive"))
    )
    (net (code "949") (name "unconnected-(VD1D-OUT947-Pad947)") (class "Default")
      (node (ref "VD1") (pin "947") (pinfunction "OUT947_947") (pintype "passive"))
    )
    (net (code "950") (name "unconnected-(VD1D-OUT948-Pad948)") (class "Default")
      (node (ref "VD1") (pin "948") (pinfunction "OUT948_948") (pintype "passive"))
    )
    (net (code "951") (name "unconnected-(VD1D-OUT949-Pad949)") (class "Default")
      (node (ref "VD1") (pin "949") (pinfunction "OUT949_949") (pintype "passive"))
    )
    (net (code "952") (name "unconnected-(VD1D-OUT950-Pad950)") (class "Default")
      (node (ref "VD1") (pin "950") (pinfunction "OUT950_950") (pintype "passive"))
    )
    (net (code "953") (name "unconnected-(VD1D-OUT951-Pad951)") (class "Default")
      (node (ref "VD1") (pin "951") (pinfunction "OUT951_951") (pintype "passive"))
    )
    (net (code "954") (name "unconnected-(VD1D-OUT952-Pad952)") (class "Default")
      (node (ref "VD1") (pin "952") (pinfunction "OUT952_952") (pintype "passive"))
    )
    (net (code "955") (name "unconnected-(VD1D-OUT953-Pad953)") (class "Default")
      (node (ref "VD1") (pin "953") (pinfunction "OUT953_953") (pintype "passive"))
    )
    (net (code "956") (name "unconnected-(VD1D-OUT954-Pad954)") (class "Default")
      (node (ref "VD1") (pin "954") (pinfunction "OUT954_954") (pintype "passive"))
    )
    (net (code "957") (name "unconnected-(VD1D-OUT955-Pad955)") (class "Default")
      (node (ref "VD1") (pin "955") (pinfunction "OUT955_955") (pintype "passive"))
    )
    (net (code "958") (name "unconnected-(VD1D-OUT956-Pad956)") (class "Default")
      (node (ref "VD1") (pin "956") (pinfunction "OUT956_956") (pintype "passive"))
    )
    (net (code "959") (name "unconnected-(VD1D-OUT957-Pad957)") (class "Default")
      (node (ref "VD1") (pin "957") (pinfunction "OUT957_957") (pintype "passive"))
    )
    (net (code "960") (name "unconnected-(VD1D-OUT958-Pad958)") (class "Default")
      (node (ref "VD1") (pin "958") (pinfunction "OUT958_958") (pintype "passive"))
    )
    (net (code "961") (name "unconnected-(VD1D-OUT959-Pad959)") (class "Default")
      (node (ref "VD1") (pin "959") (pinfunction "OUT959_959") (pintype "passive"))
    )
    (net (code "962") (name "unconnected-(VD1D-OUT960-Pad960)") (class "Default")
      (node (ref "VD1") (pin "960") (pinfunction "OUT960_960") (pintype "passive"))
    )
    (net (code "963") (name "unconnected-(VD1D-OUT961-Pad961)") (class "Default")
      (node (ref "VD1") (pin "961") (pinfunction "OUT961_961") (pintype "passive"))
    )
    (net (code "964") (name "unconnected-(VD1D-OUT962-Pad962)") (class "Default")
      (node (ref "VD1") (pin "962") (pinfunction "OUT962_962") (pintype "passive"))
    )
    (net (code "965") (name "unconnected-(VD1D-OUT963-Pad963)") (class "Default")
      (node (ref "VD1") (pin "963") (pinfunction "OUT963_963") (pintype "passive"))
    )
    (net (code "966") (name "unconnected-(VD1D-OUT964-Pad964)") (class "Default")
      (node (ref "VD1") (pin "964") (pinfunction "OUT964_964") (pintype "passive"))
    )
    (net (code "967") (name "unconnected-(VD1D-OUT965-Pad965)") (class "Default")
      (node (ref "VD1") (pin "965") (pinfunction "OUT965_965") (pintype "passive"))
    )
    (net (code "968") (name "unconnected-(VD1D-OUT966-Pad966)") (class "Default")
      (node (ref "VD1") (pin "966") (pinfunction "OUT966_966") (pintype "passive"))
    )
    (net (code "969") (name "unconnected-(VD1D-OUT967-Pad967)") (class "Default")
      (node (ref "VD1") (pin "967") (pinfunction "OUT967_967") (pintype "passive"))
    )
    (net (code "970") (name "unconnected-(VD1D-OUT968-Pad968)") (class "Default")
      (node (ref "VD1") (pin "968") (pinfunction "OUT968_968") (pintype "passive"))
    )
    (net (code "971") (name "unconnected-(VD1D-OUT969-Pad969)") (class "Default")
      (node (ref "VD1") (pin "969") (pinfunction "OUT969_969") (pintype "passive"))
    )
    (net (code "972") (name "unconnected-(VD1D-OUT970-Pad970)") (class "Default")
      (node (ref "VD1") (pin "970") (pinfunction "OUT970_970") (pintype "passive"))
    )
    (net (code "973") (name "unconnected-(VD1D-OUT971-Pad971)") (class "Default")
      (node (ref "VD1") (pin "971") (pinfunction "OUT971_971") (pintype "passive"))
    )
    (net (code "974") (name "unconnected-(VD1D-OUT972-Pad972)") (class "Default")
      (node (ref "VD1") (pin "972") (pinfunction "OUT972_972") (pintype "passive"))
    )
    (net (code "975") (name "unconnected-(VD1D-OUT973-Pad973)") (class "Default")
      (node (ref "VD1") (pin "973") (pinfunction "OUT973_973") (pintype "passive"))
    )
    (net (code "976") (name "unconnected-(VD1D-OUT974-Pad974)") (class "Default")
      (node (ref "VD1") (pin "974") (pinfunction "OUT974_974") (pintype "passive"))
    )
    (net (code "977") (name "unconnected-(VD1D-OUT975-Pad975)") (class "Default")
      (node (ref "VD1") (pin "975") (pinfunction "OUT975_975") (pintype "passive"))
    )
    (net (code "978") (name "unconnected-(VD1D-OUT976-Pad976)") (class "Default")
      (node (ref "VD1") (pin "976") (pinfunction "OUT976_976") (pintype "passive"))
    )
    (net (code "979") (name "unconnected-(VD1D-OUT977-Pad977)") (class "Default")
      (node (ref "VD1") (pin "977") (pinfunction "OUT977_977") (pintype "passive"))
    )
    (net (code "980") (name "unconnected-(VD1D-OUT978-Pad978)") (class "Default")
      (node (ref "VD1") (pin "978") (pinfunction "OUT978_978") (pintype "passive"))
    )
    (net (code "981") (name "unconnected-(VD1D-OUT979-Pad979)") (class "Default")
      (node (ref "VD1") (pin "979") (pinfunction "OUT979_979") (pintype "passive"))
    )
    (net (code "982") (name "unconnected-(VD1D-OUT980-Pad980)") (class "Default")
      (node (ref "VD1") (pin "980") (pinfunction "OUT980_980") (pintype "passive"))
    )
    (net (code "983") (name "unconnected-(VD1D-OUT981-Pad981)") (class "Default")
      (node (ref "VD1") (pin "981") (pinfunction "OUT981_981") (pintype "passive"))
    )
    (net (code "984") (name "unconnected-(VD1D-OUT982-Pad982)") (class "Default")
      (node (ref "VD1") (pin "982") (pinfunction "OUT982_982") (pintype "passive"))
    )
    (net (code "985") (name "unconnected-(VD1D-OUT983-Pad983)") (class "Default")
      (node (ref "VD1") (pin "983") (pinfunction "OUT983_983") (pintype "passive"))
    )
    (net (code "986") (name "unconnected-(VD1D-OUT984-Pad984)") (class "Default")
      (node (ref "VD1") (pin "984") (pinfunction "OUT984_984") (pintype "passive"))
    )
    (net (code "987") (name "unconnected-(VD1D-OUT985-Pad985)") (class "Default")
      (node (ref "VD1") (pin "985") (pinfunction "OUT985_985") (pintype "passive"))
    )
    (net (code "988") (name "unconnected-(VD1D-OUT986-Pad986)") (class "Default")
      (node (ref "VD1") (pin "986") (pinfunction "OUT986_986") (pintype "passive"))
    )
    (net (code "989") (name "unconnected-(VD1D-OUT987-Pad987)") (class "Default")
      (node (ref "VD1") (pin "987") (pinfunction "OUT987_987") (pintype "passive"))
    )
    (net (code "990") (name "unconnected-(VD1D-OUT988-Pad988)") (class "Default")
      (node (ref "VD1") (pin "988") (pinfunction "OUT988_988") (pintype "passive"))
    )
    (net (code "991") (name "unconnected-(VD1D-OUT989-Pad989)") (class "Default")
      (node (ref "VD1") (pin "989") (pinfunction "OUT989_989") (pintype "passive"))
    )
    (net (code "992") (name "unconnected-(VD1D-OUT990-Pad990)") (class "Default")
      (node (ref "VD1") (pin "990") (pinfunction "OUT990_990") (pintype "passive"))
    )
    (net (code "993") (name "unconnected-(VD1D-OUT991-Pad991)") (class "Default")
      (node (ref "VD1") (pin "991") (pinfunction "OUT991_991") (pintype "passive"))
    )
    (net (code "994") (name "unconnected-(VD1D-OUT992-Pad992)") (class "Default")
      (node (ref "VD1") (pin "992") (pinfunction "OUT992_992") (pintype "passive"))
    )
    (net (code "995") (name "unconnected-(VD1D-OUT993-Pad993)") (class "Default")
      (node (ref "VD1") (pin "993") (pinfunction "OUT993_993") (pintype "passive"))
    )
    (net (code "996") (name "unconnected-(VD1D-OUT994-Pad994)") (class "Default")
      (node (ref "VD1") (pin "994") (pinfunction "OUT994_994") (pintype "passive"))
    )
    (net (code "997") (name "unconnected-(VD1D-OUT995-Pad995)") (class "Default")
      (node (ref "VD1") (pin "995") (pinfunction "OUT995_995") (pintype "passive"))
    )
    (net (code "998") (name "unconnected-(VD1D-OUT996-Pad996)") (class "Default")
      (node (ref "VD1") (pin "996") (pinfunction "OUT996_996") (pintype "passive"))
    )
    (net (code "999") (name "unconnected-(VD1D-OUT997-Pad997)") (class "Default")
      (node (ref "VD1") (pin "997") (pinfunction "OUT997_997") (pintype "passive"))
    )
    (net (code "1000") (name "unconnected-(VD1D-OUT998-Pad998)") (class "Default")
      (node (ref "VD1") (pin "998") (pinfunction "OUT998_998") (pintype "passive"))
    )
    (net (code "1001") (name "unconnected-(VD1D-OUT999-Pad999)") (class "Default")
      (node (ref "VD1") (pin "999") (pinfunction "OUT999_999") (pintype "passive"))
    )
    (net (code "1002") (name "unconnected-(VD1D-OUT1000-Pad1000)") (class "Default")
      (node (ref "VD1") (pin "1000") (pinfunction "OUT1000_1000") (pintype "passive"))
    )
    (net (code "1003") (name "unconnected-(VD1D-OUT1001-Pad1001)") (class "Default")
      (node (ref "VD1") (pin "1001") (pinfunction "OUT1001_1001") (pintype "passive"))
    )
    (net (code "1004") (name "unconnected-(VD1D-OUT1002-Pad1002)") (class "Default")
      (node (ref "VD1") (pin "1002") (pinfunction "OUT1002_1002") (pintype "passive"))
    )
    (net (code "1005") (name "unconnected-(VD1D-OUT1003-Pad1003)") (class "Default")
      (node (ref "VD1") (pin "1003") (pinfunction "OUT1003_1003") (pintype "passive"))
    )
    (net (code "1006") (name "unconnected-(VD1D-OUT1004-Pad1004)") (class "Default")
      (node (ref "VD1") (pin "1004") (pinfunction "OUT1004_1004") (pintype "passive"))
    )
    (net (code "1007") (name "unconnected-(VD1D-OUT1005-Pad1005)") (class "Default")
      (node (ref "VD1") (pin "1005") (pinfunction "OUT1005_1005") (pintype "passive"))
    )
    (net (code "1008") (name "unconnected-(VD1D-OUT1006-Pad1006)") (class "Default")
      (node (ref "VD1") (pin "1006") (pinfunction "OUT1006_1006") (pintype "passive"))
    )
    (net (code "1009") (name "unconnected-(VD1D-OUT1007-Pad1007)") (class "Default")
      (node (ref "VD1") (pin "1007") (pinfunction "OUT1007_1007") (pintype "passive"))
    )
    (net (code "1010") (name "unconnected-(VD1D-OUT1008-Pad1008)") (class "Default")
      (node (ref "VD1") (pin "1008") (pinfunction "OUT1008_1008") (pintype "passive"))
    )
    (net (code "1011") (name "unconnected-(VD1D-OUT1009-Pad1009)") (class "Default")
      (node (ref "VD1") (pin "1009") (pinfunction "OUT1009_1009") (pintype "passive"))
    )
    (net (code "1012") (name "unconnected-(VD1D-OUT1010-Pad1010)") (class "Default")
      (node (ref "VD1") (pin "1010") (pinfunction "OUT1010_1010") (pintype "passive"))
    )
    (net (code "1013") (name "unconnected-(VD1D-OUT1011-Pad1011)") (class "Default")
      (node (ref "VD1") (pin "1011") (pinfunction "OUT1011_1011") (pintype "passive"))
    )
    (net (code "1014") (name "unconnected-(VD1D-OUT1012-Pad1012)") (class "Default")
      (node (ref "VD1") (pin "1012") (pinfunction "OUT1012_1012") (pintype "passive"))
    )
    (net (code "1015") (name "unconnected-(VD1D-OUT1013-Pad1013)") (class "Default")
      (node (ref "VD1") (pin "1013") (pinfunction "OUT1013_1013") (pintype "passive"))
    )
    (net (code "1016") (name "unconnected-(VD1D-OUT1014-Pad1014)") (class "Default")
      (node (ref "VD1") (pin "1014") (pinfunction "OUT1014_1014") (pintype "passive"))
    )
    (net (code "1017") (name "unconnected-(VD1D-OUT1015-Pad1015)") (class "Default")
      (node (ref "VD1") (pin "1015") (pinfunction "OUT1015_1015") (pintype "passive"))
    )
    (net (code "1018") (name "unconnected-(VD1D-OUT1016-Pad1016)") (class "Default")
      (node (ref "VD1") (pin "1016") (pinfunction "OUT1016_1016") (pintype "passive"))
    )
    (net (code "1019") (name "unconnected-(VD1D-OUT1017-Pad1017)") (class "Default")
      (node (ref "VD1") (pin "1017") (pinfunction "OUT1017_1017") (pintype "passive"))
    )
    (net (code "1020") (name "unconnected-(VD1D-OUT1018-Pad1018)") (class "Default")
      (node (ref "VD1") (pin "1018") (pinfunction "OUT1018_1018") (pintype "passive"))
    )
    (net (code "1021") (name "unconnected-(VD1D-OUT1019-Pad1019)") (class "Default")
      (node (ref "VD1") (pin "1019") (pinfunction "OUT1019_1019") (pintype "passive"))
    )
    (net (code "1022") (name "unconnected-(VD1D-OUT1020-Pad1020)") (class "Default")
      (node (ref "VD1") (pin "1020") (pinfunction "OUT1020_1020") (pintype "passive"))
    )
    (net (code "1023") (name "unconnected-(VD1D-OUT1021-Pad1021)") (class "Default")
      (node (ref "VD1") (pin "1021") (pinfunction "OUT1021_1021") (pintype "passive"))
    )
    (net (code "1024") (name "unconnected-(VD1D-OUT1022-Pad1022)") (class "Default")
      (node (ref "VD1") (pin "1022") (pinfunction "OUT1022_1022") (pintype "passive"))
    )
    (net (code "1025") (name "unconnected-(VD1D-OUT1023-Pad1023)") (class "Default")
      (node (ref "VD1") (pin "1023") (pinfunction "OUT1023_1023") (pintype "passive"))
    )
    (net (code "1026") (name "unconnected-(VD1D-OUT1024-Pad1024)") (class "Default")
      (node (ref "VD1") (pin "1024") (pinfunction "OUT1024_1024") (pintype "passive"))
    )
  )
)
